# tc083-18.net
KiCad netlist of a schematic drawn in EAGLE
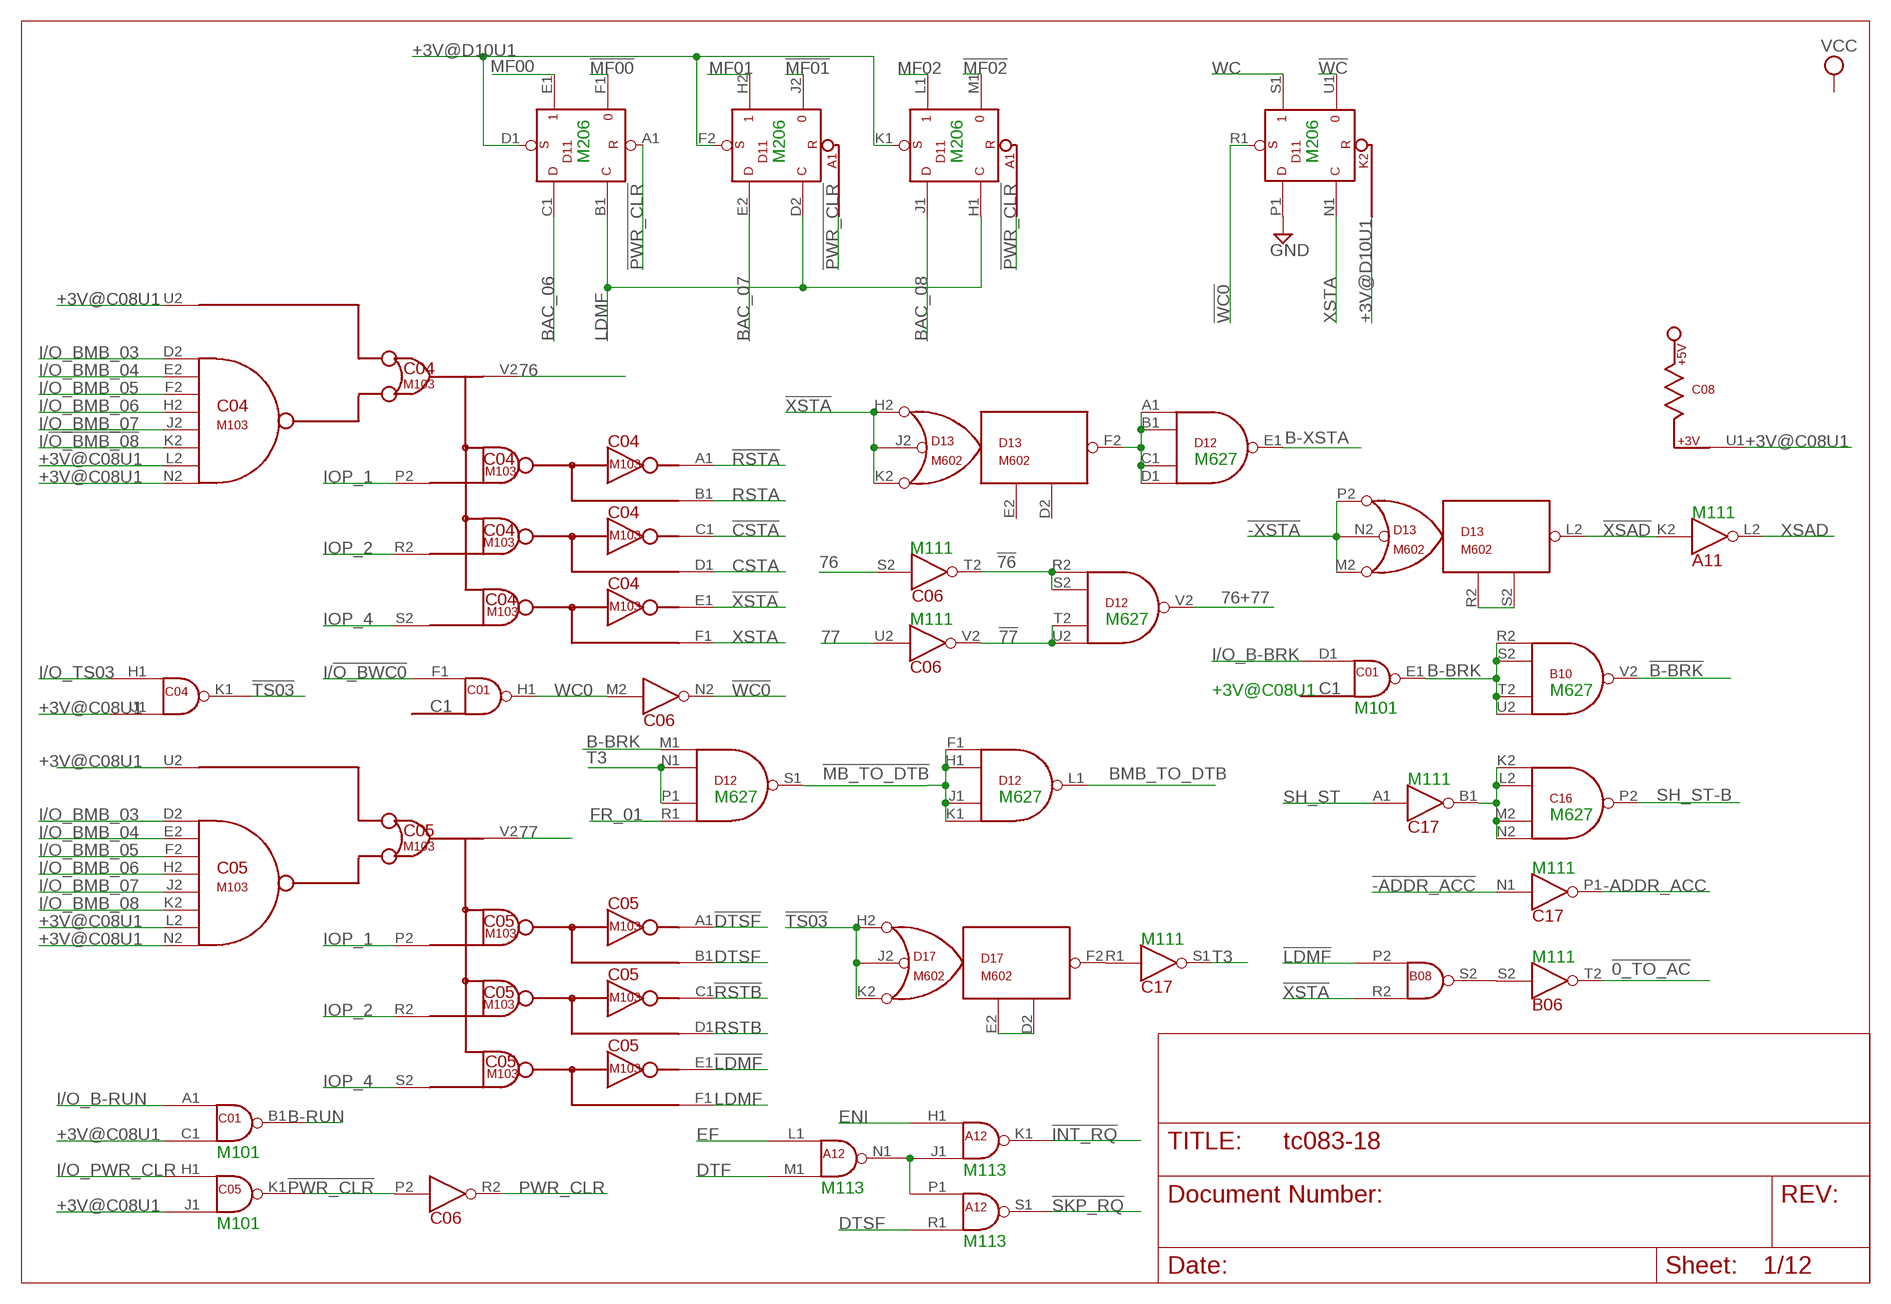
[diagram p0: schematic, sheet 1]
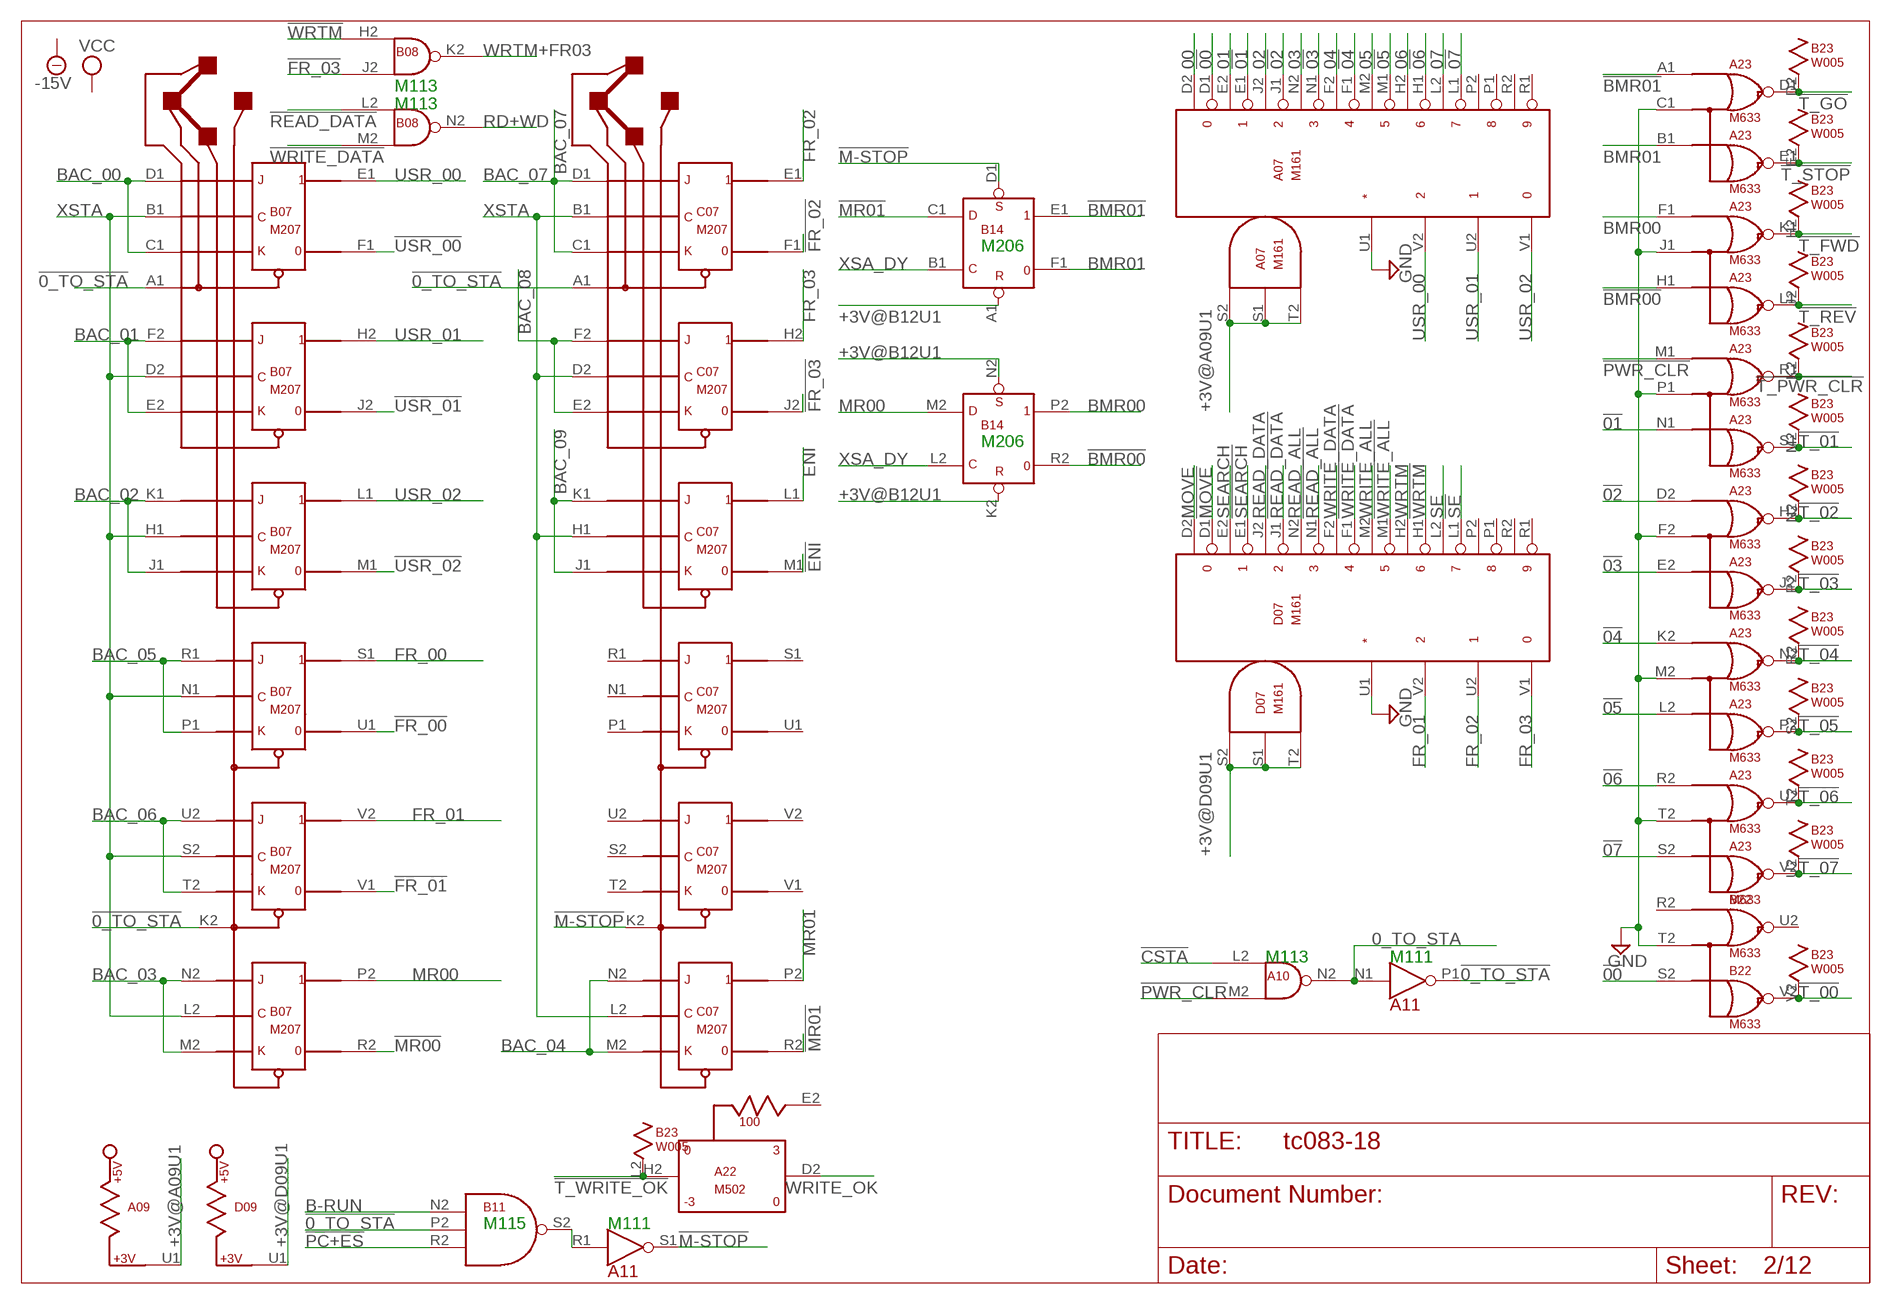
[diagram p1: schematic, sheet 2]
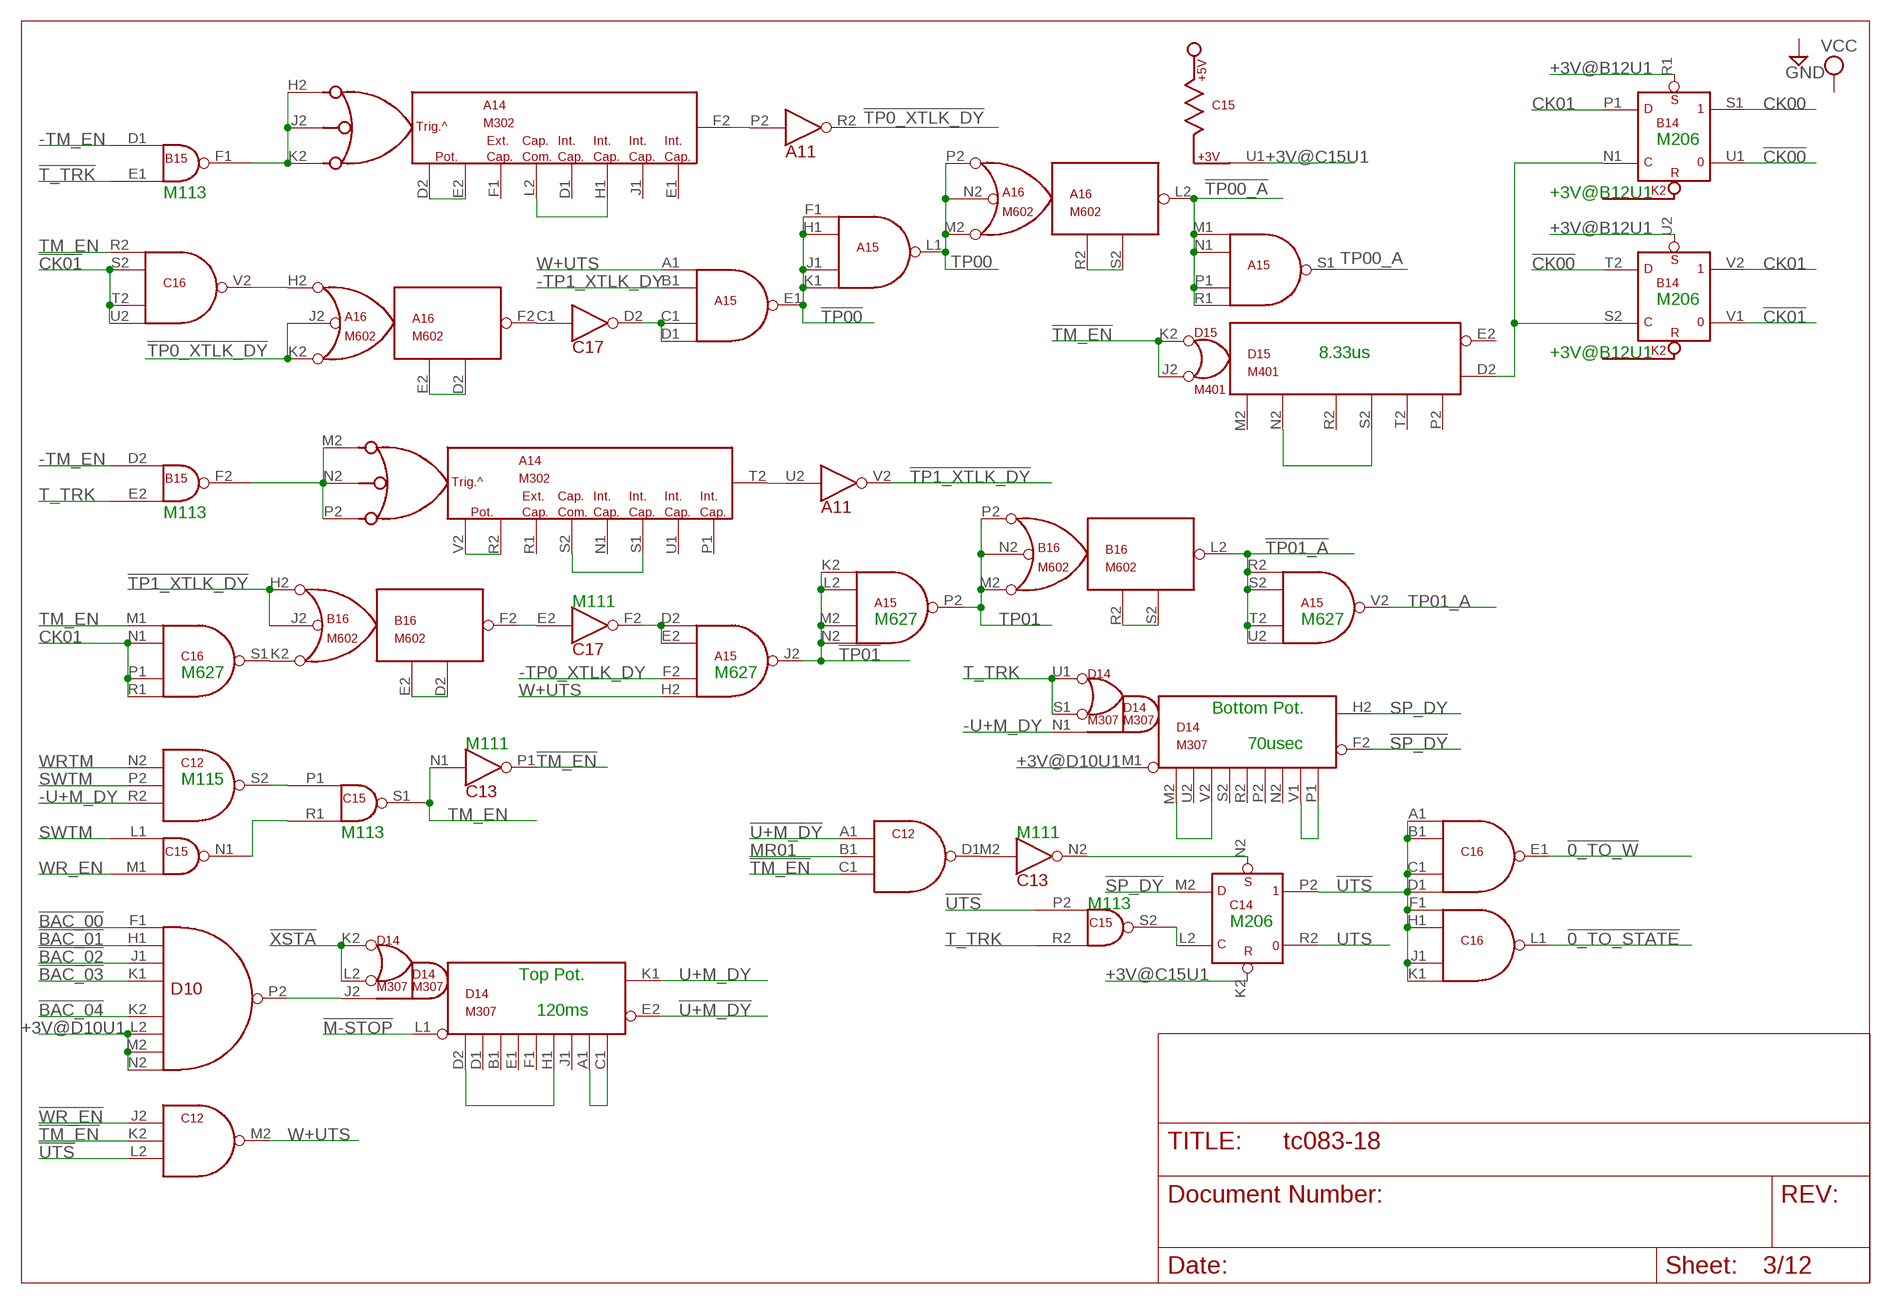
[diagram p2: schematic, sheet 3]
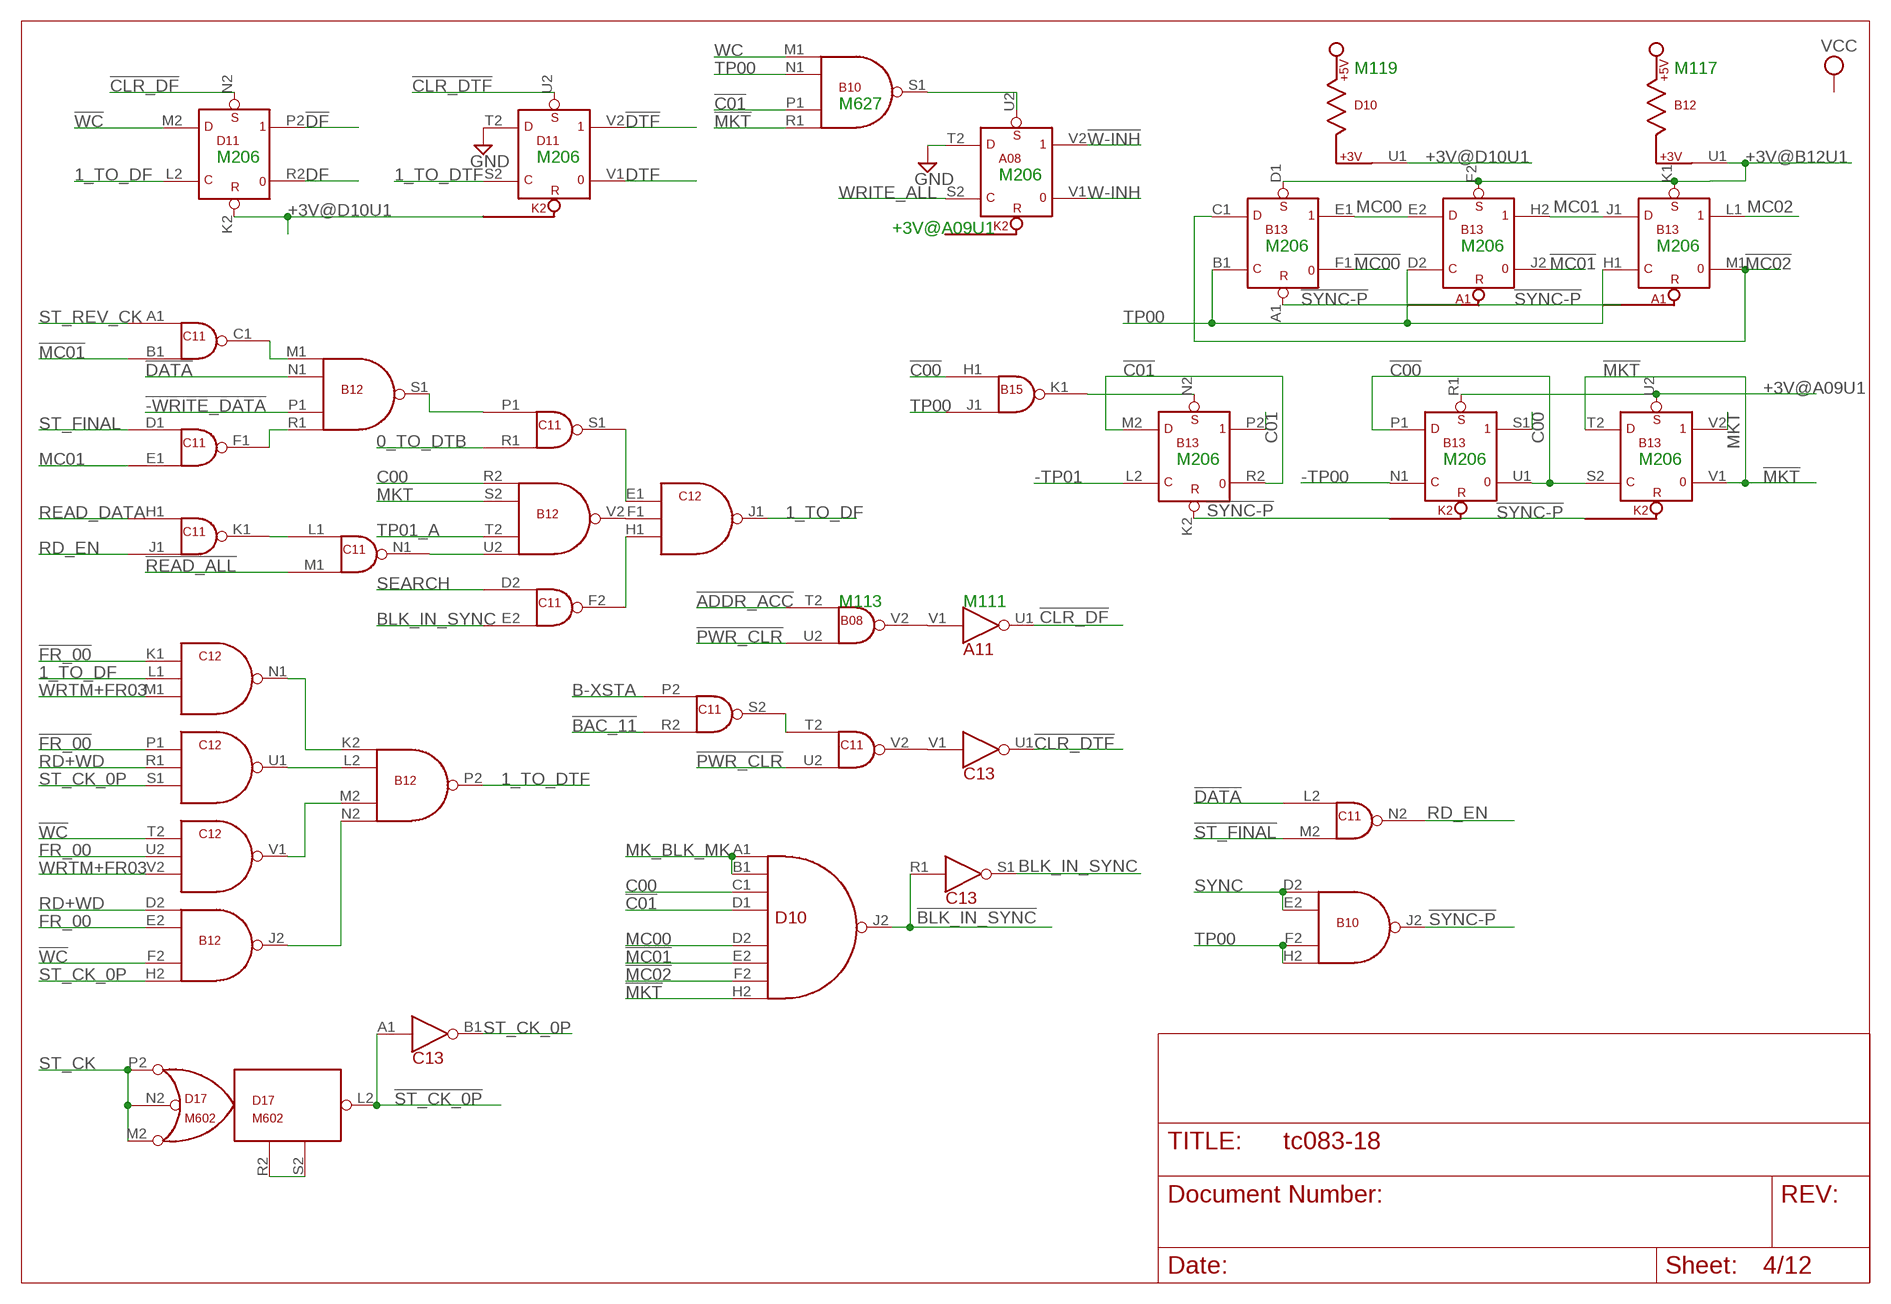
[diagram p3: schematic, sheet 4]
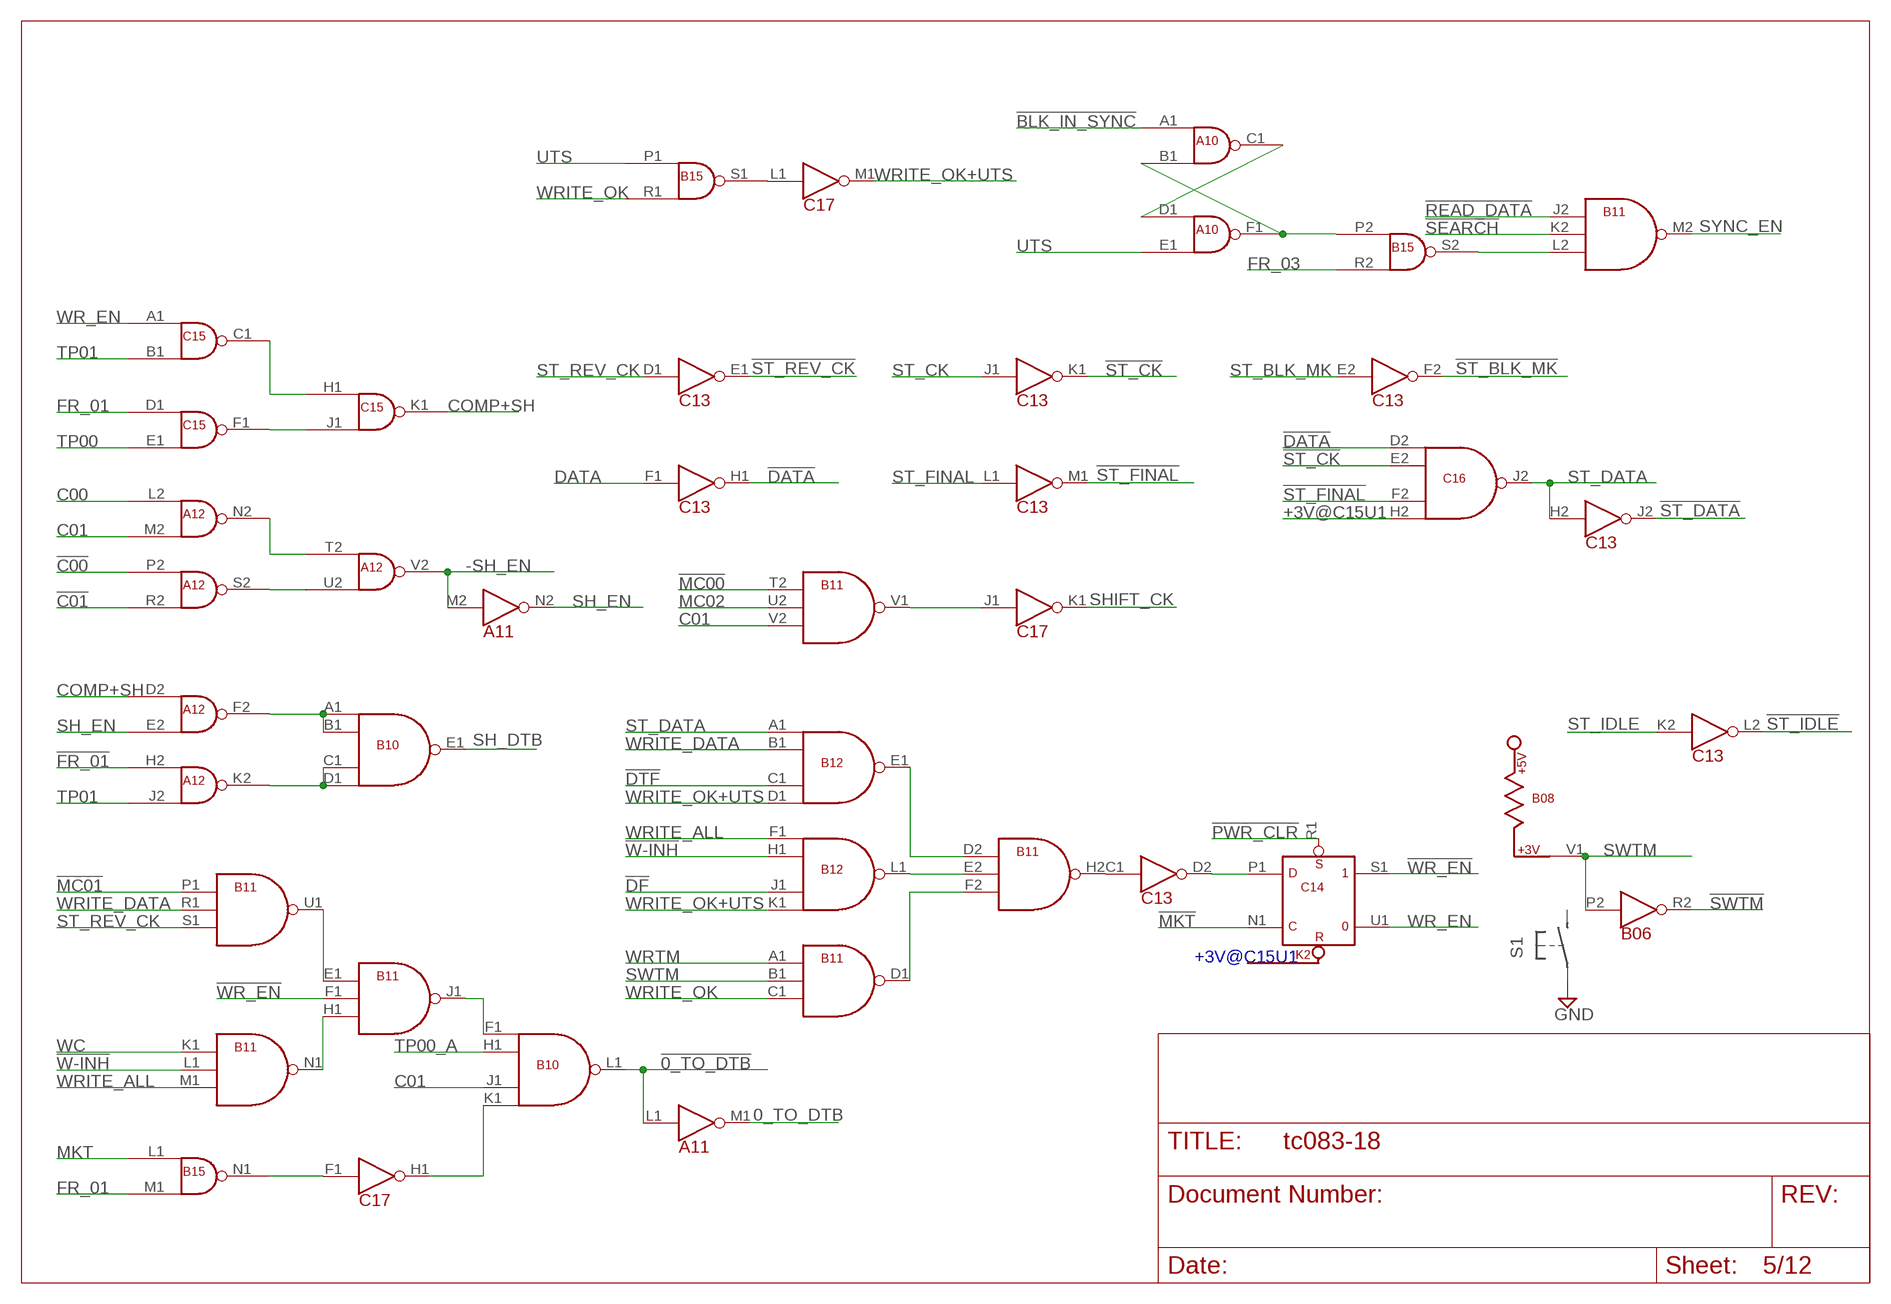
[diagram p4: schematic, sheet 5]
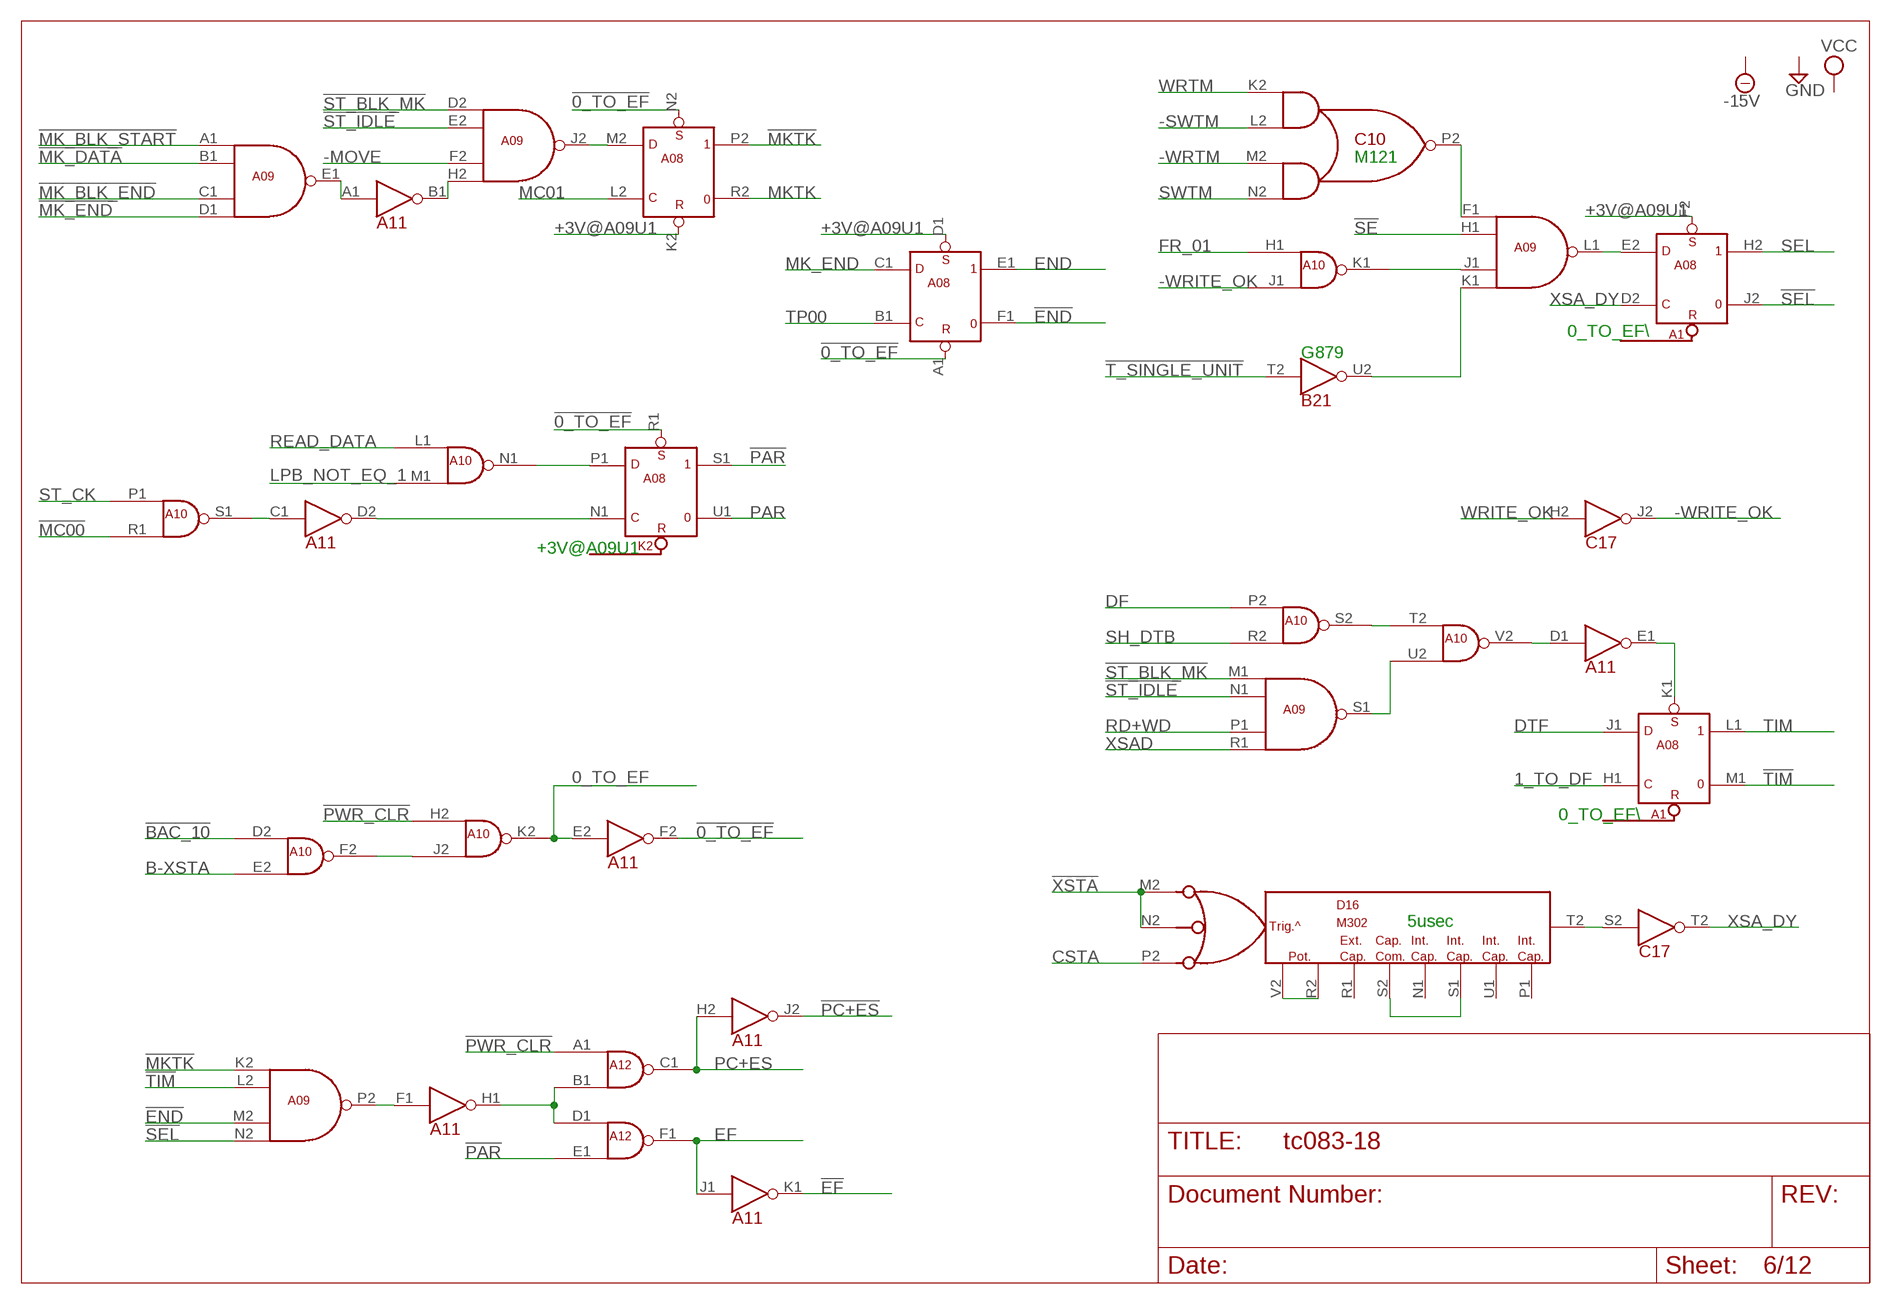
[diagram p5: schematic, sheet 6]
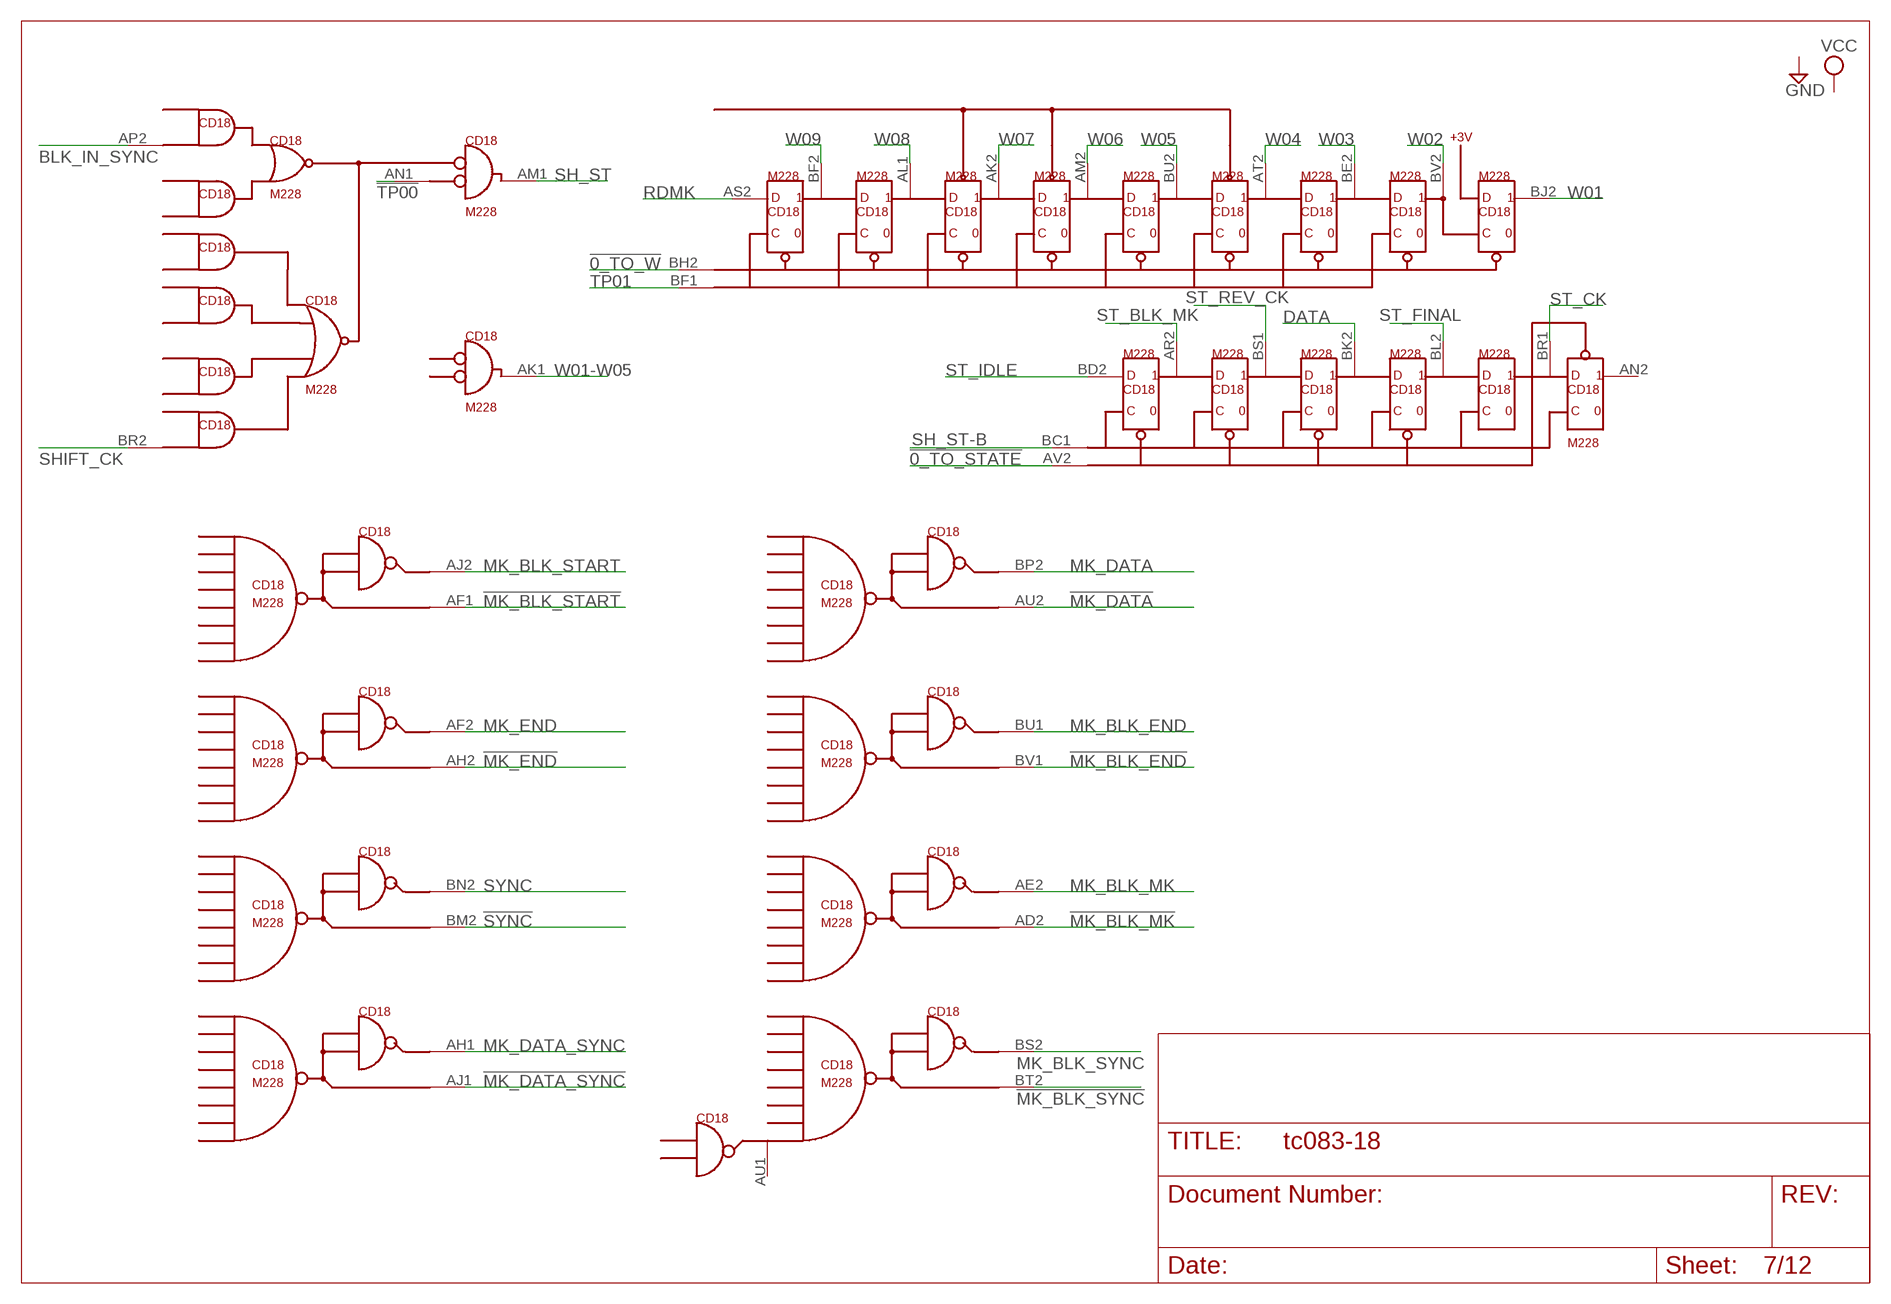
[diagram p6: schematic, sheet 7]
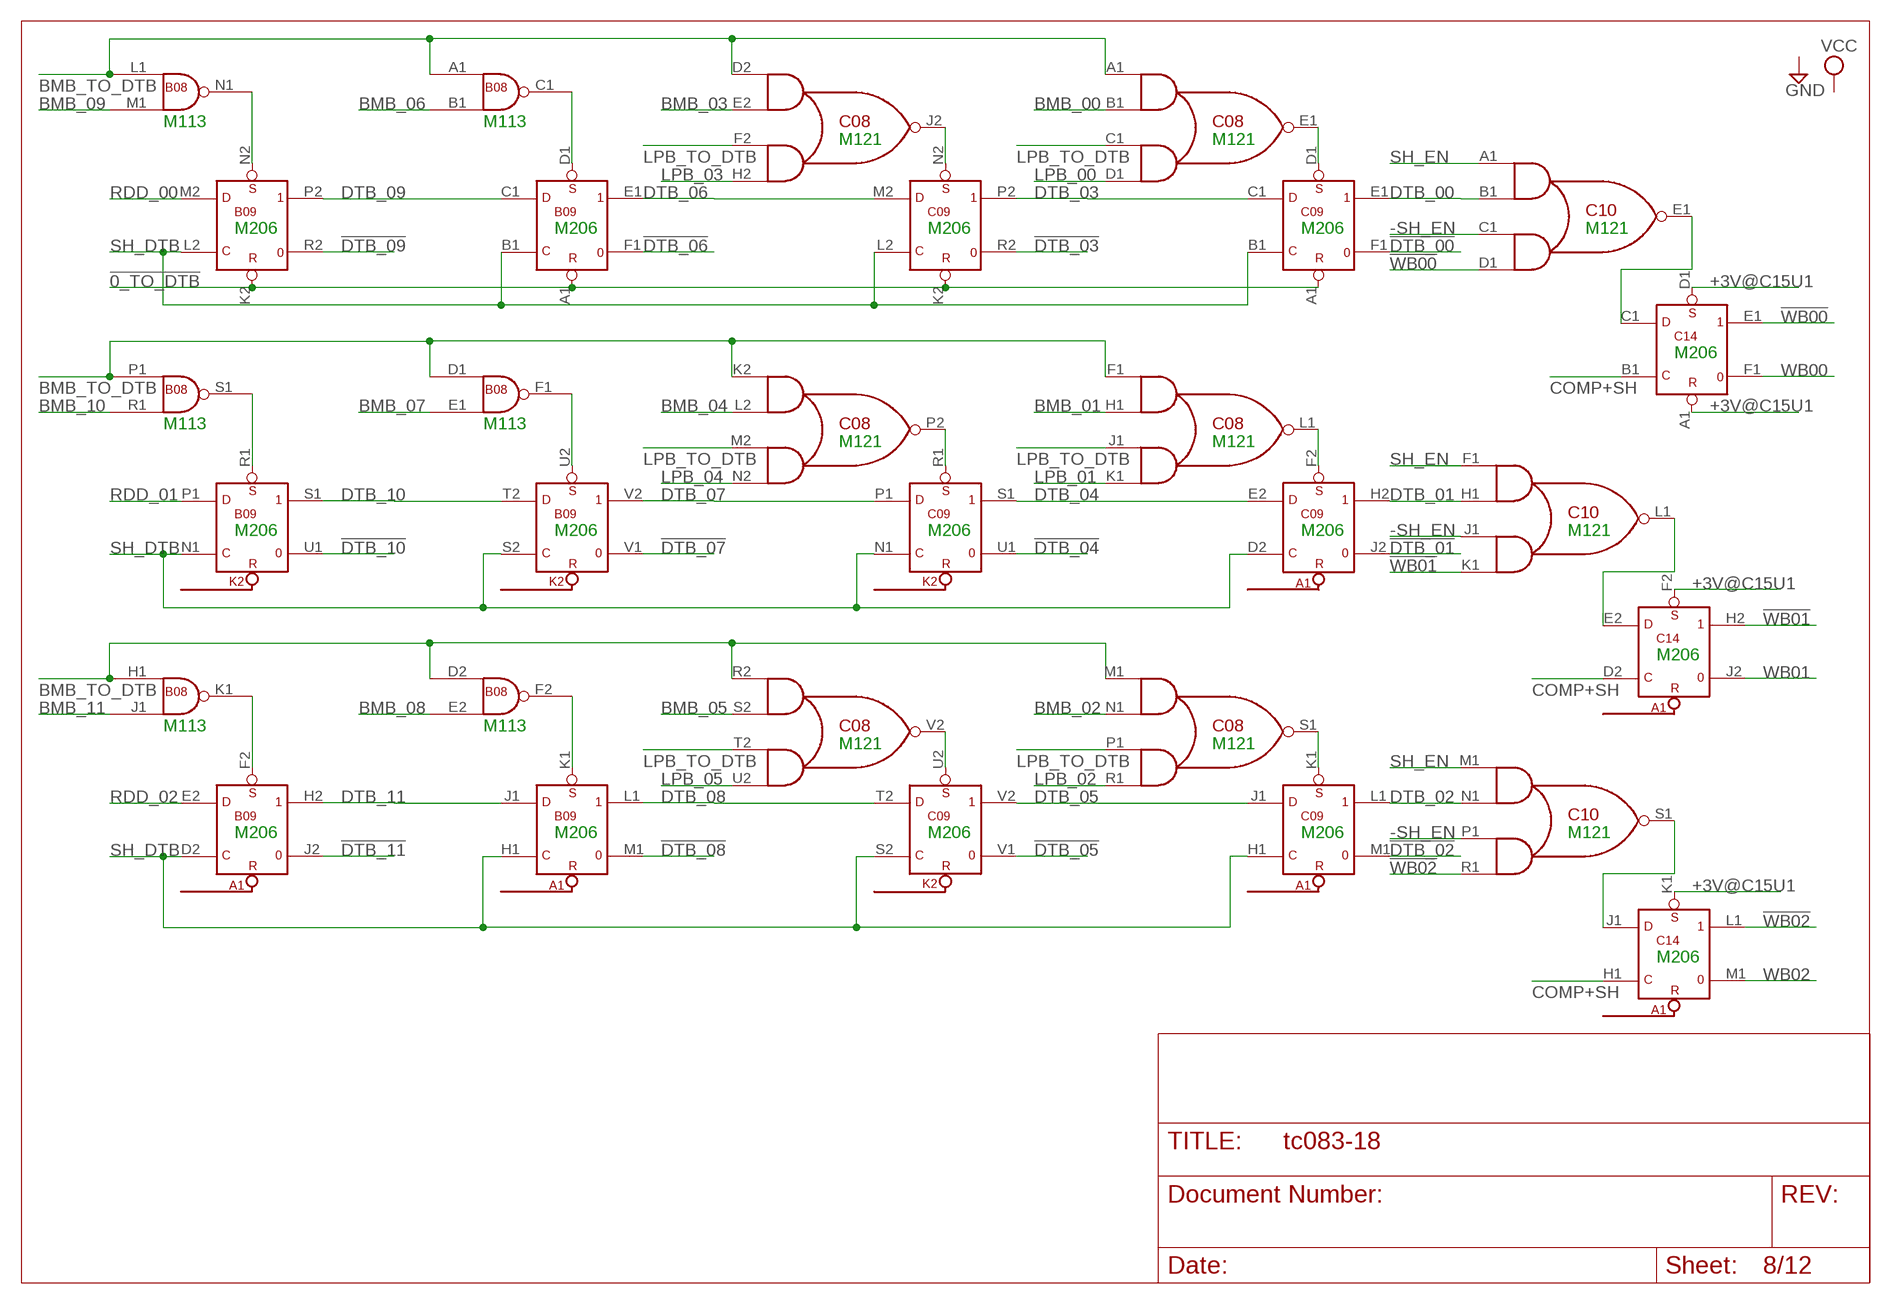
[diagram p7: schematic, sheet 8]
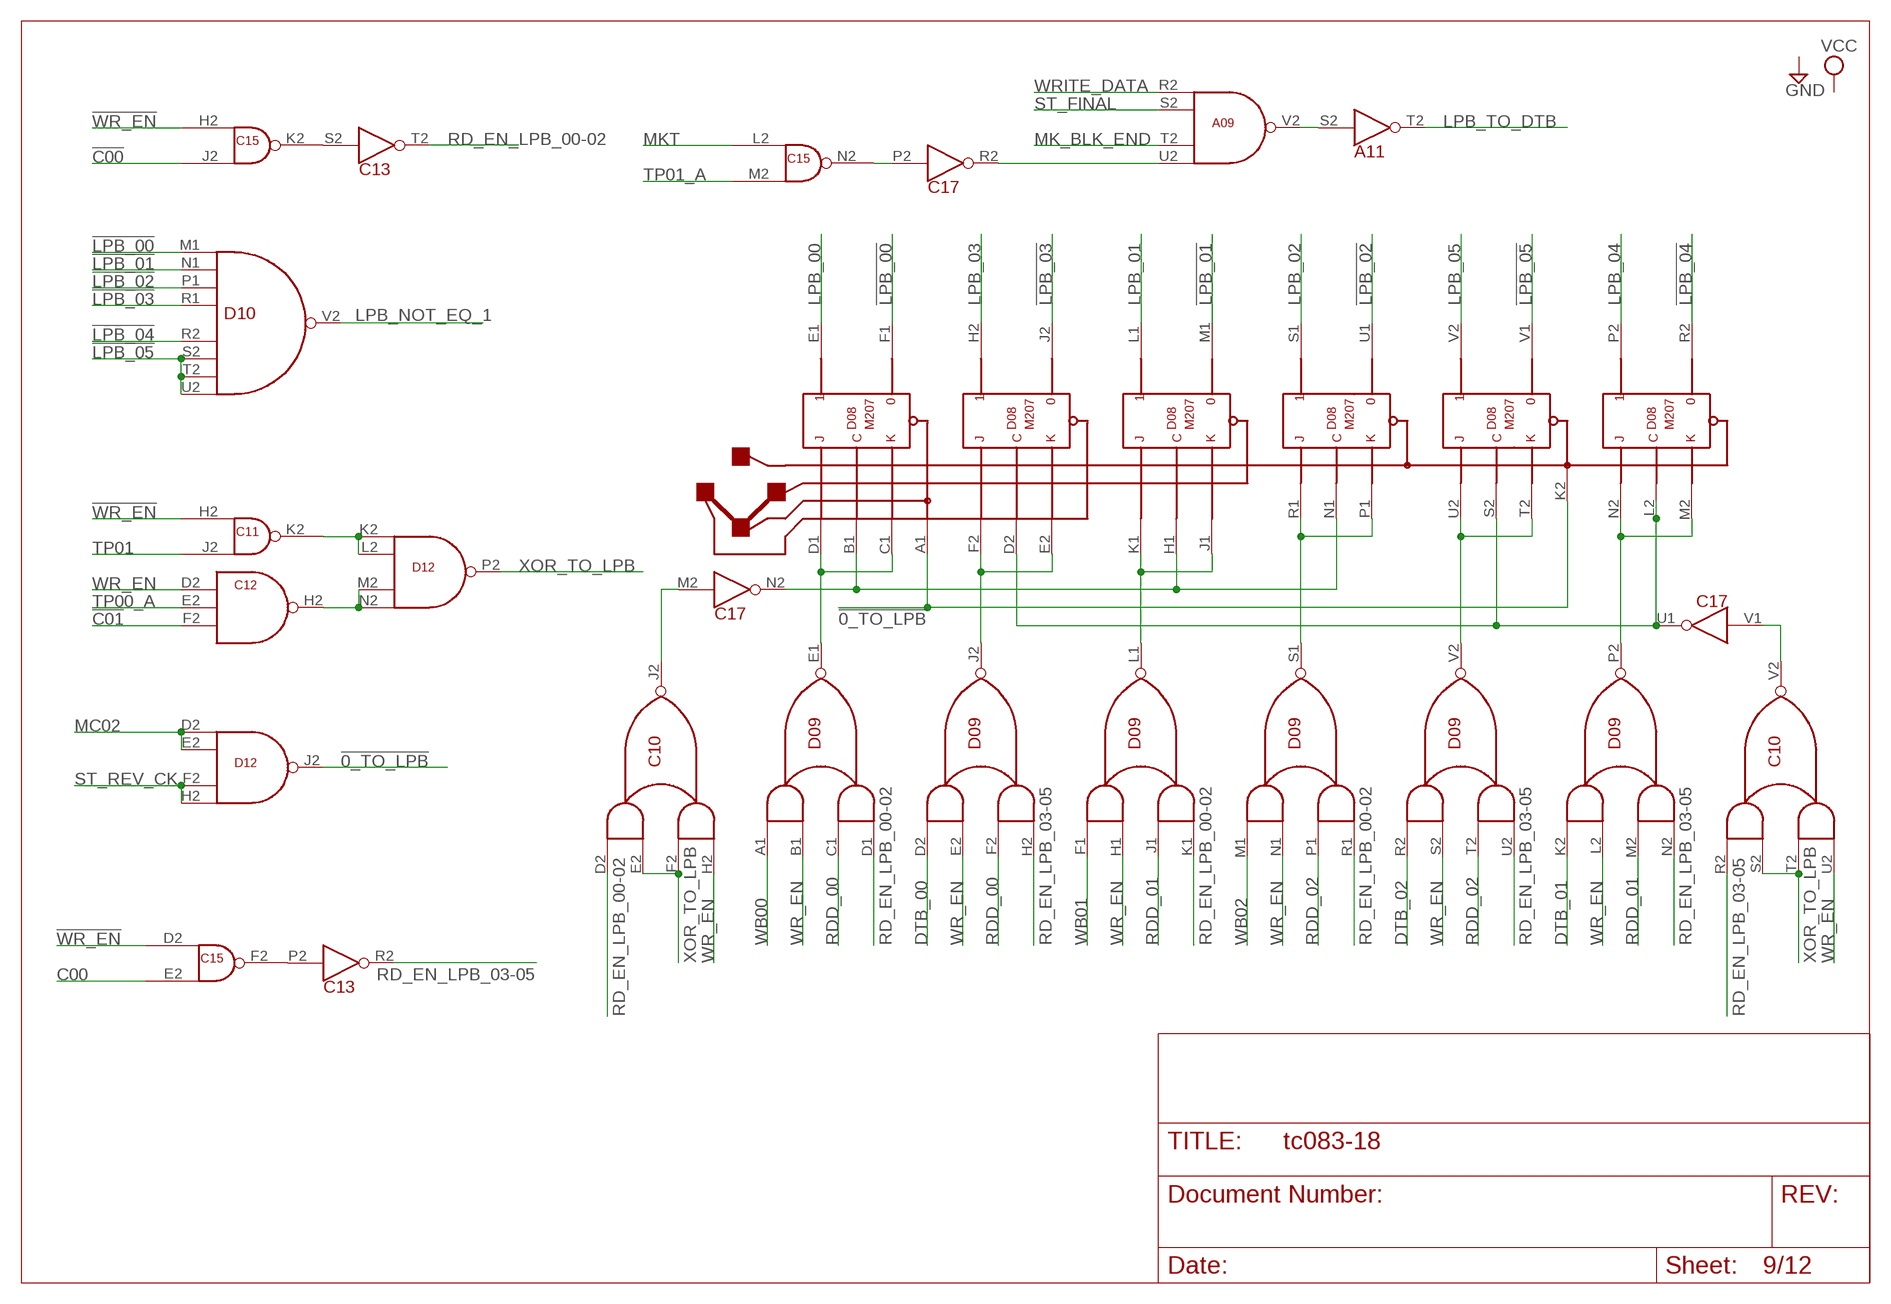
[diagram p8: schematic, sheet 9]
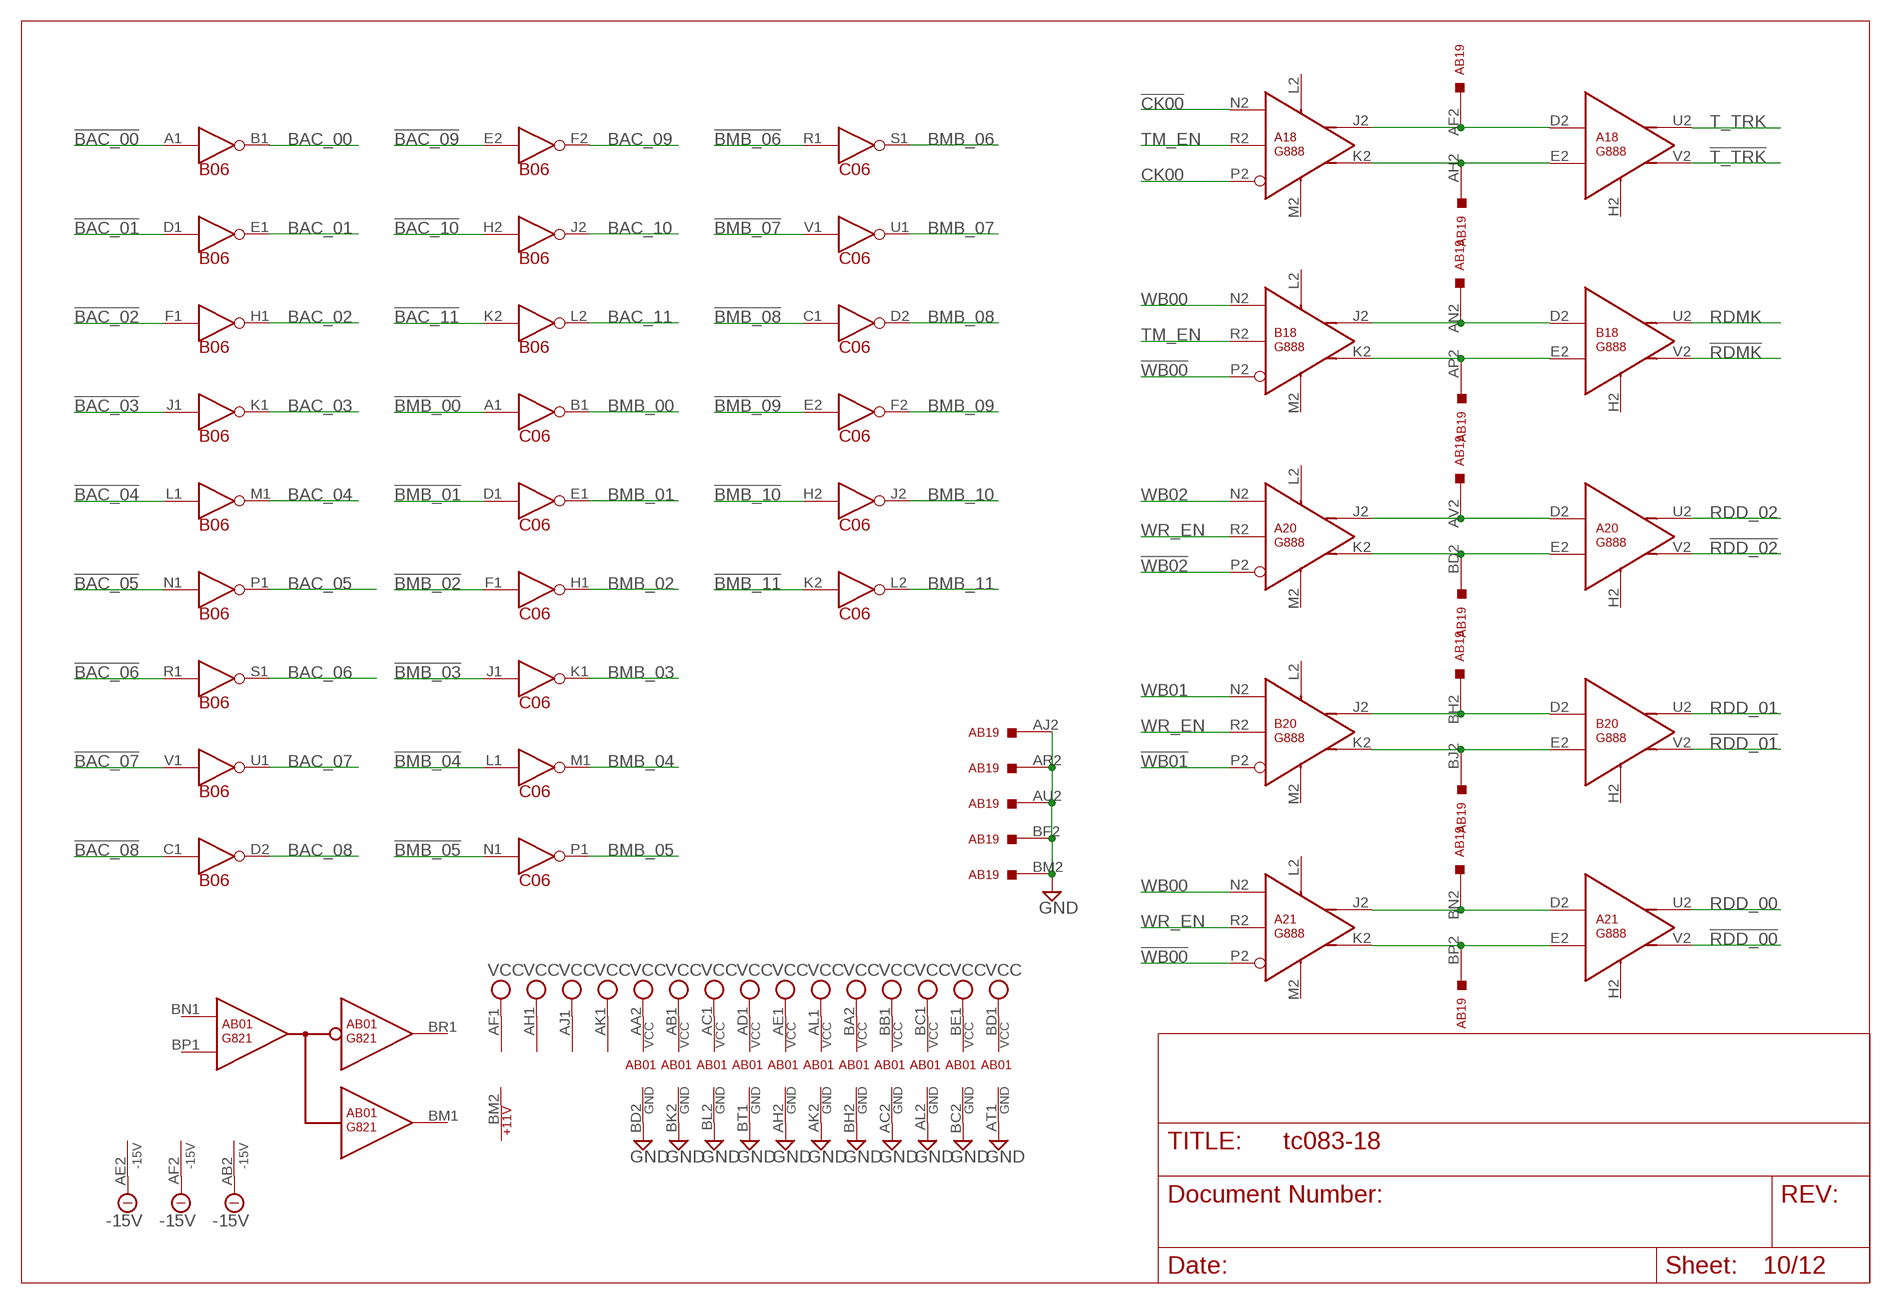
[diagram p9: schematic, sheet 10]
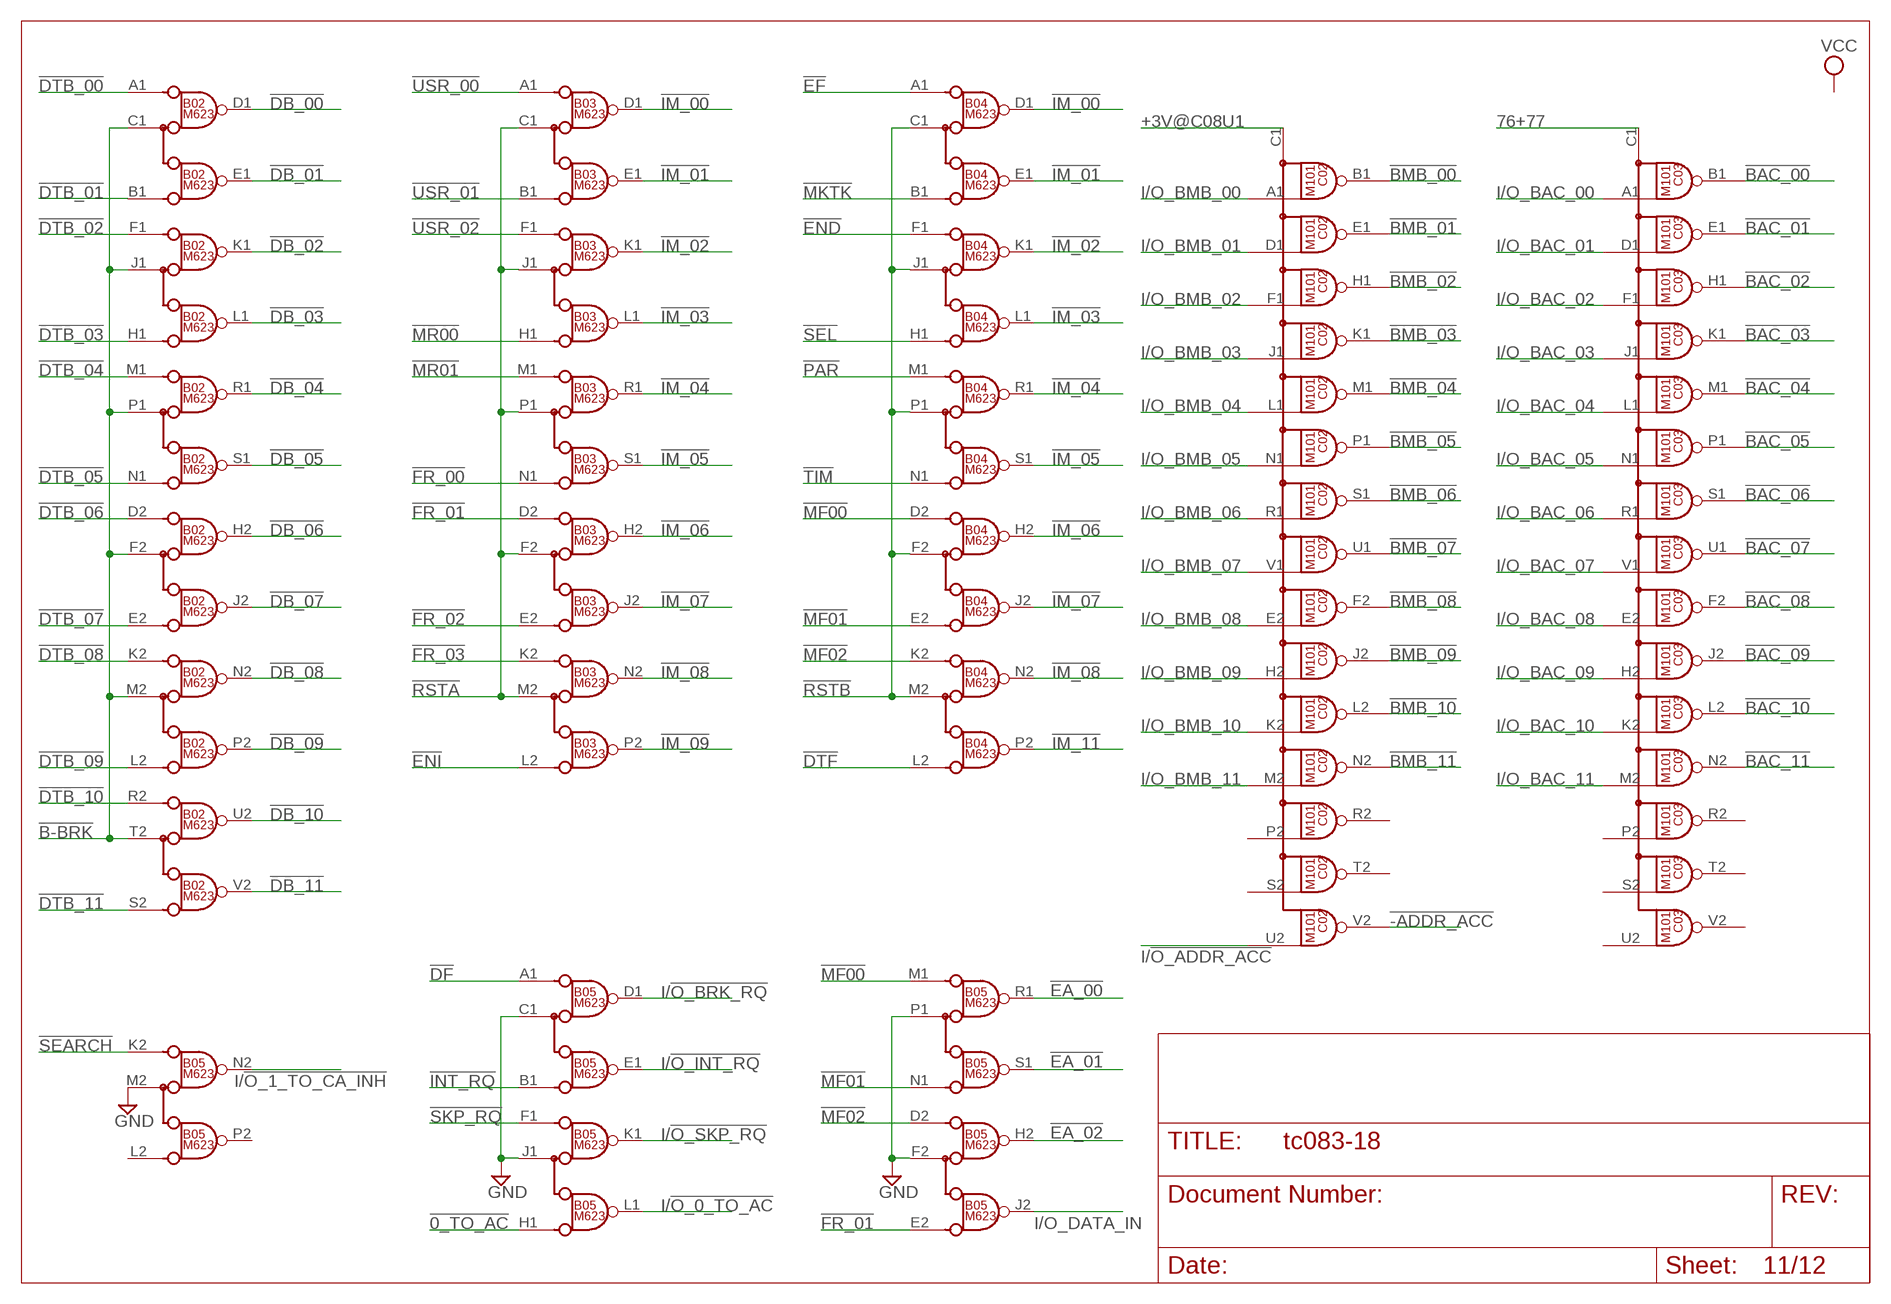
[diagram p10: schematic, sheet 11]
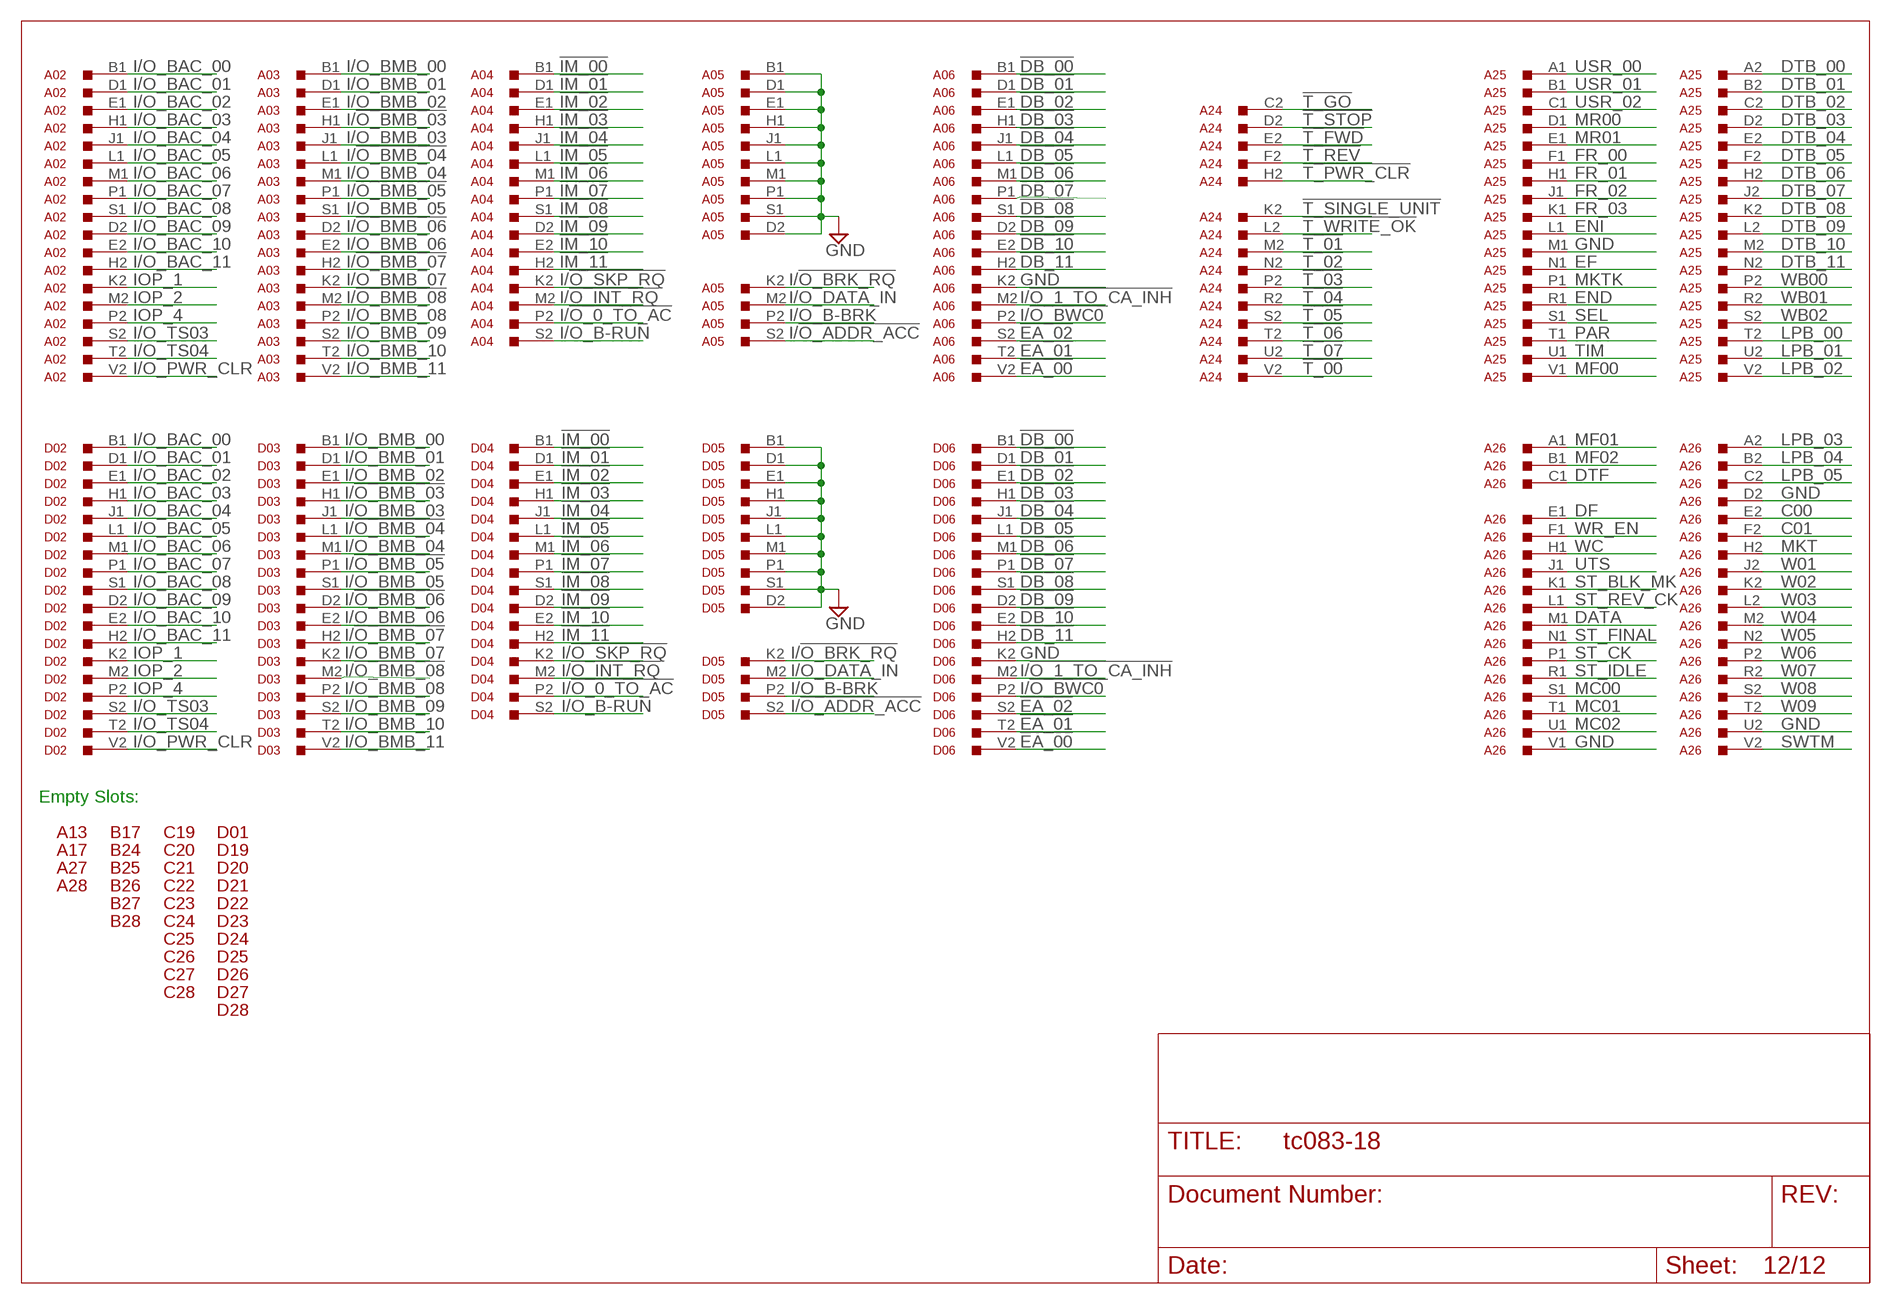
[diagram p11: schematic, sheet 12]

(export (version "E")
  (design (tool "Eeschema 10.0.6"))
  (components
    (comp (ref "A07")
      (value "A07")
      (footprint "eagle-import:H807")
      (libsource (lib "eagle-import") (part "M161"))
    )
    (comp (ref "A09")
      (value "M117")
      (footprint "eagle-import:H807")
      (libsource (lib "eagle-import") (part "M117"))
    )
    (comp (ref "A10")
      (value "M113")
      (footprint "eagle-import:H807")
      (libsource (lib "eagle-import") (part "M113"))
    )
    (comp (ref "A11")
      (value "A11")
      (footprint "eagle-import:H807")
      (libsource (lib "eagle-import") (part "M111"))
    )
    (comp (ref "A22")
      (value "M502")
      (footprint "eagle-import:H807")
      (libsource (lib "eagle-import") (part "M502"))
    )
    (comp (ref "A23")
      (value "M633")
      (footprint "eagle-import:H807")
      (libsource (lib "eagle-import") (part "M633"))
    )
    (comp (ref "B07")
      (value "B07")
      (footprint "eagle-import:H807")
      (libsource (lib "eagle-import") (part "M207"))
    )
    (comp (ref "B08")
      (value "B08")
      (footprint "eagle-import:H807")
      (libsource (lib "eagle-import") (part "M113"))
    )
    (comp (ref "B11")
      (value "M115")
      (footprint "eagle-import:H807")
      (libsource (lib "eagle-import") (part "M115"))
    )
    (comp (ref "B14")
      (value "M206X")
      (footprint "eagle-import:H807")
      (libsource (lib "eagle-import") (part "M206X"))
    )
    (comp (ref "B22")
      (value "M633")
      (footprint "eagle-import:H807")
      (libsource (lib "eagle-import") (part "M633"))
    )
    (comp (ref "B23")
      (value "W005")
      (footprint "eagle-import:H807")
      (libsource (lib "eagle-import") (part "W005"))
    )
    (comp (ref "C07")
      (value "B07")
      (footprint "eagle-import:H807")
      (libsource (lib "eagle-import") (part "M207"))
    )
    (comp (ref "D07")
      (value "D07")
      (footprint "eagle-import:H807")
      (libsource (lib "eagle-import") (part "M161"))
    )
    (comp (ref "D09")
      (value "M121")
      (footprint "eagle-import:H807")
      (libsource (lib "eagle-import") (part "M121"))
    )
    (comp (ref "A12")
      (value "A12")
      (footprint "eagle-import:H807")
      (libsource (lib "eagle-import") (part "M113"))
    )
    (comp (ref "B06")
      (value "B06")
      (footprint "eagle-import:H807")
      (libsource (lib "eagle-import") (part "M111"))
    )
    (comp (ref "B10")
      (value "B10")
      (footprint "eagle-import:H807")
      (libsource (lib "eagle-import") (part "M627"))
    )
    (comp (ref "B12")
      (value "M117")
      (footprint "eagle-import:H807")
      (libsource (lib "eagle-import") (part "M117"))
    )
    (comp (ref "B15")
      (value "M113")
      (footprint "eagle-import:H807")
      (libsource (lib "eagle-import") (part "M113"))
    )
    (comp (ref "C13")
      (value "M111")
      (footprint "eagle-import:H807")
      (libsource (lib "eagle-import") (part "M111"))
    )
    (comp (ref "C14")
      (value "M206X")
      (footprint "eagle-import:H807")
      (libsource (lib "eagle-import") (part "M206X"))
    )
    (comp (ref "C15")
      (value "M113")
      (footprint "eagle-import:H807")
      (libsource (lib "eagle-import") (part "M113"))
    )
    (comp (ref "C16")
      (value "C16")
      (footprint "eagle-import:H807")
      (libsource (lib "eagle-import") (part "M627"))
    )
    (comp (ref "C17")
      (value "C17")
      (footprint "eagle-import:H807")
      (libsource (lib "eagle-import") (part "M111"))
    )
    (comp (ref "A08")
      (value "M206X")
      (footprint "eagle-import:H807")
      (libsource (lib "eagle-import") (part "M206X"))
    )
    (comp (ref "B13")
      (value "M206X")
      (footprint "eagle-import:H807")
      (libsource (lib "eagle-import") (part "M206X"))
    )
    (comp (ref "C11")
      (value "M113")
      (footprint "eagle-import:H807")
      (libsource (lib "eagle-import") (part "M113"))
    )
    (comp (ref "C12")
      (value "M115")
      (footprint "eagle-import:H807")
      (libsource (lib "eagle-import") (part "M115"))
    )
    (comp (ref "D10")
      (value "M119")
      (footprint "eagle-import:H807")
      (libsource (lib "eagle-import") (part "M119"))
    )
    (comp (ref "D11")
      (value "M206X")
      (footprint "eagle-import:H807")
      (libsource (lib "eagle-import") (part "M206X"))
    )
    (comp (ref "D17")
      (value "D17")
      (footprint "eagle-import:H807")
      (libsource (lib "eagle-import") (part "M602"))
    )
    (comp (ref "B09")
      (value "M206X")
      (footprint "eagle-import:H807")
      (libsource (lib "eagle-import") (part "M206X"))
    )
    (comp (ref "C08")
      (value "C08")
      (footprint "eagle-import:H807")
      (libsource (lib "eagle-import") (part "M121"))
    )
    (comp (ref "C09")
      (value "M206X")
      (footprint "eagle-import:H807")
      (libsource (lib "eagle-import") (part "M206X"))
    )
    (comp (ref "C10")
      (value "M121")
      (footprint "eagle-import:H807")
      (libsource (lib "eagle-import") (part "M121"))
    )
    (comp (ref "A14")
      (value "M302")
      (footprint "eagle-import:H807")
      (libsource (lib "eagle-import") (part "M302"))
    )
    (comp (ref "A15")
      (value "M627")
      (footprint "eagle-import:H807")
      (libsource (lib "eagle-import") (part "M627"))
    )
    (comp (ref "A16")
      (value "M602")
      (footprint "eagle-import:H807")
      (libsource (lib "eagle-import") (part "M602"))
    )
    (comp (ref "B16")
      (value "M602")
      (footprint "eagle-import:H807")
      (libsource (lib "eagle-import") (part "M602"))
    )
    (comp (ref "D14")
      (value "M307")
      (footprint "eagle-import:H807")
      (libsource (lib "eagle-import") (part "M307"))
    )
    (comp (ref "D15")
      (value "M401")
      (footprint "eagle-import:H807")
      (libsource (lib "eagle-import") (part "M401"))
    )
    (comp (ref "B02")
      (value "M623")
      (footprint "eagle-import:H807")
      (libsource (lib "eagle-import") (part "M623"))
    )
    (comp (ref "B03")
      (value "M623")
      (footprint "eagle-import:H807")
      (libsource (lib "eagle-import") (part "M623"))
    )
    (comp (ref "B04")
      (value "M623")
      (footprint "eagle-import:H807")
      (libsource (lib "eagle-import") (part "M623"))
    )
    (comp (ref "B05")
      (value "M623")
      (footprint "eagle-import:H807")
      (libsource (lib "eagle-import") (part "M623"))
    )
    (comp (ref "C02")
      (value "M101-ARRAY")
      (footprint "eagle-import:H807")
      (libsource (lib "eagle-import") (part "M101-ARRAY"))
    )
    (comp (ref "C03")
      (value "M101-ARRAY")
      (footprint "eagle-import:H807")
      (libsource (lib "eagle-import") (part "M101-ARRAY"))
    )
    (comp (ref "A18")
      (value "G888")
      (footprint "eagle-import:H807")
      (libsource (lib "eagle-import") (part "G888"))
    )
    (comp (ref "A20")
      (value "G888")
      (footprint "eagle-import:H807")
      (libsource (lib "eagle-import") (part "G888"))
    )
    (comp (ref "A21")
      (value "G888")
      (footprint "eagle-import:H807")
      (libsource (lib "eagle-import") (part "G888"))
    )
    (comp (ref "AB01")
      (value "G821")
      (footprint "eagle-import:H807-2")
      (libsource (lib "eagle-import") (part "G821"))
    )
    (comp (ref "AB19")
      (value "W032")
      (footprint "eagle-import:H807-2")
      (libsource (lib "eagle-import") (part "W032"))
    )
    (comp (ref "B18")
      (value "G888")
      (footprint "eagle-import:H807")
      (libsource (lib "eagle-import") (part "G888"))
    )
    (comp (ref "B20")
      (value "G888")
      (footprint "eagle-import:H807")
      (libsource (lib "eagle-import") (part "G888"))
    )
    (comp (ref "C06")
      (value "C06")
      (footprint "eagle-import:H807")
      (libsource (lib "eagle-import") (part "M111"))
    )
    (comp (ref "D08")
      (value "M207")
      (footprint "eagle-import:H807")
      (libsource (lib "eagle-import") (part "M207"))
    )
    (comp (ref "D12")
      (value "D12")
      (footprint "eagle-import:H807")
      (libsource (lib "eagle-import") (part "M627"))
    )
    (comp (ref "C01")
      (value "C01")
      (footprint "eagle-import:H807")
      (libsource (lib "eagle-import") (part "M101"))
    )
    (comp (ref "C04")
      (value "C04")
      (footprint "eagle-import:H807")
      (libsource (lib "eagle-import") (part "M103"))
    )
    (comp (ref "C05")
      (value "C05")
      (footprint "eagle-import:H807")
      (libsource (lib "eagle-import") (part "M103"))
    )
    (comp (ref "D13")
      (value "D13")
      (footprint "eagle-import:H807")
      (libsource (lib "eagle-import") (part "M602"))
    )
    (comp (ref "A02")
      (value "M903")
      (footprint "eagle-import:H807")
      (libsource (lib "eagle-import") (part "M903"))
    )
    (comp (ref "A03")
      (value "M903")
      (footprint "eagle-import:H807")
      (libsource (lib "eagle-import") (part "M903"))
    )
    (comp (ref "A04")
      (value "M903")
      (footprint "eagle-import:H807")
      (libsource (lib "eagle-import") (part "M903"))
    )
    (comp (ref "A05")
      (value "M903")
      (footprint "eagle-import:H807")
      (libsource (lib "eagle-import") (part "M903"))
    )
    (comp (ref "A06")
      (value "M903")
      (footprint "eagle-import:H807")
      (libsource (lib "eagle-import") (part "M903"))
    )
    (comp (ref "A13")
      (value "H807")
      (footprint "eagle-import:H807")
      (libsource (lib "eagle-import") (part "H807"))
    )
    (comp (ref "A17")
      (value "H807")
      (footprint "eagle-import:H807")
      (libsource (lib "eagle-import") (part "H807"))
    )
    (comp (ref "A24")
      (value "W023")
      (footprint "eagle-import:H807")
      (libsource (lib "eagle-import") (part "W023"))
    )
    (comp (ref "A25")
      (value "M916")
      (footprint "eagle-import:H807")
      (libsource (lib "eagle-import") (part "M916"))
    )
    (comp (ref "A26")
      (value "M916")
      (footprint "eagle-import:H807")
      (libsource (lib "eagle-import") (part "M916"))
    )
    (comp (ref "A27")
      (value "H807")
      (footprint "eagle-import:H807")
      (libsource (lib "eagle-import") (part "H807"))
    )
    (comp (ref "A28")
      (value "H807")
      (footprint "eagle-import:H807")
      (libsource (lib "eagle-import") (part "H807"))
    )
    (comp (ref "B17")
      (value "H807")
      (footprint "eagle-import:H807")
      (libsource (lib "eagle-import") (part "H807"))
    )
    (comp (ref "B24")
      (value "H807")
      (footprint "eagle-import:H807")
      (libsource (lib "eagle-import") (part "H807"))
    )
    (comp (ref "B25")
      (value "H807")
      (footprint "eagle-import:H807")
      (libsource (lib "eagle-import") (part "H807"))
    )
    (comp (ref "B26")
      (value "H807")
      (footprint "eagle-import:H807")
      (libsource (lib "eagle-import") (part "H807"))
    )
    (comp (ref "B27")
      (value "H807")
      (footprint "eagle-import:H807")
      (libsource (lib "eagle-import") (part "H807"))
    )
    (comp (ref "B28")
      (value "H807")
      (footprint "eagle-import:H807")
      (libsource (lib "eagle-import") (part "H807"))
    )
    (comp (ref "C19")
      (value "H807")
      (footprint "eagle-import:H807")
      (libsource (lib "eagle-import") (part "H807"))
    )
    (comp (ref "C20")
      (value "H807")
      (footprint "eagle-import:H807")
      (libsource (lib "eagle-import") (part "H807"))
    )
    (comp (ref "C21")
      (value "H807")
      (footprint "eagle-import:H807")
      (libsource (lib "eagle-import") (part "H807"))
    )
    (comp (ref "C22")
      (value "H807")
      (footprint "eagle-import:H807")
      (libsource (lib "eagle-import") (part "H807"))
    )
    (comp (ref "C23")
      (value "H807")
      (footprint "eagle-import:H807")
      (libsource (lib "eagle-import") (part "H807"))
    )
    (comp (ref "C24")
      (value "H807")
      (footprint "eagle-import:H807")
      (libsource (lib "eagle-import") (part "H807"))
    )
    (comp (ref "C25")
      (value "H807")
      (footprint "eagle-import:H807")
      (libsource (lib "eagle-import") (part "H807"))
    )
    (comp (ref "C26")
      (value "H807")
      (footprint "eagle-import:H807")
      (libsource (lib "eagle-import") (part "H807"))
    )
    (comp (ref "C27")
      (value "H807")
      (footprint "eagle-import:H807")
      (libsource (lib "eagle-import") (part "H807"))
    )
    (comp (ref "C28")
      (value "H807")
      (footprint "eagle-import:H807")
      (libsource (lib "eagle-import") (part "H807"))
    )
    (comp (ref "D01")
      (value "H807")
      (footprint "eagle-import:H807")
      (libsource (lib "eagle-import") (part "H807"))
    )
    (comp (ref "D02")
      (value "M903")
      (footprint "eagle-import:H807")
      (libsource (lib "eagle-import") (part "M903"))
    )
    (comp (ref "D03")
      (value "M903")
      (footprint "eagle-import:H807")
      (libsource (lib "eagle-import") (part "M903"))
    )
    (comp (ref "D04")
      (value "M903")
      (footprint "eagle-import:H807")
      (libsource (lib "eagle-import") (part "M903"))
    )
    (comp (ref "D05")
      (value "M903")
      (footprint "eagle-import:H807")
      (libsource (lib "eagle-import") (part "M903"))
    )
    (comp (ref "D06")
      (value "M903")
      (footprint "eagle-import:H807")
      (libsource (lib "eagle-import") (part "M903"))
    )
    (comp (ref "D19")
      (value "H807")
      (footprint "eagle-import:H807")
      (libsource (lib "eagle-import") (part "H807"))
    )
    (comp (ref "D20")
      (value "H807")
      (footprint "eagle-import:H807")
      (libsource (lib "eagle-import") (part "H807"))
    )
    (comp (ref "D21")
      (value "H807")
      (footprint "eagle-import:H807")
      (libsource (lib "eagle-import") (part "H807"))
    )
    (comp (ref "D22")
      (value "H807")
      (footprint "eagle-import:H807")
      (libsource (lib "eagle-import") (part "H807"))
    )
    (comp (ref "D23")
      (value "H807")
      (footprint "eagle-import:H807")
      (libsource (lib "eagle-import") (part "H807"))
    )
    (comp (ref "D24")
      (value "H807")
      (footprint "eagle-import:H807")
      (libsource (lib "eagle-import") (part "H807"))
    )
    (comp (ref "D25")
      (value "H807")
      (footprint "eagle-import:H807")
      (libsource (lib "eagle-import") (part "H807"))
    )
    (comp (ref "D26")
      (value "H807")
      (footprint "eagle-import:H807")
      (libsource (lib "eagle-import") (part "H807"))
    )
    (comp (ref "D27")
      (value "H807")
      (footprint "eagle-import:H807")
      (libsource (lib "eagle-import") (part "H807"))
    )
    (comp (ref "D28")
      (value "H807")
      (footprint "eagle-import:H807")
      (libsource (lib "eagle-import") (part "H807"))
    )
    (comp (ref "CD18")
      (value "M228")
      (footprint "eagle-import:H807-2")
      (libsource (lib "eagle-import") (part "M228"))
    )
    (comp (ref "B21")
      (value "G879")
      (footprint "eagle-import:H807")
      (libsource (lib "eagle-import") (part "G879"))
    )
    (comp (ref "D16")
      (value "M302")
      (footprint "eagle-import:H807")
      (libsource (lib "eagle-import") (part "M302"))
    )
  )
  (nets
    (net (code "1") (name "+3V@A09U1") (class "Default")
      (node (ref "A07") (pin "S1") (pinfunction "EN2_S1") (pintype "input"))
      (node (ref "A07") (pin "S2") (pinfunction "EN1_S2") (pintype "input"))
      (node (ref "A07") (pin "T2") (pinfunction "EN3_T2") (pintype "input"))
      (node (ref "A08") (pin "D1") (pinfunction "S_D1") (pintype "input"))
      (node (ref "A08") (pin "F2") (pinfunction "S_F2") (pintype "input"))
      (node (ref "A08") (pin "K2") (pinfunction "R_K2") (pintype "input"))
      (node (ref "A09") (pin "U1") (pinfunction "P$1_U1") (pintype "output"))
      (node (ref "B13") (pin "R1") (pinfunction "S_R1") (pintype "input"))
      (node (ref "B13") (pin "U2") (pinfunction "S_U2") (pintype "input"))
    )
    (net (code "2") (name "+3V@B12U1") (class "Default")
      (node (ref "B12") (pin "U1") (pinfunction "P$1_U1") (pintype "output"))
      (node (ref "B13") (pin "D1") (pinfunction "S_D1") (pintype "input"))
      (node (ref "B13") (pin "F2") (pinfunction "S_F2") (pintype "input"))
      (node (ref "B13") (pin "K1") (pinfunction "S_K1") (pintype "input"))
      (node (ref "B14") (pin "A1") (pinfunction "R_A1") (pintype "input"))
      (node (ref "B14") (pin "K2") (pinfunction "R_K2") (pintype "input"))
      (node (ref "B14") (pin "N2") (pinfunction "S_N2") (pintype "input"))
      (node (ref "B14") (pin "R1") (pinfunction "S_R1") (pintype "input"))
      (node (ref "B14") (pin "U2") (pinfunction "S_U2") (pintype "input"))
    )
    (net (code "3") (name "+3V@C08U1") (class "Default")
      (node (ref "C01") (pin "C1") (pinfunction "IN2_C1") (pintype "input"))
      (node (ref "C02") (pin "C1") (pinfunction "ENABLE_C1") (pintype "input"))
      (node (ref "C04") (pin "J1") (pinfunction "IN2_J1") (pintype "input"))
      (node (ref "C04") (pin "L2") (pinfunction "L2_L2") (pintype "input"))
      (node (ref "C04") (pin "N2") (pinfunction "N2_N2") (pintype "input"))
      (node (ref "C04") (pin "U2") (pinfunction "U2_U2") (pintype "input"))
      (node (ref "C05") (pin "J1") (pinfunction "IN2_J1") (pintype "input"))
      (node (ref "C05") (pin "L2") (pinfunction "L2_L2") (pintype "input"))
      (node (ref "C05") (pin "N2") (pinfunction "N2_N2") (pintype "input"))
      (node (ref "C05") (pin "U2") (pinfunction "U2_U2") (pintype "input"))
      (node (ref "C08") (pin "U1") (pinfunction "P$1_U1") (pintype "output"))
    )
    (net (code "4") (name "+3V@C15U1") (class "Default")
      (node (ref "C14") (pin "A1") (pinfunction "R_A1") (pintype "input"))
      (node (ref "C14") (pin "D1") (pinfunction "S_D1") (pintype "input"))
      (node (ref "C14") (pin "F2") (pinfunction "S_F2") (pintype "input"))
      (node (ref "C14") (pin "K1") (pinfunction "S_K1") (pintype "input"))
      (node (ref "C14") (pin "K2") (pinfunction "R_K2") (pintype "input"))
      (node (ref "C15") (pin "U1") (pinfunction "P$1_U1") (pintype "output"))
      (node (ref "C16") (pin "H2") (pinfunction "IN4_H2") (pintype "input"))
    )
    (net (code "5") (name "+3V@D09U1") (class "Default")
      (node (ref "D07") (pin "S1") (pinfunction "EN2_S1") (pintype "input"))
      (node (ref "D07") (pin "S2") (pinfunction "EN1_S2") (pintype "input"))
      (node (ref "D07") (pin "T2") (pinfunction "EN3_T2") (pintype "input"))
      (node (ref "D09") (pin "U1") (pinfunction "P$1_U1") (pintype "output"))
    )
    (net (code "6") (name "+3V@D10U1") (class "Default")
      (node (ref "D10") (pin "L2") (pinfunction "IN6_L2") (pintype "input"))
      (node (ref "D10") (pin "M2") (pinfunction "IN7_M2") (pintype "input"))
      (node (ref "D10") (pin "N2") (pinfunction "IN8_N2") (pintype "input"))
      (node (ref "D10") (pin "U1") (pinfunction "P$1_U1") (pintype "output"))
      (node (ref "D11") (pin "D1") (pinfunction "S_D1") (pintype "input"))
      (node (ref "D11") (pin "F2") (pinfunction "S_F2") (pintype "input"))
      (node (ref "D11") (pin "K1") (pinfunction "S_K1") (pintype "input"))
      (node (ref "D11") (pin "K2") (pinfunction "R_K2") (pintype "input"))
      (node (ref "D14") (pin "M1") (pinfunction "M1_M1") (pintype "input"))
    )
    (net (code "7") (name "+11V") (class "Default")
      (node (ref "AB01") (pin "BM2") (pinfunction "+11V_BM2") (pintype "power_in"))
    )
    (net (code "8") (name "-15V") (class "Default")
      (node (ref "AB01") (pin "AB2") (pinfunction "-15V_AB2") (pintype "power_in"))
      (node (ref "AB01") (pin "AE2") (pinfunction "-15V_AE2") (pintype "power_in"))
      (node (ref "AB01") (pin "AF2") (pinfunction "-15V_AF2") (pintype "power_in"))
    )
    (net (code "9") (name "-ADDR_ACC") (class "Default")
      (node (ref "C17") (pin "P1") (pinfunction "OUT_P1") (pintype "output"))
    )
    (net (code "10") (name "-MOVE") (class "Default")
      (node (ref "A09") (pin "F2") (pinfunction "IN3_F2") (pintype "input"))
    )
    (net (code "11") (name "-SH_EN") (class "Default")
      (node (ref "A11") (pin "M2") (pinfunction "IN_M2") (pintype "input"))
      (node (ref "A12") (pin "V2") (pinfunction "OUT_V2") (pintype "output"))
      (node (ref "C10") (pin "C1") (pinfunction "IN2A_C1") (pintype "input"))
      (node (ref "C10") (pin "J1") (pinfunction "IN2A_J1") (pintype "input"))
      (node (ref "C10") (pin "P1") (pinfunction "IN2A_P1") (pintype "input"))
    )
    (net (code "12") (name "-SWTM") (class "Default")
      (node (ref "C10") (pin "L2") (pinfunction "IN1B_L2") (pintype "input"))
    )
    (net (code "13") (name "-TM_EN") (class "Default")
      (node (ref "B15") (pin "D1") (pinfunction "IN1_D1") (pintype "input"))
      (node (ref "B15") (pin "D2") (pinfunction "IN1_D2") (pintype "input"))
    )
    (net (code "14") (name "-TP00") (class "Default")
      (node (ref "B13") (pin "N1") (pinfunction "C_N1") (pintype "input"))
    )
    (net (code "15") (name "-TP0_XTLK_DY") (class "Default")
      (node (ref "A15") (pin "F2") (pinfunction "IN3_F2") (pintype "input"))
    )
    (net (code "16") (name "-TP01") (class "Default")
      (node (ref "B13") (pin "L2") (pinfunction "C_L2") (pintype "input"))
    )
    (net (code "17") (name "-TP1_XTLK_DY") (class "Default")
      (node (ref "A15") (pin "B1") (pinfunction "IN2_B1") (pintype "input"))
    )
    (net (code "18") (name "-U+M_DY") (class "Default")
      (node (ref "C12") (pin "R2") (pinfunction "IN3_R2") (pintype "input"))
      (node (ref "D14") (pin "N1") (pinfunction "N1_N1") (pintype "input"))
    )
    (net (code "19") (name "-WRITE_OK") (class "Default")
      (node (ref "A10") (pin "J1") (pinfunction "IN2_J1") (pintype "input"))
      (node (ref "C17") (pin "J2") (pinfunction "OUT_J2") (pintype "output"))
    )
    (net (code "20") (name "-WRTM") (class "Default")
      (node (ref "C10") (pin "M2") (pinfunction "IN2A_M2") (pintype "input"))
    )
    (net (code "21") (name "00") (class "Default")
      (node (ref "A07") (pin "D2") (pinfunction "O0_D2") (pintype "output"))
    )
    (net (code "22") (name "0_TO_DTB") (class "Default")
      (node (ref "A11") (pin "M1") (pinfunction "OUT_M1") (pintype "output"))
      (node (ref "C11") (pin "R1") (pinfunction "IN2_R1") (pintype "input"))
    )
    (net (code "23") (name "0_TO_EF") (class "Default")
      (node (ref "A10") (pin "K2") (pinfunction "OUT_K2") (pintype "output"))
      (node (ref "A11") (pin "E2") (pinfunction "IN_E2") (pintype "input"))
    )
    (net (code "24") (name "0_TO_STA") (class "Default")
      (node (ref "A10") (pin "N2") (pinfunction "OUT_N2") (pintype "output"))
      (node (ref "A11") (pin "N1") (pinfunction "IN_N1") (pintype "input"))
    )
    (net (code "25") (name "01") (class "Default")
      (node (ref "A07") (pin "E2") (pinfunction "O1_E2") (pintype "output"))
    )
    (net (code "26") (name "1_TO_DF") (class "Default")
      (node (ref "A08") (pin "H1") (pinfunction "C_H1") (pintype "input"))
      (node (ref "C12") (pin "J1") (pinfunction "OUT_J1") (pintype "output"))
      (node (ref "C12") (pin "L1") (pinfunction "IN2_L1") (pintype "input"))
      (node (ref "D11") (pin "L2") (pinfunction "C_L2") (pintype "input"))
    )
    (net (code "27") (name "1_TO_DTF") (class "Default")
      (node (ref "B12") (pin "P2") (pinfunction "OUT_P2") (pintype "output"))
      (node (ref "D11") (pin "S2") (pinfunction "C_S2") (pintype "input"))
    )
    (net (code "28") (name "02") (class "Default")
      (node (ref "A07") (pin "J2") (pinfunction "O2_J2") (pintype "output"))
    )
    (net (code "29") (name "03") (class "Default")
      (node (ref "A07") (pin "N2") (pinfunction "O3_N2") (pintype "output"))
    )
    (net (code "30") (name "04") (class "Default")
      (node (ref "A07") (pin "F2") (pinfunction "O4_F2") (pintype "output"))
    )
    (net (code "31") (name "05") (class "Default")
      (node (ref "A07") (pin "M2") (pinfunction "O5_M2") (pintype "output"))
    )
    (net (code "32") (name "06") (class "Default")
      (node (ref "A07") (pin "H2") (pinfunction "O6_H2") (pintype "output"))
    )
    (net (code "33") (name "07") (class "Default")
      (node (ref "A07") (pin "L2") (pinfunction "O7_L2") (pintype "output"))
    )
    (net (code "34") (name "76") (class "Default")
      (node (ref "C04") (pin "V2") (pinfunction "V2_V2") (pintype "output"))
      (node (ref "C06") (pin "S2") (pinfunction "IN_S2") (pintype "input"))
    )
    (net (code "35") (name "76+77") (class "Default")
      (node (ref "C03") (pin "C1") (pinfunction "ENABLE_C1") (pintype "input"))
      (node (ref "D12") (pin "V2") (pinfunction "OUT_V2") (pintype "output"))
    )
    (net (code "36") (name "77") (class "Default")
      (node (ref "C05") (pin "V2") (pinfunction "V2_V2") (pintype "output"))
      (node (ref "C06") (pin "U2") (pinfunction "IN_U2") (pintype "input"))
    )
    (net (code "37") (name "B-BRK") (class "Default")
      (node (ref "B10") (pin "R2") (pinfunction "IN1_R2") (pintype "input"))
      (node (ref "B10") (pin "S2") (pinfunction "IN2_S2") (pintype "input"))
      (node (ref "B10") (pin "T2") (pinfunction "IN3_T2") (pintype "input"))
      (node (ref "B10") (pin "U2") (pinfunction "IN4_U2") (pintype "input"))
      (node (ref "C01") (pin "E1") (pinfunction "OUT_E1") (pintype "output"))
      (node (ref "D12") (pin "M1") (pinfunction "IN1_M1") (pintype "input"))
    )
    (net (code "38") (name "B-RUN") (class "Default")
      (node (ref "B11") (pin "N2") (pinfunction "IN1_N2") (pintype "input"))
      (node (ref "C01") (pin "B1") (pinfunction "OUT_B1") (pintype "output"))
    )
    (net (code "39") (name "B-XSTA") (class "Default")
      (node (ref "A10") (pin "E2") (pinfunction "IN2_E2") (pintype "input"))
      (node (ref "C11") (pin "P2") (pinfunction "IN1_P2") (pintype "input"))
      (node (ref "D12") (pin "E1") (pinfunction "OUT_E1") (pintype "output"))
    )
    (net (code "40") (name "BAC_00") (class "Default")
      (node (ref "B06") (pin "B1") (pinfunction "OUT_B1") (pintype "output"))
      (node (ref "B07") (pin "C1") (pinfunction "C1_C1") (pintype "input"))
      (node (ref "B07") (pin "D1") (pinfunction "D1_D1") (pintype "input"))
    )
    (net (code "41") (name "BAC_01") (class "Default")
      (node (ref "B06") (pin "E1") (pinfunction "OUT_E1") (pintype "output"))
      (node (ref "B07") (pin "E2") (pinfunction "E2_E2") (pintype "input"))
      (node (ref "B07") (pin "F2") (pinfunction "F2_F2") (pintype "input"))
    )
    (net (code "42") (name "BAC_02") (class "Default")
      (node (ref "B06") (pin "H1") (pinfunction "OUT_H1") (pintype "output"))
      (node (ref "B07") (pin "J1") (pinfunction "J1_J1") (pintype "input"))
      (node (ref "B07") (pin "K1") (pinfunction "K1_K1") (pintype "input"))
    )
    (net (code "43") (name "BAC_03") (class "Default")
      (node (ref "B06") (pin "K1") (pinfunction "OUT_K1") (pintype "output"))
      (node (ref "B07") (pin "M2") (pinfunction "M2_M2") (pintype "input"))
      (node (ref "B07") (pin "N2") (pinfunction "N2_N2") (pintype "input"))
    )
    (net (code "44") (name "BAC_04") (class "Default")
      (node (ref "B06") (pin "M1") (pinfunction "OUT_M1") (pintype "output"))
      (node (ref "C07") (pin "M2") (pinfunction "M2_M2") (pintype "input"))
      (node (ref "C07") (pin "N2") (pinfunction "N2_N2") (pintype "input"))
    )
    (net (code "45") (name "BAC_05") (class "Default")
      (node (ref "B06") (pin "P1") (pinfunction "OUT_P1") (pintype "output"))
      (node (ref "B07") (pin "P1") (pinfunction "P1_P1") (pintype "input"))
      (node (ref "B07") (pin "R1") (pinfunction "R1_R1") (pintype "input"))
    )
    (net (code "46") (name "BAC_06") (class "Default")
      (node (ref "B06") (pin "S1") (pinfunction "OUT_S1") (pintype "output"))
      (node (ref "B07") (pin "T2") (pinfunction "T2_T2") (pintype "input"))
      (node (ref "B07") (pin "U2") (pinfunction "U2_U2") (pintype "input"))
      (node (ref "D11") (pin "C1") (pinfunction "D_C1") (pintype "input"))
    )
    (net (code "47") (name "BAC_07") (class "Default")
      (node (ref "B06") (pin "U1") (pinfunction "OUT_U1") (pintype "output"))
      (node (ref "C07") (pin "C1") (pinfunction "C1_C1") (pintype "input"))
      (node (ref "C07") (pin "D1") (pinfunction "D1_D1") (pintype "input"))
      (node (ref "D11") (pin "E2") (pinfunction "D_E2") (pintype "input"))
    )
    (net (code "48") (name "BAC_08") (class "Default")
      (node (ref "B06") (pin "D2") (pinfunction "OUT_D2") (pintype "output"))
      (node (ref "C07") (pin "E2") (pinfunction "E2_E2") (pintype "input"))
      (node (ref "C07") (pin "F2") (pinfunction "F2_F2") (pintype "input"))
      (node (ref "D11") (pin "J1") (pinfunction "D_J1") (pintype "input"))
    )
    (net (code "49") (name "BAC_09") (class "Default")
      (node (ref "B06") (pin "F2") (pinfunction "OUT_F2") (pintype "output"))
      (node (ref "C07") (pin "J1") (pinfunction "J1_J1") (pintype "input"))
      (node (ref "C07") (pin "K1") (pinfunction "K1_K1") (pintype "input"))
    )
    (net (code "50") (name "BAC_10") (class "Default")
      (node (ref "B06") (pin "J2") (pinfunction "OUT_J2") (pintype "output"))
    )
    (net (code "51") (name "BAC_11") (class "Default")
      (node (ref "B06") (pin "L2") (pinfunction "OUT_L2") (pintype "output"))
    )
    (net (code "52") (name "BLK_IN_SYNC") (class "Default")
      (node (ref "C11") (pin "E2") (pinfunction "IN2_E2") (pintype "input"))
      (node (ref "C13") (pin "S1") (pinfunction "OUT_S1") (pintype "output"))
      (node (ref "CD18") (pin "AP2") (pinfunction "AP2_AP2") (pintype "input"))
    )
    (net (code "53") (name "BMB_00") (class "Default")
      (node (ref "C06") (pin "B1") (pinfunction "OUT_B1") (pintype "output"))
      (node (ref "C08") (pin "B1") (pinfunction "IN1B_B1") (pintype "input"))
    )
    (net (code "54") (name "BMB_01") (class "Default")
      (node (ref "C06") (pin "E1") (pinfunction "OUT_E1") (pintype "output"))
      (node (ref "C08") (pin "H1") (pinfunction "IN1B_H1") (pintype "input"))
    )
    (net (code "55") (name "BMB_02") (class "Default")
      (node (ref "C06") (pin "H1") (pinfunction "OUT_H1") (pintype "output"))
      (node (ref "C08") (pin "N1") (pinfunction "IN1B_N1") (pintype "input"))
    )
    (net (code "56") (name "BMB_03") (class "Default")
      (node (ref "C06") (pin "K1") (pinfunction "OUT_K1") (pintype "output"))
      (node (ref "C08") (pin "E2") (pinfunction "IN1B_E2") (pintype "input"))
    )
    (net (code "57") (name "BMB_04") (class "Default")
      (node (ref "C06") (pin "M1") (pinfunction "OUT_M1") (pintype "output"))
      (node (ref "C08") (pin "L2") (pinfunction "IN1B_L2") (pintype "input"))
    )
    (net (code "58") (name "BMB_05") (class "Default")
      (node (ref "C06") (pin "P1") (pinfunction "OUT_P1") (pintype "output"))
      (node (ref "C08") (pin "S2") (pinfunction "IN1B_S2") (pintype "input"))
    )
    (net (code "59") (name "BMB_06") (class "Default")
      (node (ref "B08") (pin "B1") (pinfunction "IN2_B1") (pintype "input"))
      (node (ref "C06") (pin "S1") (pinfunction "OUT_S1") (pintype "output"))
    )
    (net (code "60") (name "BMB_07") (class "Default")
      (node (ref "B08") (pin "E1") (pinfunction "IN2_E1") (pintype "input"))
      (node (ref "C06") (pin "U1") (pinfunction "OUT_U1") (pintype "output"))
    )
    (net (code "61") (name "BMB_08") (class "Default")
      (node (ref "B08") (pin "E2") (pinfunction "IN2_E2") (pintype "input"))
      (node (ref "C06") (pin "D2") (pinfunction "OUT_D2") (pintype "output"))
    )
    (net (code "62") (name "BMB_09") (class "Default")
      (node (ref "B08") (pin "M1") (pinfunction "IN2_M1") (pintype "input"))
      (node (ref "C06") (pin "F2") (pinfunction "OUT_F2") (pintype "output"))
    )
    (net (code "63") (name "BMB_10") (class "Default")
      (node (ref "B08") (pin "R1") (pinfunction "IN2_R1") (pintype "input"))
      (node (ref "C06") (pin "J2") (pinfunction "OUT_J2") (pintype "output"))
    )
    (net (code "64") (name "BMB_11") (class "Default")
      (node (ref "B08") (pin "J1") (pinfunction "IN2_J1") (pintype "input"))
      (node (ref "C06") (pin "L2") (pinfunction "OUT_L2") (pintype "output"))
    )
    (net (code "65") (name "BMB_TO_DTB") (class "Default")
      (node (ref "B08") (pin "A1") (pinfunction "IN1_A1") (pintype "input"))
      (node (ref "B08") (pin "D1") (pinfunction "IN1_D1") (pintype "input"))
      (node (ref "B08") (pin "D2") (pinfunction "IN1_D2") (pintype "input"))
      (node (ref "B08") (pin "H1") (pinfunction "IN1_H1") (pintype "input"))
      (node (ref "B08") (pin "L1") (pinfunction "IN1_L1") (pintype "input"))
      (node (ref "B08") (pin "P1") (pinfunction "IN1_P1") (pintype "input"))
      (node (ref "C08") (pin "A1") (pinfunction "IN1A_A1") (pintype "input"))
      (node (ref "C08") (pin "D2") (pinfunction "IN1A_D2") (pintype "input"))
      (node (ref "C08") (pin "F1") (pinfunction "IN1A_F1") (pintype "input"))
      (node (ref "C08") (pin "K2") (pinfunction "IN1A_K2") (pintype "input"))
      (node (ref "C08") (pin "M1") (pinfunction "IN1A_M1") (pintype "input"))
      (node (ref "C08") (pin "R2") (pinfunction "IN1A_R2") (pintype "input"))
      (node (ref "D12") (pin "L1") (pinfunction "OUT_L1") (pintype "output"))
    )
    (net (code "66") (name "BMR00") (class "Default")
      (node (ref "A23") (pin "F1") (pinfunction "A_F1") (pintype "input"))
      (node (ref "B14") (pin "P2") (pinfunction "1_P2") (pintype "output"))
    )
    (net (code "67") (name "BMR01") (class "Default")
      (node (ref "A23") (pin "B1") (pinfunction "B_B1") (pintype "input"))
      (node (ref "B14") (pin "F1") (pinfunction "0_F1") (pintype "output"))
    )
    (net (code "68") (name "C00") (class "Default")
      (node (ref "A12") (pin "L2") (pinfunction "IN1_L2") (pintype "input"))
      (node (ref "A26") (pin "E2") (pinfunction "P$2_E2") (pintype "bidirectional"))
      (node (ref "B12") (pin "R2") (pinfunction "IN1_R2") (pintype "input"))
      (node (ref "B13") (pin "S1") (pinfunction "1_S1") (pintype "output"))
      (node (ref "C15") (pin "E2") (pinfunction "IN2_E2") (pintype "input"))
      (node (ref "D10") (pin "C1") (pinfunction "IN3_C1") (pintype "input"))
    )
    (net (code "69") (name "C01") (class "Default")
      (node (ref "A12") (pin "M2") (pinfunction "IN2_M2") (pintype "input"))
      (node (ref "A26") (pin "F2") (pinfunction "P$2_F2") (pintype "bidirectional"))
      (node (ref "B10") (pin "J1") (pinfunction "IN3_J1") (pintype "input"))
      (node (ref "B11") (pin "V2") (pinfunction "IN3_V2") (pintype "input"))
      (node (ref "B13") (pin "P2") (pinfunction "1_P2") (pintype "output"))
    )
    (net (code "70") (name "CK00") (class "Default")
      (node (ref "A18") (pin "P2") (pinfunction "P2_P2") (pintype "input"))
      (node (ref "B14") (pin "S1") (pinfunction "1_S1") (pintype "output"))
    )
    (net (code "71") (name "CK01") (class "Default")
      (node (ref "B14") (pin "P1") (pinfunction "D_P1") (pintype "input"))
      (node (ref "B14") (pin "V2") (pinfunction "1_V2") (pintype "output"))
      (node (ref "C16") (pin "N1") (pinfunction "IN2_N1") (pintype "input"))
      (node (ref "C16") (pin "P1") (pinfunction "IN3_P1") (pintype "input"))
      (node (ref "C16") (pin "R1") (pinfunction "IN4_R1") (pintype "input"))
    )
    (net (code "72") (name "COMP+SH") (class "Default")
      (node (ref "A12") (pin "D2") (pinfunction "IN1_D2") (pintype "input"))
      (node (ref "C14") (pin "B1") (pinfunction "C_B1") (pintype "input"))
      (node (ref "C14") (pin "D2") (pinfunction "C_D2") (pintype "input"))
      (node (ref "C14") (pin "H1") (pinfunction "C_H1") (pintype "input"))
      (node (ref "C15") (pin "K1") (pinfunction "OUT_K1") (pintype "output"))
    )
    (net (code "73") (name "CSTA") (class "Default")
      (node (ref "C04") (pin "D1") (pinfunction "D1_D1") (pintype "output"))
      (node (ref "D16") (pin "P2") (pinfunction "K2_P2") (pintype "input"))
    )
    (net (code "74") (name "DATA") (class "Default")
      (node (ref "A26") (pin "M1") (pinfunction "P$2_M1") (pintype "bidirectional"))
      (node (ref "C13") (pin "F1") (pinfunction "IN_F1") (pintype "input"))
      (node (ref "CD18") (pin "BK2") (pinfunction "BK2_BK2") (pintype "output"))
    )
    (net (code "75") (name "DF") (class "Default")
      (node (ref "A10") (pin "P2") (pinfunction "IN1_P2") (pintype "input"))
      (node (ref "A26") (pin "E1") (pinfunction "P$2_E1") (pintype "bidirectional"))
      (node (ref "D11") (pin "R2") (pinfunction "0_R2") (pintype "output"))
    )
    (net (code "76") (name "DTB_00") (class "Default")
      (node (ref "A25") (pin "A2") (pinfunction "P$2_A2") (pintype "bidirectional"))
      (node (ref "C09") (pin "E1") (pinfunction "1_E1") (pintype "output"))
      (node (ref "C10") (pin "B1") (pinfunction "IN1B_B1") (pintype "input"))
      (node (ref "D09") (pin "D2") (pinfunction "IN1A_D2") (pintype "input"))
    )
    (net (code "77") (name "DTB_01") (class "Default")
      (node (ref "A25") (pin "B2") (pinfunction "P$2_B2") (pintype "bidirectional"))
      (node (ref "C09") (pin "H2") (pinfunction "1_H2") (pintype "output"))
      (node (ref "C10") (pin "H1") (pinfunction "IN1B_H1") (pintype "input"))
      (node (ref "D09") (pin "K2") (pinfunction "IN1A_K2") (pintype "input"))
    )
    (net (code "78") (name "DTB_02") (class "Default")
      (node (ref "A25") (pin "C2") (pinfunction "P$2_C2") (pintype "bidirectional"))
      (node (ref "C09") (pin "L1") (pinfunction "1_L1") (pintype "output"))
      (node (ref "C10") (pin "N1") (pinfunction "IN1B_N1") (pintype "input"))
      (node (ref "D09") (pin "R2") (pinfunction "IN1A_R2") (pintype "input"))
    )
    (net (code "79") (name "DTB_03") (class "Default")
      (node (ref "A25") (pin "D2") (pinfunction "P$2_D2") (pintype "bidirectional"))
      (node (ref "C09") (pin "C1") (pinfunction "D_C1") (pintype "input"))
      (node (ref "C09") (pin "P2") (pinfunction "1_P2") (pintype "output"))
    )
    (net (code "80") (name "DTB_04") (class "Default")
      (node (ref "A25") (pin "E2") (pinfunction "P$2_E2") (pintype "bidirectional"))
      (node (ref "C09") (pin "E2") (pinfunction "D_E2") (pintype "input"))
      (node (ref "C09") (pin "S1") (pinfunction "1_S1") (pintype "output"))
    )
    (net (code "81") (name "DTB_05") (class "Default")
      (node (ref "A25") (pin "F2") (pinfunction "P$2_F2") (pintype "bidirectional"))
      (node (ref "C09") (pin "J1") (pinfunction "D_J1") (pintype "input"))
      (node (ref "C09") (pin "V2") (pinfunction "1_V2") (pintype "output"))
    )
    (net (code "82") (name "DTB_06") (class "Default")
      (node (ref "A25") (pin "H2") (pinfunction "P$2_H2") (pintype "bidirectional"))
      (node (ref "B09") (pin "E1") (pinfunction "1_E1") (pintype "output"))
      (node (ref "C09") (pin "M2") (pinfunction "D_M2") (pintype "input"))
    )
    (net (code "83") (name "DTB_07") (class "Default")
      (node (ref "A25") (pin "J2") (pinfunction "P$2_J2") (pintype "bidirectional"))
      (node (ref "B09") (pin "V2") (pinfunction "1_V2") (pintype "output"))
      (node (ref "C09") (pin "P1") (pinfunction "D_P1") (pintype "input"))
    )
    (net (code "84") (name "DTB_08") (class "Default")
      (node (ref "A25") (pin "K2") (pinfunction "P$2_K2") (pintype "bidirectional"))
      (node (ref "B09") (pin "L1") (pinfunction "1_L1") (pintype "output"))
      (node (ref "C09") (pin "T2") (pinfunction "D_T2") (pintype "input"))
    )
    (net (code "85") (name "DTB_09") (class "Default")
      (node (ref "A25") (pin "L2") (pinfunction "P$2_L2") (pintype "bidirectional"))
      (node (ref "B09") (pin "C1") (pinfunction "D_C1") (pintype "input"))
      (node (ref "B09") (pin "P2") (pinfunction "1_P2") (pintype "output"))
    )
    (net (code "86") (name "DTB_10") (class "Default")
      (node (ref "A25") (pin "M2") (pinfunction "P$2_M2") (pintype "bidirectional"))
      (node (ref "B09") (pin "S1") (pinfunction "1_S1") (pintype "output"))
      (node (ref "B09") (pin "T2") (pinfunction "D_T2") (pintype "input"))
    )
    (net (code "87") (name "DTB_11") (class "Default")
      (node (ref "A25") (pin "N2") (pinfunction "P$2_N2") (pintype "bidirectional"))
      (node (ref "B09") (pin "H2") (pinfunction "1_H2") (pintype "output"))
      (node (ref "B09") (pin "J1") (pinfunction "D_J1") (pintype "input"))
    )
    (net (code "88") (name "DTF") (class "Default")
      (node (ref "A08") (pin "J1") (pinfunction "D_J1") (pintype "input"))
      (node (ref "A12") (pin "M1") (pinfunction "IN2_M1") (pintype "input"))
      (node (ref "A26") (pin "C1") (pinfunction "P$2_C1") (pintype "bidirectional"))
      (node (ref "D11") (pin "V1") (pinfunction "0_V1") (pintype "output"))
    )
    (net (code "89") (name "DTSF") (class "Default")
      (node (ref "A12") (pin "R1") (pinfunction "IN2_R1") (pintype "input"))
      (node (ref "C05") (pin "B1") (pinfunction "B1_B1") (pintype "output"))
    )
    (net (code "90") (name "EF") (class "Default")
      (node (ref "A11") (pin "J1") (pinfunction "IN_J1") (pintype "input"))
      (node (ref "A12") (pin "F1") (pinfunction "OUT_F1") (pintype "output"))
      (node (ref "A12") (pin "L1") (pinfunction "IN1_L1") (pintype "input"))
      (node (ref "A25") (pin "N1") (pinfunction "P$2_N1") (pintype "bidirectional"))
    )
    (net (code "91") (name "END") (class "Default")
      (node (ref "A08") (pin "E1") (pinfunction "1_E1") (pintype "output"))
      (node (ref "A25") (pin "R1") (pinfunction "P$2_R1") (pintype "bidirectional"))
    )
    (net (code "92") (name "ENI") (class "Default")
      (node (ref "A12") (pin "H1") (pinfunction "IN1_H1") (pintype "input"))
      (node (ref "A25") (pin "L1") (pinfunction "P$2_L1") (pintype "bidirectional"))
      (node (ref "C07") (pin "L1") (pinfunction "L1_L1") (pintype "output"))
    )
    (net (code "93") (name "FR_00") (class "Default")
      (node (ref "A25") (pin "F1") (pinfunction "P$2_F1") (pintype "bidirectional"))
      (node (ref "B07") (pin "S1") (pinfunction "S1_S1") (pintype "output"))
      (node (ref "B12") (pin "E2") (pinfunction "IN2_E2") (pintype "input"))
      (node (ref "C12") (pin "U2") (pinfunction "IN2_U2") (pintype "input"))
    )
    (net (code "94") (name "FR_01") (class "Default")
      (node (ref "A10") (pin "H1") (pinfunction "IN1_H1") (pintype "input"))
      (node (ref "A25") (pin "H1") (pinfunction "P$2_H1") (pintype "bidirectional"))
      (node (ref "B07") (pin "V2") (pinfunction "V2_V2") (pintype "output"))
      (node (ref "B15") (pin "M1") (pinfunction "IN2_M1") (pintype "input"))
      (node (ref "C15") (pin "D1") (pinfunction "IN1_D1") (pintype "input"))
      (node (ref "D07") (pin "V2") (pinfunction "IN2_V2") (pintype "input"))
      (node (ref "D12") (pin "R1") (pinfunction "IN4_R1") (pintype "input"))
    )
    (net (code "95") (name "FR_02") (class "Default")
      (node (ref "A25") (pin "J1") (pinfunction "P$2_J1") (pintype "bidirectional"))
      (node (ref "C07") (pin "E1") (pinfunction "E1_E1") (pintype "output"))
      (node (ref "D07") (pin "U2") (pinfunction "IN1_U2") (pintype "input"))
    )
    (net (code "96") (name "FR_03") (class "Default")
      (node (ref "A25") (pin "K1") (pinfunction "P$2_K1") (pintype "bidirectional"))
      (node (ref "B15") (pin "R2") (pinfunction "IN2_R2") (pintype "input"))
      (node (ref "C07") (pin "H2") (pinfunction "H2_H2") (pintype "output"))
      (node (ref "D07") (pin "V1") (pinfunction "IN0_V1") (pintype "input"))
    )
    (net (code "97") (name "GND") (class "Default")
      (node (ref "A05") (pin "B1") (pinfunction "P$2_B1") (pintype "bidirectional"))
      (node (ref "A05") (pin "D1") (pinfunction "P$2_D1") (pintype "bidirectional"))
      (node (ref "A05") (pin "D2") (pinfunction "P$2_D2") (pintype "bidirectional"))
      (node (ref "A05") (pin "E1") (pinfunction "P$2_E1") (pintype "bidirectional"))
      (node (ref "A05") (pin "H1") (pinfunction "P$2_H1") (pintype "bidirectional"))
      (node (ref "A05") (pin "J1") (pinfunction "P$2_J1") (pintype "bidirectional"))
      (node (ref "A05") (pin "L1") (pinfunction "P$2_L1") (pintype "bidirectional"))
      (node (ref "A05") (pin "M1") (pinfunction "P$2_M1") (pintype "bidirectional"))
      (node (ref "A05") (pin "P1") (pinfunction "P$2_P1") (pintype "bidirectional"))
      (node (ref "A05") (pin "S1") (pinfunction "P$2_S1") (pintype "bidirectional"))
      (node (ref "A06") (pin "K2") (pinfunction "P$2_K2") (pintype "bidirectional"))
      (node (ref "A07") (pin "U1") (pinfunction "IN*_U1") (pintype "input"))
      (node (ref "A08") (pin "T2") (pinfunction "D_T2") (pintype "input"))
      (node (ref "A23") (pin "C1") (pinfunction "C_C1") (pintype "input"))
      (node (ref "A23") (pin "F2") (pinfunction "C_F2") (pintype "input"))
      (node (ref "A23") (pin "J1") (pinfunction "C_J1") (pintype "input"))
      (node (ref "A23") (pin "M2") (pinfunction "C_M2") (pintype "input"))
      (node (ref "A23") (pin "P1") (pinfunction "C_P1") (pintype "input"))
      (node (ref "A23") (pin "T2") (pinfunction "C_T2") (pintype "input"))
      (node (ref "A25") (pin "M1") (pinfunction "P$2_M1") (pintype "bidirectional"))
      (node (ref "A26") (pin "D2") (pinfunction "P$2_D2") (pintype "bidirectional"))
      (node (ref "A26") (pin "U2") (pinfunction "P$2_U2") (pintype "bidirectional"))
      (node (ref "A26") (pin "V1") (pinfunction "P$2_V1") (pintype "bidirectional"))
      (node (ref "AB01") (pin "AC2") (pinfunction "GND_AC2") (pintype "power_in"))
      (node (ref "AB01") (pin "AH2") (pinfunction "GND_AH2") (pintype "power_in"))
      (node (ref "AB01") (pin "AK2") (pinfunction "GND_AK2") (pintype "power_in"))
      (node (ref "AB01") (pin "AL2") (pinfunction "GND_AL2") (pintype "power_in"))
      (node (ref "AB01") (pin "AT1") (pinfunction "GND_AT1") (pintype "power_in"))
      (node (ref "AB01") (pin "BC2") (pinfunction "GND_BC2") (pintype "power_in"))
      (node (ref "AB01") (pin "BD2") (pinfunction "GND_BD2") (pintype "power_in"))
      (node (ref "AB01") (pin "BH2") (pinfunction "GND_BH2") (pintype "power_in"))
      (node (ref "AB01") (pin "BK2") (pinfunction "GND_BK2") (pintype "power_in"))
      (node (ref "AB01") (pin "BL2") (pinfunction "GND_BL2") (pintype "power_in"))
      (node (ref "AB01") (pin "BT1") (pinfunction "GND_BT1") (pintype "power_in"))
      (node (ref "AB19") (pin "AJ2") (pinfunction "P$2_AJ2") (pintype "bidirectional"))
      (node (ref "AB19") (pin "AR2") (pinfunction "P$2_AR2") (pintype "bidirectional"))
      (node (ref "AB19") (pin "AU2") (pinfunction "P$2_AU2") (pintype "bidirectional"))
      (node (ref "AB19") (pin "BF2") (pinfunction "P$2_BF2") (pintype "bidirectional"))
      (node (ref "AB19") (pin "BM2") (pinfunction "P$2_BM2") (pintype "bidirectional"))
      (node (ref "B05") (pin "C1") (pinfunction "C_C1") (pintype "input"))
      (node (ref "B05") (pin "F2") (pinfunction "C_F2") (pintype "input"))
      (node (ref "B05") (pin "J1") (pinfunction "C_J1") (pintype "input"))
      (node (ref "B05") (pin "M2") (pinfunction "C_M2") (pintype "input"))
      (node (ref "B05") (pin "P1") (pinfunction "C_P1") (pintype "input"))
      (node (ref "B22") (pin "T2") (pinfunction "C_T2") (pintype "input"))
      (node (ref "D05") (pin "B1") (pinfunction "P$2_B1") (pintype "bidirectional"))
      (node (ref "D05") (pin "D1") (pinfunction "P$2_D1") (pintype "bidirectional"))
      (node (ref "D05") (pin "D2") (pinfunction "P$2_D2") (pintype "bidirectional"))
      (node (ref "D05") (pin "E1") (pinfunction "P$2_E1") (pintype "bidirectional"))
      (node (ref "D05") (pin "H1") (pinfunction "P$2_H1") (pintype "bidirectional"))
      (node (ref "D05") (pin "J1") (pinfunction "P$2_J1") (pintype "bidirectional"))
      (node (ref "D05") (pin "L1") (pinfunction "P$2_L1") (pintype "bidirectional"))
      (node (ref "D05") (pin "M1") (pinfunction "P$2_M1") (pintype "bidirectional"))
      (node (ref "D05") (pin "P1") (pinfunction "P$2_P1") (pintype "bidirectional"))
      (node (ref "D05") (pin "S1") (pinfunction "P$2_S1") (pintype "bidirectional"))
      (node (ref "D06") (pin "K2") (pinfunction "P$2_K2") (pintype "bidirectional"))
      (node (ref "D07") (pin "U1") (pinfunction "IN*_U1") (pintype "input"))
      (node (ref "D11") (pin "P1") (pinfunction "D_P1") (pintype "input"))
      (node (ref "D11") (pin "T2") (pinfunction "D_T2") (pintype "input"))
    )
    (net (code "98") (name "IOP_1") (class "Default")
      (node (ref "A02") (pin "K2") (pinfunction "P$2_K2") (pintype "bidirectional"))
      (node (ref "C04") (pin "P2") (pinfunction "P2_P2") (pintype "input"))
      (node (ref "C05") (pin "P2") (pinfunction "P2_P2") (pintype "input"))
      (node (ref "D02") (pin "K2") (pinfunction "P$2_K2") (pintype "bidirectional"))
    )
    (net (code "99") (name "IOP_2") (class "Default")
      (node (ref "A02") (pin "M2") (pinfunction "P$2_M2") (pintype "bidirectional"))
      (node (ref "C04") (pin "R2") (pinfunction "R2_R2") (pintype "input"))
      (node (ref "C05") (pin "R2") (pinfunction "R2_R2") (pintype "input"))
      (node (ref "D02") (pin "M2") (pinfunction "P$2_M2") (pintype "bidirectional"))
    )
    (net (code "100") (name "IOP_4") (class "Default")
      (node (ref "A02") (pin "P2") (pinfunction "P$2_P2") (pintype "bidirectional"))
      (node (ref "C04") (pin "S2") (pinfunction "S2_S2") (pintype "input"))
      (node (ref "C05") (pin "S2") (pinfunction "S2_S2") (pintype "input"))
      (node (ref "D02") (pin "P2") (pinfunction "P$2_P2") (pintype "bidirectional"))
    )
    (net (code "101") (name "I{slash}O_B-BRK") (class "Default")
      (node (ref "A05") (pin "P2") (pinfunction "P$2_P2") (pintype "bidirectional"))
      (node (ref "C01") (pin "D1") (pinfunction "IN_D1") (pintype "input"))
      (node (ref "D05") (pin "P2") (pinfunction "P$2_P2") (pintype "bidirectional"))
    )
    (net (code "102") (name "I{slash}O_B-RUN") (class "Default")
      (node (ref "A04") (pin "S2") (pinfunction "P$2_S2") (pintype "bidirectional"))
      (node (ref "C01") (pin "A1") (pinfunction "IN1_A1") (pintype "input"))
      (node (ref "D04") (pin "S2") (pinfunction "P$2_S2") (pintype "bidirectional"))
    )
    (net (code "103") (name "I{slash}O_BAC_00") (class "Default")
      (node (ref "A02") (pin "B1") (pinfunction "P$2_B1") (pintype "bidirectional"))
      (node (ref "C03") (pin "A1") (pinfunction "IN1_A1") (pintype "input"))
      (node (ref "D02") (pin "B1") (pinfunction "P$2_B1") (pintype "bidirectional"))
    )
    (net (code "104") (name "I{slash}O_BAC_01") (class "Default")
      (node (ref "A02") (pin "D1") (pinfunction "P$2_D1") (pintype "bidirectional"))
      (node (ref "C03") (pin "D1") (pinfunction "IN2_D1") (pintype "input"))
      (node (ref "D02") (pin "D1") (pinfunction "P$2_D1") (pintype "bidirectional"))
    )
    (net (code "105") (name "I{slash}O_BAC_02") (class "Default")
      (node (ref "A02") (pin "E1") (pinfunction "P$2_E1") (pintype "bidirectional"))
      (node (ref "C03") (pin "F1") (pinfunction "IN3_F1") (pintype "input"))
      (node (ref "D02") (pin "E1") (pinfunction "P$2_E1") (pintype "bidirectional"))
    )
    (net (code "106") (name "I{slash}O_BAC_03") (class "Default")
      (node (ref "A02") (pin "H1") (pinfunction "P$2_H1") (pintype "bidirectional"))
      (node (ref "C03") (pin "J1") (pinfunction "IN4_J1") (pintype "input"))
      (node (ref "D02") (pin "H1") (pinfunction "P$2_H1") (pintype "bidirectional"))
    )
    (net (code "107") (name "I{slash}O_BAC_04") (class "Default")
      (node (ref "A02") (pin "J1") (pinfunction "P$2_J1") (pintype "bidirectional"))
      (node (ref "C03") (pin "L1") (pinfunction "IN5_L1") (pintype "input"))
      (node (ref "D02") (pin "J1") (pinfunction "P$2_J1") (pintype "bidirectional"))
    )
    (net (code "108") (name "I{slash}O_BAC_05") (class "Default")
      (node (ref "A02") (pin "L1") (pinfunction "P$2_L1") (pintype "bidirectional"))
      (node (ref "C03") (pin "N1") (pinfunction "IN6_N1") (pintype "input"))
      (node (ref "D02") (pin "L1") (pinfunction "P$2_L1") (pintype "bidirectional"))
    )
    (net (code "109") (name "I{slash}O_BAC_06") (class "Default")
      (node (ref "A02") (pin "M1") (pinfunction "P$2_M1") (pintype "bidirectional"))
      (node (ref "C03") (pin "R1") (pinfunction "IN7_R1") (pintype "input"))
      (node (ref "D02") (pin "M1") (pinfunction "P$2_M1") (pintype "bidirectional"))
    )
    (net (code "110") (name "I{slash}O_BAC_07") (class "Default")
      (node (ref "A02") (pin "P1") (pinfunction "P$2_P1") (pintype "bidirectional"))
      (node (ref "C03") (pin "V1") (pinfunction "IN8_V1") (pintype "input"))
      (node (ref "D02") (pin "P1") (pinfunction "P$2_P1") (pintype "bidirectional"))
    )
    (net (code "111") (name "I{slash}O_BAC_08") (class "Default")
      (node (ref "A02") (pin "S1") (pinfunction "P$2_S1") (pintype "bidirectional"))
      (node (ref "C03") (pin "E2") (pinfunction "IN9_E2") (pintype "input"))
      (node (ref "D02") (pin "S1") (pinfunction "P$2_S1") (pintype "bidirectional"))
    )
    (net (code "112") (name "I{slash}O_BAC_09") (class "Default")
      (node (ref "A02") (pin "D2") (pinfunction "P$2_D2") (pintype "bidirectional"))
      (node (ref "C03") (pin "H2") (pinfunction "IN10_H2") (pintype "input"))
      (node (ref "D02") (pin "D2") (pinfunction "P$2_D2") (pintype "bidirectional"))
    )
    (net (code "113") (name "I{slash}O_BAC_10") (class "Default")
      (node (ref "A02") (pin "E2") (pinfunction "P$2_E2") (pintype "bidirectional"))
      (node (ref "C03") (pin "K2") (pinfunction "IN11_K2") (pintype "input"))
      (node (ref "D02") (pin "E2") (pinfunction "P$2_E2") (pintype "bidirectional"))
    )
    (net (code "114") (name "I{slash}O_BAC_11") (class "Default")
      (node (ref "A02") (pin "H2") (pinfunction "P$2_H2") (pintype "bidirectional"))
      (node (ref "C03") (pin "M2") (pinfunction "IN12_M2") (pintype "input"))
      (node (ref "D02") (pin "H2") (pinfunction "P$2_H2") (pintype "bidirectional"))
    )
    (net (code "115") (name "I{slash}O_BMB_00") (class "Default")
      (node (ref "A03") (pin "B1") (pinfunction "P$2_B1") (pintype "bidirectional"))
      (node (ref "C02") (pin "A1") (pinfunction "IN1_A1") (pintype "input"))
      (node (ref "D03") (pin "B1") (pinfunction "P$2_B1") (pintype "bidirectional"))
    )
    (net (code "116") (name "I{slash}O_BMB_01") (class "Default")
      (node (ref "A03") (pin "D1") (pinfunction "P$2_D1") (pintype "bidirectional"))
      (node (ref "C02") (pin "D1") (pinfunction "IN2_D1") (pintype "input"))
      (node (ref "D03") (pin "D1") (pinfunction "P$2_D1") (pintype "bidirectional"))
    )
    (net (code "117") (name "I{slash}O_BMB_02") (class "Default")
      (node (ref "A03") (pin "E1") (pinfunction "P$2_E1") (pintype "bidirectional"))
      (node (ref "C02") (pin "F1") (pinfunction "IN3_F1") (pintype "input"))
      (node (ref "D03") (pin "E1") (pinfunction "P$2_E1") (pintype "bidirectional"))
    )
    (net (code "118") (name "I{slash}O_BMB_03") (class "Default")
      (node (ref "A03") (pin "J1") (pinfunction "P$2_J1") (pintype "bidirectional"))
      (node (ref "C02") (pin "J1") (pinfunction "IN4_J1") (pintype "input"))
      (node (ref "C04") (pin "D2") (pinfunction "D2_D2") (pintype "input"))
      (node (ref "C05") (pin "D2") (pinfunction "D2_D2") (pintype "input"))
      (node (ref "D03") (pin "J1") (pinfunction "P$2_J1") (pintype "bidirectional"))
    )
    (net (code "119") (name "I{slash}O_BMB_04") (class "Default")
      (node (ref "A03") (pin "M1") (pinfunction "P$2_M1") (pintype "bidirectional"))
      (node (ref "C02") (pin "L1") (pinfunction "IN5_L1") (pintype "input"))
      (node (ref "C04") (pin "E2") (pinfunction "E2_E2") (pintype "input"))
      (node (ref "C05") (pin "E2") (pinfunction "E2_E2") (pintype "input"))
      (node (ref "D03") (pin "M1") (pinfunction "P$2_M1") (pintype "bidirectional"))
    )
    (net (code "120") (name "I{slash}O_BMB_05") (class "Default")
      (node (ref "A03") (pin "S1") (pinfunction "P$2_S1") (pintype "bidirectional"))
      (node (ref "C02") (pin "N1") (pinfunction "IN6_N1") (pintype "input"))
      (node (ref "C04") (pin "F2") (pinfunction "F2_F2") (pintype "input"))
      (node (ref "C05") (pin "F2") (pinfunction "F2_F2") (pintype "input"))
      (node (ref "D03") (pin "S1") (pinfunction "P$2_S1") (pintype "bidirectional"))
    )
    (net (code "121") (name "I{slash}O_BMB_06") (class "Default")
      (node (ref "A03") (pin "E2") (pinfunction "P$2_E2") (pintype "bidirectional"))
      (node (ref "C02") (pin "R1") (pinfunction "IN7_R1") (pintype "input"))
      (node (ref "C04") (pin "H2") (pinfunction "H2_H2") (pintype "input"))
      (node (ref "C05") (pin "H2") (pinfunction "H2_H2") (pintype "input"))
      (node (ref "D03") (pin "E2") (pinfunction "P$2_E2") (pintype "bidirectional"))
    )
    (net (code "122") (name "I{slash}O_BMB_07") (class "Default")
      (node (ref "A03") (pin "K2") (pinfunction "P$2_K2") (pintype "bidirectional"))
      (node (ref "C02") (pin "V1") (pinfunction "IN8_V1") (pintype "input"))
      (node (ref "C04") (pin "J2") (pinfunction "J2_J2") (pintype "input"))
      (node (ref "C05") (pin "J2") (pinfunction "J2_J2") (pintype "input"))
      (node (ref "D03") (pin "K2") (pinfunction "P$2_K2") (pintype "bidirectional"))
    )
    (net (code "123") (name "I{slash}O_BMB_08") (class "Default")
      (node (ref "A03") (pin "P2") (pinfunction "P$2_P2") (pintype "bidirectional"))
      (node (ref "C02") (pin "E2") (pinfunction "IN9_E2") (pintype "input"))
      (node (ref "C05") (pin "K2") (pinfunction "K2_K2") (pintype "input"))
      (node (ref "D03") (pin "P2") (pinfunction "P$2_P2") (pintype "bidirectional"))
    )
    (net (code "124") (name "I{slash}O_BMB_09") (class "Default")
      (node (ref "A03") (pin "S2") (pinfunction "P$2_S2") (pintype "bidirectional"))
      (node (ref "C02") (pin "H2") (pinfunction "IN10_H2") (pintype "input"))
      (node (ref "D03") (pin "S2") (pinfunction "P$2_S2") (pintype "bidirectional"))
    )
    (net (code "125") (name "I{slash}O_BMB_10") (class "Default")
      (node (ref "A03") (pin "T2") (pinfunction "P$2_T2") (pintype "bidirectional"))
      (node (ref "C02") (pin "K2") (pinfunction "IN11_K2") (pintype "input"))
      (node (ref "D03") (pin "T2") (pinfunction "P$2_T2") (pintype "bidirectional"))
    )
    (net (code "126") (name "I{slash}O_BMB_11") (class "Default")
      (node (ref "A03") (pin "V2") (pinfunction "P$2_V2") (pintype "bidirectional"))
      (node (ref "C02") (pin "M2") (pinfunction "IN12_M2") (pintype "input"))
      (node (ref "D03") (pin "V2") (pinfunction "P$2_V2") (pintype "bidirectional"))
    )
    (net (code "127") (name "I{slash}O_DATA_IN") (class "Default")
      (node (ref "A05") (pin "M2") (pinfunction "P$2_M2") (pintype "bidirectional"))
      (node (ref "B05") (pin "J2") (pinfunction "E_J2") (pintype "open_collector"))
      (node (ref "D05") (pin "M2") (pinfunction "P$2_M2") (pintype "bidirectional"))
    )
    (net (code "128") (name "I{slash}O_PWR_CLR") (class "Default")
      (node (ref "A02") (pin "V2") (pinfunction "P$2_V2") (pintype "bidirectional"))
      (node (ref "C05") (pin "H1") (pinfunction "IN1_H1") (pintype "input"))
      (node (ref "D02") (pin "V2") (pinfunction "P$2_V2") (pintype "bidirectional"))
    )
    (net (code "129") (name "I{slash}O_TS03") (class "Default")
      (node (ref "A02") (pin "S2") (pinfunction "P$2_S2") (pintype "bidirectional"))
      (node (ref "C04") (pin "H1") (pinfunction "IN1_H1") (pintype "input"))
      (node (ref "D02") (pin "S2") (pinfunction "P$2_S2") (pintype "bidirectional"))
    )
    (net (code "130") (name "I{slash}O_TS04") (class "Default")
      (node (ref "A02") (pin "T2") (pinfunction "P$2_T2") (pintype "bidirectional"))
      (node (ref "D02") (pin "T2") (pinfunction "P$2_T2") (pintype "bidirectional"))
    )
    (net (code "131") (name "I{slash}~{O_0_TO_AC}") (class "Default")
      (node (ref "A04") (pin "P2") (pinfunction "P$2_P2") (pintype "bidirectional"))
      (node (ref "B05") (pin "L1") (pinfunction "E_L1") (pintype "open_collector"))
      (node (ref "D04") (pin "P2") (pinfunction "P$2_P2") (pintype "bidirectional"))
    )
    (net (code "132") (name "I{slash}~{O_1_TO_CA_INH}") (class "Default")
      (node (ref "A06") (pin "M2") (pinfunction "P$2_M2") (pintype "bidirectional"))
      (node (ref "B05") (pin "N2") (pinfunction "D_N2") (pintype "open_collector"))
      (node (ref "D06") (pin "M2") (pinfunction "P$2_M2") (pintype "bidirectional"))
    )
    (net (code "133") (name "I{slash}~{O_ADDR_ACC}") (class "Default")
      (node (ref "A05") (pin "S2") (pinfunction "P$2_S2") (pintype "bidirectional"))
      (node (ref "C02") (pin "U2") (pinfunction "IN15_U2") (pintype "input"))
      (node (ref "D05") (pin "S2") (pinfunction "P$2_S2") (pintype "bidirectional"))
    )
    (net (code "134") (name "I{slash}~{O_BMB_03}") (class "Default")
      (node (ref "A03") (pin "H1") (pinfunction "P$2_H1") (pintype "bidirectional"))
      (node (ref "D03") (pin "H1") (pinfunction "P$2_H1") (pintype "bidirectional"))
    )
    (net (code "135") (name "I{slash}~{O_BMB_04}") (class "Default")
      (node (ref "A03") (pin "L1") (pinfunction "P$2_L1") (pintype "bidirectional"))
      (node (ref "D03") (pin "L1") (pinfunction "P$2_L1") (pintype "bidirectional"))
    )
    (net (code "136") (name "I{slash}~{O_BMB_05}") (class "Default")
      (node (ref "A03") (pin "P1") (pinfunction "P$2_P1") (pintype "bidirectional"))
      (node (ref "D03") (pin "P1") (pinfunction "P$2_P1") (pintype "bidirectional"))
    )
    (net (code "137") (name "I{slash}~{O_BMB_06}") (class "Default")
      (node (ref "A03") (pin "D2") (pinfunction "P$2_D2") (pintype "bidirectional"))
      (node (ref "D03") (pin "D2") (pinfunction "P$2_D2") (pintype "bidirectional"))
    )
    (net (code "138") (name "I{slash}~{O_BMB_07}") (class "Default")
      (node (ref "A03") (pin "H2") (pinfunction "P$2_H2") (pintype "bidirectional"))
      (node (ref "D03") (pin "H2") (pinfunction "P$2_H2") (pintype "bidirectional"))
    )
    (net (code "139") (name "I{slash}~{O_BMB_08}") (class "Default")
      (node (ref "A03") (pin "M2") (pinfunction "P$2_M2") (pintype "bidirectional"))
      (node (ref "C04") (pin "K2") (pinfunction "K2_K2") (pintype "input"))
      (node (ref "D03") (pin "M2") (pinfunction "P$2_M2") (pintype "bidirectional"))
    )
    (net (code "140") (name "I{slash}~{O_BRK_RQ}") (class "Default")
      (node (ref "A05") (pin "K2") (pinfunction "P$2_K2") (pintype "bidirectional"))
      (node (ref "B05") (pin "D1") (pinfunction "D_D1") (pintype "open_collector"))
      (node (ref "D05") (pin "K2") (pinfunction "P$2_K2") (pintype "bidirectional"))
    )
    (net (code "141") (name "I{slash}~{O_BWC0}") (class "Default")
      (node (ref "A06") (pin "P2") (pinfunction "P$2_P2") (pintype "bidirectional"))
      (node (ref "C01") (pin "F1") (pinfunction "IN_F1") (pintype "input"))
      (node (ref "D06") (pin "P2") (pinfunction "P$2_P2") (pintype "bidirectional"))
    )
    (net (code "142") (name "I{slash}~{O_INT_RQ}") (class "Default")
      (node (ref "A04") (pin "M2") (pinfunction "P$2_M2") (pintype "bidirectional"))
      (node (ref "B05") (pin "E1") (pinfunction "E_E1") (pintype "open_collector"))
      (node (ref "D04") (pin "M2") (pinfunction "P$2_M2") (pintype "bidirectional"))
    )
    (net (code "143") (name "I{slash}~{O_SKP_RQ}") (class "Default")
      (node (ref "A04") (pin "K2") (pinfunction "P$2_K2") (pintype "bidirectional"))
      (node (ref "B05") (pin "K1") (pinfunction "D_K1") (pintype "open_collector"))
      (node (ref "D04") (pin "K2") (pinfunction "P$2_K2") (pintype "bidirectional"))
    )
    (net (code "144") (name "LDMF") (class "Default")
      (node (ref "C05") (pin "F1") (pinfunction "F1_F1") (pintype "output"))
      (node (ref "D11") (pin "B1") (pinfunction "C_B1") (pintype "input"))
      (node (ref "D11") (pin "D2") (pinfunction "C_D2") (pintype "input"))
      (node (ref "D11") (pin "H1") (pinfunction "C_H1") (pintype "input"))
    )
    (net (code "145") (name "LPB_00") (class "Default")
      (node (ref "A25") (pin "T2") (pinfunction "P$2_T2") (pintype "bidirectional"))
      (node (ref "C08") (pin "D1") (pinfunction "IN2B_D1") (pintype "input"))
      (node (ref "D08") (pin "E1") (pinfunction "E1_E1") (pintype "output"))
    )
    (net (code "146") (name "LPB_01") (class "Default")
      (node (ref "A25") (pin "U2") (pinfunction "P$2_U2") (pintype "bidirectional"))
      (node (ref "C08") (pin "K1") (pinfunction "IN2B_K1") (pintype "input"))
      (node (ref "D08") (pin "L1") (pinfunction "L1_L1") (pintype "output"))
    )
    (net (code "147") (name "LPB_02") (class "Default")
      (node (ref "A25") (pin "V2") (pinfunction "P$2_V2") (pintype "bidirectional"))
      (node (ref "C08") (pin "R1") (pinfunction "IN2B_R1") (pintype "input"))
      (node (ref "D08") (pin "S1") (pinfunction "S1_S1") (pintype "output"))
    )
    (net (code "148") (name "LPB_03") (class "Default")
      (node (ref "A26") (pin "A2") (pinfunction "P$2_A2") (pintype "bidirectional"))
      (node (ref "C08") (pin "H2") (pinfunction "IN2B_H2") (pintype "input"))
      (node (ref "D08") (pin "H2") (pinfunction "H2_H2") (pintype "output"))
    )
    (net (code "149") (name "LPB_04") (class "Default")
      (node (ref "A26") (pin "B2") (pinfunction "P$2_B2") (pintype "bidirectional"))
      (node (ref "C08") (pin "N2") (pinfunction "IN2B_N2") (pintype "input"))
      (node (ref "D08") (pin "P2") (pinfunction "P2_P2") (pintype "output"))
    )
    (net (code "150") (name "LPB_05") (class "Default")
      (node (ref "A26") (pin "C2") (pinfunction "P$2_C2") (pintype "bidirectional"))
      (node (ref "C08") (pin "U2") (pinfunction "IN2B_U2") (pintype "input"))
      (node (ref "D08") (pin "V2") (pinfunction "V2_V2") (pintype "output"))
    )
    (net (code "151") (name "LPB_NOT_EQ_1") (class "Default")
      (node (ref "A10") (pin "M1") (pinfunction "IN2_M1") (pintype "input"))
      (node (ref "D10") (pin "V2") (pinfunction "OUT_V2") (pintype "output"))
    )
    (net (code "152") (name "LPB_TO_DTB") (class "Default")
      (node (ref "A11") (pin "T2") (pinfunction "OUT_T2") (pintype "output"))
      (node (ref "C08") (pin "C1") (pinfunction "IN2A_C1") (pintype "input"))
      (node (ref "C08") (pin "F2") (pinfunction "IN2A_F2") (pintype "input"))
      (node (ref "C08") (pin "J1") (pinfunction "IN2A_J1") (pintype "input"))
      (node (ref "C08") (pin "M2") (pinfunction "IN2A_M2") (pintype "input"))
      (node (ref "C08") (pin "P1") (pinfunction "IN2A_P1") (pintype "input"))
      (node (ref "C08") (pin "T2") (pinfunction "IN2A_T2") (pintype "input"))
    )
    (net (code "153") (name "MC00") (class "Default")
      (node (ref "A26") (pin "S1") (pinfunction "P$2_S1") (pintype "bidirectional"))
      (node (ref "B13") (pin "E1") (pinfunction "1_E1") (pintype "output"))
      (node (ref "B13") (pin "E2") (pinfunction "D_E2") (pintype "input"))
      (node (ref "D10") (pin "D2") (pinfunction "IN5_D2") (pintype "input"))
    )
    (net (code "154") (name "MC01") (class "Default")
      (node (ref "A08") (pin "L2") (pinfunction "C_L2") (pintype "input"))
      (node (ref "A26") (pin "T1") (pinfunction "P$2_T1") (pintype "bidirectional"))
      (node (ref "B13") (pin "H2") (pinfunction "1_H2") (pintype "output"))
      (node (ref "B13") (pin "J1") (pinfunction "D_J1") (pintype "input"))
      (node (ref "C11") (pin "E1") (pinfunction "IN2_E1") (pintype "input"))
    )
    (net (code "155") (name "MC02") (class "Default")
      (node (ref "A26") (pin "U1") (pinfunction "P$2_U1") (pintype "bidirectional"))
      (node (ref "B11") (pin "U2") (pinfunction "IN2_U2") (pintype "input"))
      (node (ref "B13") (pin "L1") (pinfunction "1_L1") (pintype "output"))
      (node (ref "D12") (pin "D2") (pinfunction "IN1_D2") (pintype "input"))
      (node (ref "D12") (pin "E2") (pinfunction "IN2_E2") (pintype "input"))
    )
    (net (code "156") (name "MF00") (class "Default")
      (node (ref "A25") (pin "V1") (pinfunction "P$2_V1") (pintype "bidirectional"))
      (node (ref "D11") (pin "E1") (pinfunction "1_E1") (pintype "output"))
    )
    (net (code "157") (name "MF01") (class "Default")
      (node (ref "A26") (pin "A1") (pinfunction "P$2_A1") (pintype "bidirectional"))
      (node (ref "D11") (pin "H2") (pinfunction "1_H2") (pintype "output"))
    )
    (net (code "158") (name "MF02") (class "Default")
      (node (ref "A26") (pin "B1") (pinfunction "P$2_B1") (pintype "bidirectional"))
      (node (ref "D11") (pin "L1") (pinfunction "1_L1") (pintype "output"))
    )
    (net (code "159") (name "MKT") (class "Default")
      (node (ref "A26") (pin "H2") (pinfunction "P$2_H2") (pintype "bidirectional"))
      (node (ref "B12") (pin "S2") (pinfunction "IN2_S2") (pintype "input"))
      (node (ref "B13") (pin "V2") (pinfunction "1_V2") (pintype "output"))
      (node (ref "B15") (pin "L1") (pinfunction "IN1_L1") (pintype "input"))
      (node (ref "C15") (pin "L2") (pinfunction "IN1_L2") (pintype "input"))
    )
    (net (code "160") (name "MKTK") (class "Default")
      (node (ref "A08") (pin "R2") (pinfunction "0_R2") (pintype "output"))
      (node (ref "A25") (pin "P1") (pinfunction "P$2_P1") (pintype "bidirectional"))
    )
    (net (code "161") (name "MK_BLK_END") (class "Default")
      (node (ref "A09") (pin "T2") (pinfunction "IN3_T2") (pintype "input"))
      (node (ref "CD18") (pin "BU1") (pinfunction "BU1_BU1") (pintype "output"))
    )
    (net (code "162") (name "MK_BLK_MK") (class "Default")
      (node (ref "CD18") (pin "AE2") (pinfunction "AE2_AE2") (pintype "output"))
      (node (ref "D10") (pin "A1") (pinfunction "IN1_A1") (pintype "input"))
      (node (ref "D10") (pin "B1") (pinfunction "IN2_B1") (pintype "input"))
    )
    (net (code "163") (name "MK_BLK_START") (class "Default")
      (node (ref "CD18") (pin "AJ2") (pinfunction "AJ2_AJ2") (pintype "output"))
    )
    (net (code "164") (name "MK_BLK_SYNC") (class "Default")
      (node (ref "CD18") (pin "BS2") (pinfunction "BS2_BS2") (pintype "output"))
    )
    (net (code "165") (name "MK_DATA") (class "Default")
      (node (ref "CD18") (pin "BP2") (pinfunction "BP2_BP2") (pintype "output"))
    )
    (net (code "166") (name "MK_DATA_SYNC") (class "Default")
      (node (ref "CD18") (pin "AH1") (pinfunction "AH1_AH1") (pintype "output"))
    )
    (net (code "167") (name "MK_END") (class "Default")
      (node (ref "A08") (pin "C1") (pinfunction "D_C1") (pintype "input"))
      (node (ref "CD18") (pin "AF2") (pinfunction "AF2_AF2") (pintype "output"))
    )
    (net (code "168") (name "MOVE") (class "Default")
      (node (ref "D07") (pin "D2") (pinfunction "O0_D2") (pintype "output"))
    )
    (net (code "169") (name "MR00") (class "Default")
      (node (ref "A25") (pin "D1") (pinfunction "P$2_D1") (pintype "bidirectional"))
      (node (ref "B07") (pin "P2") (pinfunction "P2_P2") (pintype "output"))
      (node (ref "B14") (pin "M2") (pinfunction "D_M2") (pintype "input"))
    )
    (net (code "170") (name "MR01") (class "Default")
      (node (ref "A25") (pin "E1") (pinfunction "P$2_E1") (pintype "bidirectional"))
      (node (ref "C07") (pin "P2") (pinfunction "P2_P2") (pintype "output"))
      (node (ref "C12") (pin "B1") (pinfunction "IN2_B1") (pintype "input"))
    )
    (net (code "171") (name "Net-(A08B-D)") (class "Default")
      (node (ref "A08") (pin "E2") (pinfunction "D_E2") (pintype "input"))
      (node (ref "A09") (pin "L1") (pinfunction "OUT_L1") (pintype "output"))
    )
    (net (code "172") (name "Net-(A08C-S)") (class "Default")
      (node (ref "A08") (pin "K1") (pinfunction "S_K1") (pintype "input"))
      (node (ref "A11") (pin "E1") (pinfunction "OUT_E1") (pintype "output"))
    )
    (net (code "173") (name "Net-(A08F-D)") (class "Default")
      (node (ref "A08") (pin "M2") (pinfunction "D_M2") (pintype "input"))
      (node (ref "A09") (pin "J2") (pinfunction "OUT_J2") (pintype "output"))
    )
    (net (code "174") (name "Net-(A08G-C)") (class "Default")
      (node (ref "A08") (pin "N1") (pinfunction "C_N1") (pintype "input"))
      (node (ref "A11") (pin "D2") (pinfunction "OUT_D2") (pintype "output"))
    )
    (net (code "175") (name "Net-(A08G-D)") (class "Default")
      (node (ref "A08") (pin "P1") (pinfunction "D_P1") (pintype "input"))
      (node (ref "A10") (pin "N1") (pinfunction "OUT_N1") (pintype "output"))
    )
    (net (code "176") (name "Net-(A08H-S)") (class "Default")
      (node (ref "A08") (pin "U2") (pinfunction "S_U2") (pintype "input"))
      (node (ref "B10") (pin "S1") (pinfunction "OUT_S1") (pintype "output"))
    )
    (net (code "177") (name "Net-(A09A-OUT)") (class "Default")
      (node (ref "A09") (pin "E1") (pinfunction "OUT_E1") (pintype "output"))
      (node (ref "A11") (pin "A1") (pinfunction "IN_A1") (pintype "input"))
    )
    (net (code "178") (name "Net-(A09C-IN1)") (class "Default")
      (node (ref "A09") (pin "F1") (pinfunction "IN1_F1") (pintype "input"))
      (node (ref "C10") (pin "P2") (pinfunction "OUT_P2") (pintype "output"))
    )
    (net (code "179") (name "Net-(A09C-IN3)") (class "Default")
      (node (ref "A09") (pin "J1") (pinfunction "IN3_J1") (pintype "input"))
      (node (ref "A10") (pin "K1") (pinfunction "OUT_K1") (pintype "output"))
    )
    (net (code "180") (name "Net-(A09C-IN4)") (class "Default")
      (node (ref "A09") (pin "K1") (pinfunction "IN4_K1") (pintype "input"))
      (node (ref "B21") (pin "U2") (pinfunction "OUT_U2") (pintype "output"))
    )
    (net (code "181") (name "Net-(A09D-OUT)") (class "Default")
      (node (ref "A09") (pin "S1") (pinfunction "OUT_S1") (pintype "output"))
      (node (ref "A10") (pin "U2") (pinfunction "IN2_U2") (pintype "input"))
    )
    (net (code "182") (name "Net-(A09E-IN4)") (class "Default")
      (node (ref "A09") (pin "H2") (pinfunction "IN4_H2") (pintype "input"))
      (node (ref "A11") (pin "B1") (pinfunction "OUT_B1") (pintype "output"))
    )
    (net (code "183") (name "Net-(A09F-OUT)") (class "Default")
      (node (ref "A09") (pin "P2") (pinfunction "OUT_P2") (pintype "output"))
      (node (ref "A11") (pin "F1") (pinfunction "IN_F1") (pintype "input"))
    )
    (net (code "184") (name "Net-(A09G-IN4)") (class "Default")
      (node (ref "A09") (pin "U2") (pinfunction "IN4_U2") (pintype "input"))
      (node (ref "C17") (pin "R2") (pinfunction "OUT_R2") (pintype "output"))
    )
    (net (code "185") (name "Net-(A09G-OUT)") (class "Default")
      (node (ref "A09") (pin "V2") (pinfunction "OUT_V2") (pintype "output"))
      (node (ref "A11") (pin "S2") (pinfunction "IN_S2") (pintype "input"))
    )
    (net (code "186") (name "Net-(A10A-IN2)") (class "Default")
      (node (ref "A10") (pin "B1") (pinfunction "IN2_B1") (pintype "input"))
      (node (ref "A10") (pin "F1") (pinfunction "OUT_F1") (pintype "output"))
      (node (ref "B15") (pin "P2") (pinfunction "IN1_P2") (pintype "input"))
    )
    (net (code "187") (name "Net-(A10A-OUT)") (class "Default")
      (node (ref "A10") (pin "C1") (pinfunction "OUT_C1") (pintype "output"))
      (node (ref "A10") (pin "D1") (pinfunction "IN1_D1") (pintype "input"))
    )
    (net (code "188") (name "Net-(A10B-IN1)") (class "Default")
      (node (ref "A10") (pin "S2") (pinfunction "OUT_S2") (pintype "output"))
      (node (ref "A10") (pin "T2") (pinfunction "IN1_T2") (pintype "input"))
    )
    (net (code "189") (name "Net-(A10B-OUT)") (class "Default")
      (node (ref "A10") (pin "V2") (pinfunction "OUT_V2") (pintype "output"))
      (node (ref "A11") (pin "D1") (pinfunction "IN_D1") (pintype "input"))
    )
    (net (code "190") (name "Net-(A10H-OUT)") (class "Default")
      (node (ref "A10") (pin "F2") (pinfunction "OUT_F2") (pintype "output"))
      (node (ref "A10") (pin "J2") (pinfunction "IN2_J2") (pintype "input"))
    )
    (net (code "191") (name "Net-(A10M-OUT)") (class "Default")
      (node (ref "A10") (pin "S1") (pinfunction "OUT_S1") (pintype "output"))
      (node (ref "A11") (pin "C1") (pinfunction "IN_C1") (pintype "input"))
    )
    (net (code "192") (name "Net-(A11D-IN)") (class "Default")
      (node (ref "A11") (pin "R1") (pinfunction "IN_R1") (pintype "input"))
      (node (ref "B11") (pin "S2") (pinfunction "OUT_S2") (pintype "output"))
    )
    (net (code "193") (name "Net-(A11E-IN)") (class "Default")
      (node (ref "A11") (pin "P2") (pinfunction "IN_P2") (pintype "input"))
      (node (ref "A14") (pin "F2") (pinfunction "F2_F2") (pintype "output"))
    )
    (net (code "194") (name "Net-(A11F-IN)") (class "Default")
      (node (ref "A11") (pin "V1") (pinfunction "IN_V1") (pintype "input"))
      (node (ref "B08") (pin "V2") (pinfunction "OUT_V2") (pintype "output"))
    )
    (net (code "195") (name "Net-(A11H-IN)") (class "Default")
      (node (ref "A11") (pin "U2") (pinfunction "IN_U2") (pintype "input"))
      (node (ref "A14") (pin "T2") (pinfunction "F2_T2") (pintype "output"))
    )
    (net (code "196") (name "Net-(A11K-OUT)") (class "Default")
      (node (ref "A11") (pin "H1") (pinfunction "OUT_H1") (pintype "output"))
      (node (ref "A12") (pin "B1") (pinfunction "IN2_B1") (pintype "input"))
      (node (ref "A12") (pin "D1") (pinfunction "IN1_D1") (pintype "input"))
    )
    (net (code "197") (name "Net-(A12B-IN1)") (class "Default")
      (node (ref "A12") (pin "N2") (pinfunction "OUT_N2") (pintype "output"))
      (node (ref "A12") (pin "T2") (pinfunction "IN1_T2") (pintype "input"))
    )
    (net (code "198") (name "Net-(A12B-IN2)") (class "Default")
      (node (ref "A12") (pin "S2") (pinfunction "OUT_S2") (pintype "output"))
      (node (ref "A12") (pin "U2") (pinfunction "IN2_U2") (pintype "input"))
    )
    (net (code "199") (name "Net-(A12H-OUT)") (class "Default")
      (node (ref "A12") (pin "F2") (pinfunction "OUT_F2") (pintype "output"))
      (node (ref "B10") (pin "A1") (pinfunction "IN1_A1") (pintype "input"))
      (node (ref "B10") (pin "B1") (pinfunction "IN2_B1") (pintype "input"))
    )
    (net (code "200") (name "Net-(A12I-IN2)") (class "Default")
      (node (ref "A12") (pin "J1") (pinfunction "IN2_J1") (pintype "input"))
      (node (ref "A12") (pin "N1") (pinfunction "OUT_N1") (pintype "output"))
      (node (ref "A12") (pin "P1") (pinfunction "IN1_P1") (pintype "input"))
    )
    (net (code "201") (name "Net-(A12J-OUT)") (class "Default")
      (node (ref "A12") (pin "K2") (pinfunction "OUT_K2") (pintype "output"))
      (node (ref "B10") (pin "C1") (pinfunction "IN3_C1") (pintype "input"))
      (node (ref "B10") (pin "D1") (pinfunction "IN4_D1") (pintype "input"))
    )
    (net (code "202") (name "Net-(A14-PadD2)") (class "Default")
      (node (ref "A14") (pin "D2") (pinfunction "D2_D2") (pintype "passive"))
      (node (ref "A14") (pin "E2") (pinfunction "E2_E2") (pintype "passive"))
    )
    (net (code "203") (name "Net-(A14-PadH1)") (class "Default")
      (node (ref "A14") (pin "H1") (pinfunction "H1_H1") (pintype "passive"))
      (node (ref "A14") (pin "L2") (pinfunction "L2_L2") (pintype "passive"))
    )
    (net (code "204") (name "Net-(A14B-D2)") (class "Default")
      (node (ref "A14") (pin "R2") (pinfunction "E2_R2") (pintype "passive"))
      (node (ref "A14") (pin "V2") (pinfunction "D2_V2") (pintype "passive"))
    )
    (net (code "205") (name "Net-(A14B-H1)") (class "Default")
      (node (ref "A14") (pin "S1") (pinfunction "H1_S1") (pintype "passive"))
      (node (ref "A14") (pin "S2") (pinfunction "L2_S2") (pintype "passive"))
    )
    (net (code "206") (name "Net-(A14B-H2)") (class "Default")
      (node (ref "A14") (pin "M2") (pinfunction "H2_M2") (pintype "input"))
      (node (ref "A14") (pin "N2") (pinfunction "J2_N2") (pintype "input"))
      (node (ref "A14") (pin "P2") (pinfunction "K2_P2") (pintype "input"))
      (node (ref "B15") (pin "F2") (pinfunction "OUT_F2") (pintype "output"))
    )
    (net (code "207") (name "Net-(A15A-IN3)") (class "Default")
      (node (ref "A15") (pin "C1") (pinfunction "IN3_C1") (pintype "input"))
      (node (ref "A15") (pin "D1") (pinfunction "IN4_D1") (pintype "input"))
      (node (ref "C17") (pin "D2") (pinfunction "OUT_D2") (pintype "output"))
    )
    (net (code "208") (name "Net-(A15D-IN1)") (class "Default")
      (node (ref "A15") (pin "D2") (pinfunction "IN1_D2") (pintype "input"))
      (node (ref "A15") (pin "E2") (pinfunction "IN2_E2") (pintype "input"))
      (node (ref "C17") (pin "F2") (pinfunction "OUT_F2") (pintype "output"))
    )
    (net (code "209") (name "Net-(A16-PadD2)") (class "Default")
      (node (ref "A16") (pin "D2") (pinfunction "D2_D2") (pintype "passive"))
      (node (ref "A16") (pin "E2") (pinfunction "E2_E2") (pintype "passive"))
    )
    (net (code "210") (name "Net-(A16B-D2)") (class "Default")
      (node (ref "A16") (pin "R2") (pinfunction "E2_R2") (pintype "passive"))
      (node (ref "A16") (pin "S2") (pinfunction "D2_S2") (pintype "passive"))
    )
    (net (code "211") (name "Net-(AB19A-P$2)") (class "Default")
      (node (ref "A18") (pin "D2") (pinfunction "D2_D2") (pintype "input"))
      (node (ref "A18") (pin "J2") (pinfunction "J2_J2") (pintype "output"))
      (node (ref "AB19") (pin "AF2") (pinfunction "P$2_AF2") (pintype "bidirectional"))
    )
    (net (code "212") (name "Net-(AB19C-P$2)") (class "Default")
      (node (ref "AB19") (pin "BH2") (pinfunction "P$2_BH2") (pintype "bidirectional"))
      (node (ref "B20") (pin "D2") (pinfunction "D2_D2") (pintype "input"))
      (node (ref "B20") (pin "J2") (pinfunction "J2_J2") (pintype "output"))
    )
    (net (code "213") (name "Net-(AB19D-P$2)") (class "Default")
      (node (ref "AB19") (pin "BJ2") (pinfunction "P$2_BJ2") (pintype "bidirectional"))
      (node (ref "B20") (pin "E2") (pinfunction "E2_E2") (pintype "input"))
      (node (ref "B20") (pin "K2") (pinfunction "K2_K2") (pintype "output"))
    )
    (net (code "214") (name "Net-(AB19F-P$2)") (class "Default")
      (node (ref "A21") (pin "D2") (pinfunction "D2_D2") (pintype "input"))
      (node (ref "A21") (pin "J2") (pinfunction "J2_J2") (pintype "output"))
      (node (ref "AB19") (pin "BN2") (pinfunction "P$2_BN2") (pintype "bidirectional"))
    )
    (net (code "215") (name "Net-(AB19G-P$2)") (class "Default")
      (node (ref "A21") (pin "E2") (pinfunction "E2_E2") (pintype "input"))
      (node (ref "A21") (pin "K2") (pinfunction "K2_K2") (pintype "output"))
      (node (ref "AB19") (pin "BP2") (pinfunction "P$2_BP2") (pintype "bidirectional"))
    )
    (net (code "216") (name "Net-(AB19L-P$2)") (class "Default")
      (node (ref "A18") (pin "E2") (pinfunction "E2_E2") (pintype "input"))
      (node (ref "A18") (pin "K2") (pinfunction "K2_K2") (pintype "output"))
      (node (ref "AB19") (pin "AH2") (pinfunction "P$2_AH2") (pintype "bidirectional"))
    )
    (net (code "217") (name "Net-(AB19P-P$2)") (class "Default")
      (node (ref "AB19") (pin "AN2") (pinfunction "P$2_AN2") (pintype "bidirectional"))
      (node (ref "B18") (pin "D2") (pinfunction "D2_D2") (pintype "input"))
      (node (ref "B18") (pin "J2") (pinfunction "J2_J2") (pintype "output"))
    )
    (net (code "218") (name "Net-(AB19Q-P$2)") (class "Default")
      (node (ref "AB19") (pin "AP2") (pinfunction "P$2_AP2") (pintype "bidirectional"))
      (node (ref "B18") (pin "E2") (pinfunction "E2_E2") (pintype "input"))
      (node (ref "B18") (pin "K2") (pinfunction "K2_K2") (pintype "output"))
    )
    (net (code "219") (name "Net-(AB19T-P$2)") (class "Default")
      (node (ref "A20") (pin "D2") (pinfunction "D2_D2") (pintype "input"))
      (node (ref "A20") (pin "J2") (pinfunction "J2_J2") (pintype "output"))
      (node (ref "AB19") (pin "AV2") (pinfunction "P$2_AV2") (pintype "bidirectional"))
    )
    (net (code "220") (name "Net-(AB19U-P$2)") (class "Default")
      (node (ref "A20") (pin "E2") (pinfunction "E2_E2") (pintype "input"))
      (node (ref "A20") (pin "K2") (pinfunction "K2_K2") (pintype "output"))
      (node (ref "AB19") (pin "BD2") (pinfunction "P$2_BD2") (pintype "bidirectional"))
    )
    (net (code "221") (name "Net-(B06G-IN)") (class "Default")
      (node (ref "B06") (pin "S2") (pinfunction "IN_S2") (pintype "input"))
      (node (ref "B08") (pin "S2") (pinfunction "OUT_S2") (pintype "output"))
    )
    (net (code "222") (name "Net-(B08A-OUT)") (class "Default")
      (node (ref "B08") (pin "C1") (pinfunction "OUT_C1") (pintype "output"))
      (node (ref "B09") (pin "D1") (pinfunction "S_D1") (pintype "input"))
    )
    (net (code "223") (name "Net-(B08G-OUT)") (class "Default")
      (node (ref "B08") (pin "F1") (pinfunction "OUT_F1") (pintype "output"))
      (node (ref "B09") (pin "U2") (pinfunction "S_U2") (pintype "input"))
    )
    (net (code "224") (name "Net-(B08H-OUT)") (class "Default")
      (node (ref "B08") (pin "F2") (pinfunction "OUT_F2") (pintype "output"))
      (node (ref "B09") (pin "K1") (pinfunction "S_K1") (pintype "input"))
    )
    (net (code "225") (name "Net-(B08I-OUT)") (class "Default")
      (node (ref "B08") (pin "K1") (pinfunction "OUT_K1") (pintype "output"))
      (node (ref "B09") (pin "F2") (pinfunction "S_F2") (pintype "input"))
    )
    (net (code "226") (name "Net-(B08K-OUT)") (class "Default")
      (node (ref "B08") (pin "N1") (pinfunction "OUT_N1") (pintype "output"))
      (node (ref "B09") (pin "N2") (pinfunction "S_N2") (pintype "input"))
    )
    (net (code "227") (name "Net-(B08M-OUT)") (class "Default")
      (node (ref "B08") (pin "S1") (pinfunction "OUT_S1") (pintype "output"))
      (node (ref "B09") (pin "R1") (pinfunction "S_R1") (pintype "input"))
    )
    (net (code "228") (name "Net-(B10B-IN1)") (class "Default")
      (node (ref "B10") (pin "F1") (pinfunction "IN1_F1") (pintype "input"))
      (node (ref "B11") (pin "J1") (pinfunction "OUT_J1") (pintype "output"))
    )
    (net (code "229") (name "Net-(B10B-IN4)") (class "Default")
      (node (ref "B10") (pin "K1") (pinfunction "IN4_K1") (pintype "input"))
      (node (ref "C17") (pin "H1") (pinfunction "OUT_H1") (pintype "output"))
    )
    (net (code "230") (name "Net-(B11A-OUT)") (class "Default")
      (node (ref "B11") (pin "D1") (pinfunction "OUT_D1") (pintype "output"))
      (node (ref "B11") (pin "F2") (pinfunction "IN3_F2") (pintype "input"))
    )
    (net (code "231") (name "Net-(B11C-IN1)") (class "Default")
      (node (ref "B11") (pin "E1") (pinfunction "IN1_E1") (pintype "input"))
      (node (ref "B11") (pin "U1") (pinfunction "OUT_U1") (pintype "output"))
    )
    (net (code "232") (name "Net-(B11C-IN3)") (class "Default")
      (node (ref "B11") (pin "H1") (pinfunction "IN3_H1") (pintype "input"))
      (node (ref "B11") (pin "N1") (pinfunction "OUT_N1") (pintype "output"))
    )
    (net (code "233") (name "Net-(B11F-IN1)") (class "Default")
      (node (ref "B11") (pin "D2") (pinfunction "IN1_D2") (pintype "input"))
      (node (ref "B12") (pin "E1") (pinfunction "OUT_E1") (pintype "output"))
    )
    (net (code "234") (name "Net-(B11F-IN2)") (class "Default")
      (node (ref "B11") (pin "E2") (pinfunction "IN2_E2") (pintype "input"))
      (node (ref "B12") (pin "L1") (pinfunction "OUT_L1") (pintype "output"))
    )
    (net (code "235") (name "Net-(B11F-OUT)") (class "Default")
      (node (ref "B11") (pin "H2") (pinfunction "OUT_H2") (pintype "output"))
      (node (ref "C13") (pin "C1") (pinfunction "IN_C1") (pintype "input"))
    )
    (net (code "236") (name "Net-(B11G-IN3)") (class "Default")
      (node (ref "B11") (pin "L2") (pinfunction "IN3_L2") (pintype "input"))
      (node (ref "B15") (pin "S2") (pinfunction "OUT_S2") (pintype "output"))
    )
    (net (code "237") (name "Net-(B11I-OUT)") (class "Default")
      (node (ref "B11") (pin "V1") (pinfunction "OUT_V1") (pintype "output"))
      (node (ref "C17") (pin "J1") (pinfunction "IN_J1") (pintype "input"))
    )
    (net (code "238") (name "Net-(B12D-IN1)") (class "Default")
      (node (ref "B12") (pin "M1") (pinfunction "IN1_M1") (pintype "input"))
      (node (ref "C11") (pin "C1") (pinfunction "OUT_C1") (pintype "output"))
    )
    (net (code "239") (name "Net-(B12D-IN4)") (class "Default")
      (node (ref "B12") (pin "R1") (pinfunction "IN4_R1") (pintype "input"))
      (node (ref "C11") (pin "F1") (pinfunction "OUT_F1") (pintype "output"))
    )
    (net (code "240") (name "Net-(B12D-OUT)") (class "Default")
      (node (ref "B12") (pin "S1") (pinfunction "OUT_S1") (pintype "output"))
      (node (ref "C11") (pin "P1") (pinfunction "IN1_P1") (pintype "input"))
    )
    (net (code "241") (name "Net-(B12E-OUT)") (class "Default")
      (node (ref "B12") (pin "J2") (pinfunction "OUT_J2") (pintype "output"))
      (node (ref "B12") (pin "N2") (pinfunction "IN4_N2") (pintype "input"))
    )
    (net (code "242") (name "Net-(B12F-IN1)") (class "Default")
      (node (ref "B12") (pin "K2") (pinfunction "IN1_K2") (pintype "input"))
      (node (ref "C12") (pin "N1") (pinfunction "OUT_N1") (pintype "output"))
    )
    (net (code "243") (name "Net-(B12F-IN2)") (class "Default")
      (node (ref "B12") (pin "L2") (pinfunction "IN2_L2") (pintype "input"))
      (node (ref "C12") (pin "U1") (pinfunction "OUT_U1") (pintype "output"))
    )
    (net (code "244") (name "Net-(B12F-IN3)") (class "Default")
      (node (ref "B12") (pin "M2") (pinfunction "IN3_M2") (pintype "input"))
      (node (ref "C12") (pin "V1") (pinfunction "OUT_V1") (pintype "output"))
    )
    (net (code "245") (name "Net-(B12G-IN4)") (class "Default")
      (node (ref "B12") (pin "U2") (pinfunction "IN4_U2") (pintype "input"))
      (node (ref "C11") (pin "N1") (pinfunction "OUT_N1") (pintype "output"))
    )
    (net (code "246") (name "Net-(B12G-OUT)") (class "Default")
      (node (ref "B12") (pin "V2") (pinfunction "OUT_V2") (pintype "output"))
      (node (ref "C12") (pin "F1") (pinfunction "IN2_F1") (pintype "input"))
    )
    (net (code "247") (name "Net-(B13F-S)") (class "Default")
      (node (ref "B13") (pin "N2") (pinfunction "S_N2") (pintype "input"))
      (node (ref "B15") (pin "K1") (pinfunction "OUT_K1") (pintype "output"))
    )
    (net (code "248") (name "Net-(B14G-C)") (class "Default")
      (node (ref "B14") (pin "N1") (pinfunction "C_N1") (pintype "input"))
      (node (ref "B14") (pin "S2") (pinfunction "C_S2") (pintype "input"))
      (node (ref "D15") (pin "D2") (pinfunction "D2_D2") (pintype "output"))
    )
    (net (code "249") (name "Net-(B15G-OUT)") (class "Default")
      (node (ref "A14") (pin "H2") (pinfunction "H2_H2") (pintype "input"))
      (node (ref "A14") (pin "J2") (pinfunction "J2_J2") (pintype "input"))
      (node (ref "A14") (pin "K2") (pinfunction "K2_K2") (pintype "input"))
      (node (ref "B15") (pin "F1") (pinfunction "OUT_F1") (pintype "output"))
    )
    (net (code "250") (name "Net-(B15K-OUT)") (class "Default")
      (node (ref "B15") (pin "N1") (pinfunction "OUT_N1") (pintype "output"))
      (node (ref "C17") (pin "F1") (pinfunction "IN_F1") (pintype "input"))
    )
    (net (code "251") (name "Net-(B15M-OUT)") (class "Default")
      (node (ref "B15") (pin "S1") (pinfunction "OUT_S1") (pintype "output"))
      (node (ref "C17") (pin "L1") (pinfunction "IN_L1") (pintype "input"))
    )
    (net (code "252") (name "Net-(B16-PadD2)") (class "Default")
      (node (ref "B16") (pin "D2") (pinfunction "D2_D2") (pintype "passive"))
      (node (ref "B16") (pin "E2") (pinfunction "E2_E2") (pintype "passive"))
    )
    (net (code "253") (name "Net-(B16B-D2)") (class "Default")
      (node (ref "B16") (pin "R2") (pinfunction "E2_R2") (pintype "passive"))
      (node (ref "B16") (pin "S2") (pinfunction "D2_S2") (pintype "passive"))
    )
    (net (code "254") (name "Net-(C08A-OUT)") (class "Default")
      (node (ref "C08") (pin "E1") (pinfunction "OUT_E1") (pintype "output"))
      (node (ref "C09") (pin "D1") (pinfunction "S_D1") (pintype "input"))
    )
    (net (code "255") (name "Net-(C08C-OUT)") (class "Default")
      (node (ref "C08") (pin "L1") (pinfunction "OUT_L1") (pintype "output"))
      (node (ref "C09") (pin "F2") (pinfunction "S_F2") (pintype "input"))
    )
    (net (code "256") (name "Net-(C08D-OUT)") (class "Default")
      (node (ref "C08") (pin "S1") (pinfunction "OUT_S1") (pintype "output"))
      (node (ref "C09") (pin "K1") (pinfunction "S_K1") (pintype "input"))
    )
    (net (code "257") (name "Net-(C08E-OUT)") (class "Default")
      (node (ref "C08") (pin "J2") (pinfunction "OUT_J2") (pintype "output"))
      (node (ref "C09") (pin "N2") (pinfunction "S_N2") (pintype "input"))
    )
    (net (code "258") (name "Net-(C08F-OUT)") (class "Default")
      (node (ref "C08") (pin "P2") (pinfunction "OUT_P2") (pintype "output"))
      (node (ref "C09") (pin "R1") (pinfunction "S_R1") (pintype "input"))
    )
    (net (code "259") (name "Net-(C08G-OUT)") (class "Default")
      (node (ref "C08") (pin "V2") (pinfunction "OUT_V2") (pintype "output"))
      (node (ref "C09") (pin "U2") (pinfunction "S_U2") (pintype "input"))
    )
    (net (code "260") (name "Net-(C10A-OUT)") (class "Default")
      (node (ref "C10") (pin "E1") (pinfunction "OUT_E1") (pintype "output"))
      (node (ref "C14") (pin "C1") (pinfunction "D_C1") (pintype "input"))
    )
    (net (code "261") (name "Net-(C10C-OUT)") (class "Default")
      (node (ref "C10") (pin "L1") (pinfunction "OUT_L1") (pintype "output"))
      (node (ref "C14") (pin "E2") (pinfunction "D_E2") (pintype "input"))
    )
    (net (code "262") (name "Net-(C10D-OUT)") (class "Default")
      (node (ref "C10") (pin "S1") (pinfunction "OUT_S1") (pintype "output"))
      (node (ref "C14") (pin "J1") (pinfunction "D_J1") (pintype "input"))
    )
    (net (code "263") (name "Net-(C10E-OUT)") (class "Default")
      (node (ref "C10") (pin "J2") (pinfunction "OUT_J2") (pintype "output"))
      (node (ref "C17") (pin "M2") (pinfunction "IN_M2") (pintype "input"))
    )
    (net (code "264") (name "Net-(C10G-OUT)") (class "Default")
      (node (ref "C10") (pin "V2") (pinfunction "OUT_V2") (pintype "output"))
      (node (ref "C17") (pin "V1") (pinfunction "IN_V1") (pintype "input"))
    )
    (net (code "265") (name "Net-(C11B-IN1)") (class "Default")
      (node (ref "C11") (pin "S2") (pinfunction "OUT_S2") (pintype "output"))
      (node (ref "C11") (pin "T2") (pinfunction "IN1_T2") (pintype "input"))
    )
    (net (code "266") (name "Net-(C11B-OUT)") (class "Default")
      (node (ref "C11") (pin "V2") (pinfunction "OUT_V2") (pintype "output"))
      (node (ref "C13") (pin "V1") (pinfunction "IN_V1") (pintype "input"))
    )
    (net (code "267") (name "Net-(C11H-OUT)") (class "Default")
      (node (ref "C11") (pin "F2") (pinfunction "OUT_F2") (pintype "output"))
      (node (ref "C12") (pin "H1") (pinfunction "IN3_H1") (pintype "input"))
    )
    (net (code "268") (name "Net-(C11I-OUT)") (class "Default")
      (node (ref "C11") (pin "K1") (pinfunction "OUT_K1") (pintype "output"))
      (node (ref "C11") (pin "L1") (pinfunction "IN1_L1") (pintype "input"))
    )
    (net (code "269") (name "Net-(C11J-OUT)") (class "Default")
      (node (ref "C11") (pin "K2") (pinfunction "OUT_K2") (pintype "output"))
      (node (ref "D12") (pin "K2") (pinfunction "IN1_K2") (pintype "input"))
      (node (ref "D12") (pin "L2") (pinfunction "IN2_L2") (pintype "input"))
    )
    (net (code "270") (name "Net-(C11M-OUT)") (class "Default")
      (node (ref "C11") (pin "S1") (pinfunction "OUT_S1") (pintype "output"))
      (node (ref "C12") (pin "E1") (pinfunction "IN1_E1") (pintype "input"))
    )
    (net (code "271") (name "Net-(C12A-OUT)") (class "Default")
      (node (ref "C12") (pin "D1") (pinfunction "OUT_D1") (pintype "output"))
      (node (ref "C13") (pin "M2") (pinfunction "IN_M2") (pintype "input"))
    )
    (net (code "272") (name "Net-(C12F-OUT)") (class "Default")
      (node (ref "C12") (pin "H2") (pinfunction "OUT_H2") (pintype "output"))
      (node (ref "D12") (pin "M2") (pinfunction "IN3_M2") (pintype "input"))
      (node (ref "D12") (pin "N2") (pinfunction "IN4_N2") (pintype "input"))
    )
    (net (code "273") (name "Net-(C12H-OUT)") (class "Default")
      (node (ref "C12") (pin "S2") (pinfunction "OUT_S2") (pintype "output"))
      (node (ref "C15") (pin "P1") (pinfunction "IN1_P1") (pintype "input"))
    )
    (net (code "274") (name "Net-(C13C-OUT)") (class "Default")
      (node (ref "C13") (pin "N2") (pinfunction "OUT_N2") (pintype "output"))
      (node (ref "C14") (pin "N2") (pinfunction "S_N2") (pintype "input"))
    )
    (net (code "275") (name "Net-(C13E-IN)") (class "Default")
      (node (ref "C13") (pin "P2") (pinfunction "IN_P2") (pintype "input"))
      (node (ref "C15") (pin "F2") (pinfunction "OUT_F2") (pintype "output"))
    )
    (net (code "276") (name "Net-(C13G-IN)") (class "Default")
      (node (ref "C13") (pin "S2") (pinfunction "IN_S2") (pintype "input"))
      (node (ref "C15") (pin "K2") (pinfunction "OUT_K2") (pintype "output"))
    )
    (net (code "277") (name "Net-(C13I-OUT)") (class "Default")
      (node (ref "C13") (pin "D2") (pinfunction "OUT_D2") (pintype "output"))
      (node (ref "C14") (pin "P1") (pinfunction "D_P1") (pintype "input"))
    )
    (net (code "278") (name "Net-(C14F-C)") (class "Default")
      (node (ref "C14") (pin "L2") (pinfunction "C_L2") (pintype "input"))
      (node (ref "C15") (pin "S2") (pinfunction "OUT_S2") (pintype "output"))
    )
    (net (code "279") (name "Net-(C15A-OUT)") (class "Default")
      (node (ref "C15") (pin "C1") (pinfunction "OUT_C1") (pintype "output"))
      (node (ref "C15") (pin "H1") (pinfunction "IN1_H1") (pintype "input"))
    )
    (net (code "280") (name "Net-(C15G-OUT)") (class "Default")
      (node (ref "C15") (pin "F1") (pinfunction "OUT_F1") (pintype "output"))
      (node (ref "C15") (pin "J1") (pinfunction "IN2_J1") (pintype "input"))
    )
    (net (code "281") (name "Net-(C15K-OUT)") (class "Default")
      (node (ref "C15") (pin "N1") (pinfunction "OUT_N1") (pintype "output"))
      (node (ref "C15") (pin "R1") (pinfunction "IN2_R1") (pintype "input"))
    )
    (net (code "282") (name "Net-(C15L-OUT)") (class "Default")
      (node (ref "C15") (pin "N2") (pinfunction "OUT_N2") (pintype "output"))
      (node (ref "C17") (pin "P2") (pinfunction "IN_P2") (pintype "input"))
    )
    (net (code "283") (name "Net-(C16C-OUT)") (class "Default")
      (node (ref "B16") (pin "K2") (pinfunction "K2_K2") (pintype "input"))
      (node (ref "C16") (pin "S1") (pinfunction "OUT_S1") (pintype "output"))
    )
    (net (code "284") (name "Net-(C16E-IN1)") (class "Default")
      (node (ref "C16") (pin "K2") (pinfunction "IN1_K2") (pintype "input"))
      (node (ref "C16") (pin "L2") (pinfunction "IN2_L2") (pintype "input"))
      (node (ref "C16") (pin "M2") (pinfunction "IN3_M2") (pintype "input"))
      (node (ref "C16") (pin "N2") (pinfunction "IN4_N2") (pintype "input"))
      (node (ref "C17") (pin "B1") (pinfunction "OUT_B1") (pintype "output"))
    )
    (net (code "285") (name "Net-(C16F-OUT)") (class "Default")
      (node (ref "A16") (pin "H2") (pinfunction "H2_H2") (pintype "input"))
      (node (ref "C16") (pin "V2") (pinfunction "OUT_V2") (pintype "output"))
    )
    (net (code "286") (name "Net-(C17C-OUT)") (class "Default")
      (node (ref "C17") (pin "N2") (pinfunction "OUT_N2") (pintype "output"))
      (node (ref "D08") (pin "B1") (pinfunction "B1_B1") (pintype "input"))
      (node (ref "D08") (pin "H1") (pinfunction "H1_H1") (pintype "input"))
      (node (ref "D08") (pin "N1") (pinfunction "N1_N1") (pintype "input"))
    )
    (net (code "287") (name "Net-(C17D-IN)") (class "Default")
      (node (ref "C17") (pin "R1") (pinfunction "IN_R1") (pintype "input"))
      (node (ref "D17") (pin "F2") (pinfunction "F2_F2") (pintype "output"))
    )
    (net (code "288") (name "Net-(C17F-OUT)") (class "Default")
      (node (ref "C17") (pin "U1") (pinfunction "OUT_U1") (pintype "output"))
      (node (ref "D08") (pin "D2") (pinfunction "D2_D2") (pintype "input"))
      (node (ref "D08") (pin "L2") (pinfunction "L2_L2") (pintype "input"))
      (node (ref "D08") (pin "S2") (pinfunction "S2_S2") (pintype "input"))
    )
    (net (code "289") (name "Net-(C17G-IN)") (class "Default")
      (node (ref "C17") (pin "S2") (pinfunction "IN_S2") (pintype "input"))
      (node (ref "D16") (pin "T2") (pinfunction "F2_T2") (pintype "output"))
    )
    (net (code "290") (name "Net-(C17I-IN)") (class "Default")
      (node (ref "A16") (pin "F2") (pinfunction "F2_F2") (pintype "output"))
      (node (ref "C17") (pin "C1") (pinfunction "IN_C1") (pintype "input"))
    )
    (net (code "291") (name "Net-(C17L-IN)") (class "Default")
      (node (ref "B16") (pin "F2") (pinfunction "F2_F2") (pintype "output"))
      (node (ref "C17") (pin "E2") (pinfunction "IN_E2") (pintype "input"))
    )
    (net (code "292") (name "Net-(D09A-OUT)") (class "Default")
      (node (ref "D08") (pin "C1") (pinfunction "C1_C1") (pintype "input"))
      (node (ref "D08") (pin "D1") (pinfunction "D1_D1") (pintype "input"))
      (node (ref "D09") (pin "E1") (pinfunction "OUT_E1") (pintype "output"))
    )
    (net (code "293") (name "Net-(D09C-OUT)") (class "Default")
      (node (ref "D08") (pin "J1") (pinfunction "J1_J1") (pintype "input"))
      (node (ref "D08") (pin "K1") (pinfunction "K1_K1") (pintype "input"))
      (node (ref "D09") (pin "L1") (pinfunction "OUT_L1") (pintype "output"))
    )
    (net (code "294") (name "Net-(D09D-OUT)") (class "Default")
      (node (ref "D08") (pin "P1") (pinfunction "P1_P1") (pintype "input"))
      (node (ref "D08") (pin "R1") (pinfunction "R1_R1") (pintype "input"))
      (node (ref "D09") (pin "S1") (pinfunction "OUT_S1") (pintype "output"))
    )
    (net (code "295") (name "Net-(D09E-OUT)") (class "Default")
      (node (ref "D08") (pin "E2") (pinfunction "E2_E2") (pintype "input"))
      (node (ref "D08") (pin "F2") (pinfunction "F2_F2") (pintype "input"))
      (node (ref "D09") (pin "J2") (pinfunction "OUT_J2") (pintype "output"))
    )
    (net (code "296") (name "Net-(D09F-OUT)") (class "Default")
      (node (ref "D08") (pin "M2") (pinfunction "M2_M2") (pintype "input"))
      (node (ref "D08") (pin "N2") (pinfunction "N2_N2") (pintype "input"))
      (node (ref "D09") (pin "P2") (pinfunction "OUT_P2") (pintype "output"))
    )
    (net (code "297") (name "Net-(D09G-OUT)") (class "Default")
      (node (ref "D08") (pin "T2") (pinfunction "T2_T2") (pintype "input"))
      (node (ref "D08") (pin "U2") (pinfunction "U2_U2") (pintype "input"))
      (node (ref "D09") (pin "V2") (pinfunction "OUT_V2") (pintype "output"))
    )
    (net (code "298") (name "Net-(D10B-OUT)") (class "Default")
      (node (ref "D10") (pin "P2") (pinfunction "OUT_P2") (pintype "output"))
      (node (ref "D14") (pin "J2") (pinfunction "N1_J2") (pintype "input"))
    )
    (net (code "299") (name "Net-(D12A-IN1)") (class "Default")
      (node (ref "D12") (pin "A1") (pinfunction "IN1_A1") (pintype "input"))
      (node (ref "D12") (pin "B1") (pinfunction "IN2_B1") (pintype "input"))
      (node (ref "D12") (pin "C1") (pinfunction "IN3_C1") (pintype "input"))
      (node (ref "D12") (pin "D1") (pinfunction "IN4_D1") (pintype "input"))
      (node (ref "D13") (pin "F2") (pinfunction "F2_F2") (pintype "output"))
    )
    (net (code "300") (name "Net-(D13B-D2)") (class "Default")
      (node (ref "D13") (pin "R2") (pinfunction "E2_R2") (pintype "passive"))
      (node (ref "D13") (pin "S2") (pinfunction "D2_S2") (pintype "passive"))
    )
    (net (code "301") (name "Net-(D14-PadM2)") (class "Default")
      (node (ref "D14") (pin "M2") (pinfunction "M2_M2") (pintype "passive"))
      (node (ref "D14") (pin "V2") (pinfunction "V2_V2") (pintype "passive"))
    )
    (net (code "302") (name "Net-(D14-PadP1)") (class "Default")
      (node (ref "D14") (pin "P1") (pinfunction "P1_P1") (pintype "passive"))
      (node (ref "D14") (pin "V1") (pinfunction "V1_V1") (pintype "passive"))
    )
    (net (code "303") (name "Net-(D14B-M2)") (class "Default")
      (node (ref "D14") (pin "D2") (pinfunction "M2_D2") (pintype "passive"))
      (node (ref "D14") (pin "H1") (pinfunction "P2_H1") (pintype "passive"))
    )
    (net (code "304") (name "Net-(D14B-P1)") (class "Default")
      (node (ref "D14") (pin "A1") (pinfunction "V1_A1") (pintype "passive"))
      (node (ref "D14") (pin "C1") (pinfunction "P1_C1") (pintype "passive"))
    )
    (net (code "305") (name "Net-(D15-PadN2)") (class "Default")
      (node (ref "D15") (pin "N2") (pinfunction "N2_N2") (pintype "passive"))
      (node (ref "D15") (pin "S2") (pinfunction "S2_S2") (pintype "passive"))
    )
    (net (code "306") (name "Net-(D16B-D2)") (class "Default")
      (node (ref "D16") (pin "R2") (pinfunction "E2_R2") (pintype "passive"))
      (node (ref "D16") (pin "V2") (pinfunction "D2_V2") (pintype "passive"))
    )
    (net (code "307") (name "Net-(D16B-H1)") (class "Default")
      (node (ref "D16") (pin "S1") (pinfunction "H1_S1") (pintype "passive"))
      (node (ref "D16") (pin "S2") (pinfunction "L2_S2") (pintype "passive"))
    )
    (net (code "308") (name "Net-(D17-PadD2)") (class "Default")
      (node (ref "D17") (pin "D2") (pinfunction "D2_D2") (pintype "passive"))
      (node (ref "D17") (pin "E2") (pinfunction "E2_E2") (pintype "passive"))
    )
    (net (code "309") (name "Net-(D17B-D2)") (class "Default")
      (node (ref "D17") (pin "R2") (pinfunction "E2_R2") (pintype "passive"))
      (node (ref "D17") (pin "S2") (pinfunction "D2_S2") (pintype "passive"))
    )
    (net (code "310") (name "PAR") (class "Default")
      (node (ref "A08") (pin "U1") (pinfunction "0_U1") (pintype "output"))
      (node (ref "A25") (pin "T1") (pinfunction "P$2_T1") (pintype "bidirectional"))
    )
    (net (code "311") (name "PC+ES") (class "Default")
      (node (ref "A11") (pin "H2") (pinfunction "IN_H2") (pintype "input"))
      (node (ref "A12") (pin "C1") (pinfunction "OUT_C1") (pintype "output"))
    )
    (net (code "312") (name "PWR_CLR") (class "Default")
      (node (ref "C06") (pin "R2") (pinfunction "OUT_R2") (pintype "output"))
    )
    (net (code "313") (name "RD+WD") (class "Default")
      (node (ref "A09") (pin "P1") (pinfunction "IN3_P1") (pintype "input"))
      (node (ref "B08") (pin "N2") (pinfunction "OUT_N2") (pintype "output"))
      (node (ref "B12") (pin "D2") (pinfunction "IN1_D2") (pintype "input"))
      (node (ref "C12") (pin "R1") (pinfunction "IN2_R1") (pintype "input"))
    )
    (net (code "314") (name "RDD_00") (class "Default")
      (node (ref "A21") (pin "U2") (pinfunction "U2_U2") (pintype "output"))
      (node (ref "B09") (pin "M2") (pinfunction "D_M2") (pintype "input"))
      (node (ref "D09") (pin "C1") (pinfunction "IN2A_C1") (pintype "input"))
      (node (ref "D09") (pin "F2") (pinfunction "IN2A_F2") (pintype "input"))
    )
    (net (code "315") (name "RDD_01") (class "Default")
      (node (ref "B09") (pin "P1") (pinfunction "D_P1") (pintype "input"))
      (node (ref "B20") (pin "U2") (pinfunction "U2_U2") (pintype "output"))
      (node (ref "D09") (pin "J1") (pinfunction "IN2A_J1") (pintype "input"))
      (node (ref "D09") (pin "M2") (pinfunction "IN2A_M2") (pintype "input"))
    )
    (net (code "316") (name "RDD_02") (class "Default")
      (node (ref "A20") (pin "U2") (pinfunction "U2_U2") (pintype "output"))
      (node (ref "B09") (pin "E2") (pinfunction "D_E2") (pintype "input"))
      (node (ref "D09") (pin "P1") (pinfunction "IN2A_P1") (pintype "input"))
      (node (ref "D09") (pin "T2") (pinfunction "IN2A_T2") (pintype "input"))
    )
    (net (code "317") (name "RDMK") (class "Default")
      (node (ref "B18") (pin "U2") (pinfunction "U2_U2") (pintype "output"))
      (node (ref "CD18") (pin "AS2") (pinfunction "AS2_AS2") (pintype "input"))
    )
    (net (code "318") (name "RD_EN") (class "Default")
      (node (ref "C11") (pin "J1") (pinfunction "IN2_J1") (pintype "input"))
      (node (ref "C11") (pin "N2") (pinfunction "OUT_N2") (pintype "output"))
    )
    (net (code "319") (name "RD_EN_LPB_00-02") (class "Default")
      (node (ref "C10") (pin "D2") (pinfunction "IN1A_D2") (pintype "input"))
      (node (ref "C13") (pin "T2") (pinfunction "OUT_T2") (pintype "output"))
      (node (ref "D09") (pin "D1") (pinfunction "IN2B_D1") (pintype "input"))
      (node (ref "D09") (pin "K1") (pinfunction "IN2B_K1") (pintype "input"))
      (node (ref "D09") (pin "R1") (pinfunction "IN2B_R1") (pintype "input"))
    )
    (net (code "320") (name "RD_EN_LPB_03-05") (class "Default")
      (node (ref "C10") (pin "R2") (pinfunction "IN1A_R2") (pintype "input"))
      (node (ref "C13") (pin "R2") (pinfunction "OUT_R2") (pintype "output"))
      (node (ref "D09") (pin "H2") (pinfunction "IN2B_H2") (pintype "input"))
      (node (ref "D09") (pin "N2") (pinfunction "IN2B_N2") (pintype "input"))
      (node (ref "D09") (pin "U2") (pinfunction "IN2B_U2") (pintype "input"))
    )
    (net (code "321") (name "READ_ALL") (class "Default")
      (node (ref "D07") (pin "N2") (pinfunction "O3_N2") (pintype "output"))
    )
    (net (code "322") (name "READ_DATA") (class "Default")
      (node (ref "A10") (pin "L1") (pinfunction "IN1_L1") (pintype "input"))
      (node (ref "C11") (pin "H1") (pinfunction "IN1_H1") (pintype "input"))
      (node (ref "D07") (pin "J2") (pinfunction "O2_J2") (pintype "output"))
    )
    (net (code "323") (name "RSTA") (class "Default")
      (node (ref "C04") (pin "B1") (pinfunction "B1_B1") (pintype "output"))
    )
    (net (code "324") (name "RSTB") (class "Default")
      (node (ref "C05") (pin "D1") (pinfunction "D1_D1") (pintype "output"))
    )
    (net (code "325") (name "SE") (class "Default")
      (node (ref "D07") (pin "L2") (pinfunction "O7_L2") (pintype "output"))
    )
    (net (code "326") (name "SEARCH") (class "Default")
      (node (ref "C11") (pin "D2") (pinfunction "IN1_D2") (pintype "input"))
      (node (ref "D07") (pin "E2") (pinfunction "O1_E2") (pintype "output"))
    )
    (net (code "327") (name "SEL") (class "Default")
      (node (ref "A08") (pin "H2") (pinfunction "1_H2") (pintype "output"))
      (node (ref "A25") (pin "S1") (pinfunction "P$2_S1") (pintype "bidirectional"))
    )
    (net (code "328") (name "SHIFT_CK") (class "Default")
      (node (ref "C17") (pin "K1") (pinfunction "OUT_K1") (pintype "output"))
      (node (ref "CD18") (pin "BR2") (pinfunction "BR2_BR2") (pintype "input"))
    )
    (net (code "329") (name "SH_DTB") (class "Default")
      (node (ref "A10") (pin "R2") (pinfunction "IN2_R2") (pintype "input"))
      (node (ref "B09") (pin "B1") (pinfunction "C_B1") (pintype "input"))
      (node (ref "B09") (pin "D2") (pinfunction "C_D2") (pintype "input"))
      (node (ref "B09") (pin "H1") (pinfunction "C_H1") (pintype "input"))
      (node (ref "B09") (pin "L2") (pinfunction "C_L2") (pintype "input"))
      (node (ref "B09") (pin "N1") (pinfunction "C_N1") (pintype "input"))
      (node (ref "B09") (pin "S2") (pinfunction "C_S2") (pintype "input"))
      (node (ref "B10") (pin "E1") (pinfunction "OUT_E1") (pintype "output"))
      (node (ref "C09") (pin "B1") (pinfunction "C_B1") (pintype "input"))
      (node (ref "C09") (pin "D2") (pinfunction "C_D2") (pintype "input"))
      (node (ref "C09") (pin "H1") (pinfunction "C_H1") (pintype "input"))
      (node (ref "C09") (pin "L2") (pinfunction "C_L2") (pintype "input"))
      (node (ref "C09") (pin "N1") (pinfunction "C_N1") (pintype "input"))
      (node (ref "C09") (pin "S2") (pinfunction "C_S2") (pintype "input"))
    )
    (net (code "330") (name "SH_EN") (class "Default")
      (node (ref "A11") (pin "N2") (pinfunction "OUT_N2") (pintype "output"))
      (node (ref "A12") (pin "E2") (pinfunction "IN2_E2") (pintype "input"))
      (node (ref "C10") (pin "A1") (pinfunction "IN1A_A1") (pintype "input"))
      (node (ref "C10") (pin "F1") (pinfunction "IN1A_F1") (pintype "input"))
      (node (ref "C10") (pin "M1") (pinfunction "IN1A_M1") (pintype "input"))
    )
    (net (code "331") (name "SH_ST") (class "Default")
      (node (ref "C17") (pin "A1") (pinfunction "IN_A1") (pintype "input"))
      (node (ref "CD18") (pin "AM1") (pinfunction "AM1_AM1") (pintype "output"))
    )
    (net (code "332") (name "SH_ST-B") (class "Default")
      (node (ref "C16") (pin "P2") (pinfunction "OUT_P2") (pintype "output"))
      (node (ref "CD18") (pin "BC1") (pinfunction "BC1_BC1") (pintype "input"))
    )
    (net (code "333") (name "SP_DY") (class "Default")
      (node (ref "D14") (pin "H2") (pinfunction "H2_H2") (pintype "output"))
    )
    (net (code "334") (name "ST_BLK_MK") (class "Default")
      (node (ref "A26") (pin "K1") (pinfunction "P$2_K1") (pintype "bidirectional"))
      (node (ref "C13") (pin "E2") (pinfunction "IN_E2") (pintype "input"))
      (node (ref "CD18") (pin "AR2") (pinfunction "AR2_AR2") (pintype "output"))
    )
    (net (code "335") (name "ST_CK") (class "Default")
      (node (ref "A10") (pin "P1") (pinfunction "IN1_P1") (pintype "input"))
      (node (ref "A26") (pin "P1") (pinfunction "P$2_P1") (pintype "bidirectional"))
      (node (ref "C13") (pin "J1") (pinfunction "IN_J1") (pintype "input"))
      (node (ref "CD18") (pin "BR1") (pinfunction "BR1_BR1") (pintype "output"))
      (node (ref "D17") (pin "M2") (pinfunction "K2_M2") (pintype "input"))
      (node (ref "D17") (pin "N2") (pinfunction "J2_N2") (pintype "input"))
      (node (ref "D17") (pin "P2") (pinfunction "H2_P2") (pintype "input"))
    )
    (net (code "336") (name "ST_CK_0P") (class "Default")
      (node (ref "B12") (pin "H2") (pinfunction "IN4_H2") (pintype "input"))
      (node (ref "C12") (pin "S1") (pinfunction "IN3_S1") (pintype "input"))
      (node (ref "C13") (pin "B1") (pinfunction "OUT_B1") (pintype "output"))
    )
    (net (code "337") (name "ST_DATA") (class "Default")
      (node (ref "B12") (pin "A1") (pinfunction "IN1_A1") (pintype "input"))
      (node (ref "C13") (pin "H2") (pinfunction "IN_H2") (pintype "input"))
      (node (ref "C16") (pin "J2") (pinfunction "OUT_J2") (pintype "output"))
    )
    (net (code "338") (name "ST_FINAL") (class "Default")
      (node (ref "A09") (pin "S2") (pinfunction "IN2_S2") (pintype "input"))
      (node (ref "A26") (pin "N1") (pinfunction "P$2_N1") (pintype "bidirectional"))
      (node (ref "C11") (pin "D1") (pinfunction "IN1_D1") (pintype "input"))
      (node (ref "C13") (pin "L1") (pinfunction "IN_L1") (pintype "input"))
      (node (ref "CD18") (pin "BL2") (pinfunction "BL2_BL2") (pintype "output"))
    )
    (net (code "339") (name "ST_IDLE") (class "Default")
      (node (ref "A26") (pin "R1") (pinfunction "P$2_R1") (pintype "bidirectional"))
      (node (ref "C13") (pin "K2") (pinfunction "IN_K2") (pintype "input"))
      (node (ref "CD18") (pin "BD2") (pinfunction "BD2_BD2") (pintype "input"))
    )
    (net (code "340") (name "ST_REV_CK") (class "Default")
      (node (ref "A26") (pin "L1") (pinfunction "P$2_L1") (pintype "bidirectional"))
      (node (ref "B11") (pin "S1") (pinfunction "IN3_S1") (pintype "input"))
      (node (ref "C11") (pin "A1") (pinfunction "IN1_A1") (pintype "input"))
      (node (ref "C13") (pin "D1") (pinfunction "IN_D1") (pintype "input"))
      (node (ref "CD18") (pin "BS1") (pinfunction "BS1_BS1") (pintype "output"))
      (node (ref "D12") (pin "F2") (pinfunction "IN3_F2") (pintype "input"))
      (node (ref "D12") (pin "H2") (pinfunction "IN4_H2") (pintype "input"))
    )
    (net (code "341") (name "SWTM") (class "Default")
      (node (ref "A26") (pin "V2") (pinfunction "P$2_V2") (pintype "bidirectional"))
      (node (ref "B06") (pin "P2") (pinfunction "IN_P2") (pintype "input"))
      (node (ref "B08") (pin "V1") (pinfunction "P$1_V1") (pintype "output"))
      (node (ref "B11") (pin "B1") (pinfunction "IN2_B1") (pintype "input"))
      (node (ref "C10") (pin "N2") (pinfunction "IN2B_N2") (pintype "input"))
      (node (ref "C12") (pin "P2") (pinfunction "IN2_P2") (pintype "input"))
      (node (ref "C15") (pin "L1") (pinfunction "IN1_L1") (pintype "input"))
    )
    (net (code "342") (name "SYNC") (class "Default")
      (node (ref "B10") (pin "D2") (pinfunction "IN1_D2") (pintype "input"))
      (node (ref "B10") (pin "E2") (pinfunction "IN2_E2") (pintype "input"))
      (node (ref "CD18") (pin "BN2") (pinfunction "BN2_BN2") (pintype "output"))
    )
    (net (code "343") (name "SYNC_EN") (class "Default")
      (node (ref "B11") (pin "M2") (pinfunction "OUT_M2") (pintype "output"))
    )
    (net (code "344") (name "T3") (class "Default")
      (node (ref "C17") (pin "S1") (pinfunction "OUT_S1") (pintype "output"))
      (node (ref "D12") (pin "N1") (pinfunction "IN2_N1") (pintype "input"))
      (node (ref "D12") (pin "P1") (pinfunction "IN3_P1") (pintype "input"))
    )
    (net (code "345") (name "TIM") (class "Default")
      (node (ref "A08") (pin "L1") (pinfunction "1_L1") (pintype "output"))
      (node (ref "A25") (pin "U1") (pinfunction "P$2_U1") (pintype "bidirectional"))
    )
    (net (code "346") (name "TM_EN") (class "Default")
      (node (ref "A18") (pin "R2") (pinfunction "R2_R2") (pintype "input"))
      (node (ref "B18") (pin "R2") (pinfunction "R2_R2") (pintype "input"))
      (node (ref "C13") (pin "N1") (pinfunction "IN_N1") (pintype "input"))
      (node (ref "C15") (pin "S1") (pinfunction "OUT_S1") (pintype "output"))
      (node (ref "C16") (pin "M1") (pinfunction "IN1_M1") (pintype "input"))
      (node (ref "C16") (pin "R2") (pinfunction "IN1_R2") (pintype "input"))
    )
    (net (code "347") (name "TP00") (class "Default")
      (node (ref "A08") (pin "B1") (pinfunction "C_B1") (pintype "input"))
      (node (ref "A15") (pin "L1") (pinfunction "OUT_L1") (pintype "output"))
      (node (ref "A16") (pin "M2") (pinfunction "K2_M2") (pintype "input"))
      (node (ref "A16") (pin "N2") (pinfunction "J2_N2") (pintype "input"))
      (node (ref "A16") (pin "P2") (pinfunction "H2_P2") (pintype "input"))
      (node (ref "B10") (pin "F2") (pinfunction "IN3_F2") (pintype "input"))
      (node (ref "B10") (pin "H2") (pinfunction "IN4_H2") (pintype "input"))
      (node (ref "B10") (pin "N1") (pinfunction "IN2_N1") (pintype "input"))
      (node (ref "B13") (pin "B1") (pinfunction "C_B1") (pintype "input"))
      (node (ref "B13") (pin "D2") (pinfunction "C_D2") (pintype "input"))
      (node (ref "B13") (pin "H1") (pinfunction "C_H1") (pintype "input"))
      (node (ref "B15") (pin "J1") (pinfunction "IN2_J1") (pintype "input"))
      (node (ref "C15") (pin "E1") (pinfunction "IN2_E1") (pintype "input"))
    )
    (net (code "348") (name "TP00_A") (class "Default")
      (node (ref "A15") (pin "S1") (pinfunction "OUT_S1") (pintype "output"))
      (node (ref "B10") (pin "H1") (pinfunction "IN2_H1") (pintype "input"))
      (node (ref "C12") (pin "E2") (pinfunction "IN2_E2") (pintype "input"))
    )
    (net (code "349") (name "TP01") (class "Default")
      (node (ref "A12") (pin "J2") (pinfunction "IN2_J2") (pintype "input"))
      (node (ref "A15") (pin "P2") (pinfunction "OUT_P2") (pintype "output"))
      (node (ref "B16") (pin "M2") (pinfunction "K2_M2") (pintype "input"))
      (node (ref "B16") (pin "N2") (pinfunction "J2_N2") (pintype "input"))
      (node (ref "B16") (pin "P2") (pinfunction "H2_P2") (pintype "input"))
      (node (ref "C11") (pin "J2") (pinfunction "IN2_J2") (pintype "input"))
      (node (ref "C15") (pin "B1") (pinfunction "IN2_B1") (pintype "input"))
      (node (ref "CD18") (pin "BF1") (pinfunction "BF1_BF1") (pintype "input"))
    )
    (net (code "350") (name "TP01_A") (class "Default")
      (node (ref "A15") (pin "V2") (pinfunction "OUT_V2") (pintype "output"))
      (node (ref "B12") (pin "T2") (pinfunction "IN3_T2") (pintype "input"))
      (node (ref "C15") (pin "M2") (pinfunction "IN2_M2") (pintype "input"))
    )
    (net (code "351") (name "T_TRK") (class "Default")
      (node (ref "A18") (pin "U2") (pinfunction "U2_U2") (pintype "output"))
      (node (ref "B15") (pin "E2") (pinfunction "IN2_E2") (pintype "input"))
      (node (ref "C15") (pin "R2") (pinfunction "IN2_R2") (pintype "input"))
      (node (ref "D14") (pin "S1") (pinfunction "S1_S1") (pintype "input"))
      (node (ref "D14") (pin "U1") (pinfunction "U1_U1") (pintype "input"))
    )
    (net (code "352") (name "U+M_DY") (class "Default")
      (node (ref "D14") (pin "K1") (pinfunction "H2_K1") (pintype "output"))
    )
    (net (code "353") (name "USR_00") (class "Default")
      (node (ref "A07") (pin "V2") (pinfunction "IN2_V2") (pintype "input"))
      (node (ref "A25") (pin "A1") (pinfunction "P$2_A1") (pintype "bidirectional"))
      (node (ref "B07") (pin "E1") (pinfunction "E1_E1") (pintype "output"))
    )
    (net (code "354") (name "USR_01") (class "Default")
      (node (ref "A07") (pin "U2") (pinfunction "IN1_U2") (pintype "input"))
      (node (ref "A25") (pin "B1") (pinfunction "P$2_B1") (pintype "bidirectional"))
      (node (ref "B07") (pin "H2") (pinfunction "H2_H2") (pintype "output"))
    )
    (net (code "355") (name "USR_02") (class "Default")
      (node (ref "A07") (pin "V1") (pinfunction "IN0_V1") (pintype "input"))
      (node (ref "A25") (pin "C1") (pinfunction "P$2_C1") (pintype "bidirectional"))
      (node (ref "B07") (pin "L1") (pinfunction "L1_L1") (pintype "output"))
    )
    (net (code "356") (name "UTS") (class "Default")
      (node (ref "A10") (pin "E1") (pinfunction "IN2_E1") (pintype "input"))
      (node (ref "A26") (pin "J1") (pinfunction "P$2_J1") (pintype "bidirectional"))
      (node (ref "B15") (pin "P1") (pinfunction "IN1_P1") (pintype "input"))
      (node (ref "C14") (pin "R2") (pinfunction "0_R2") (pintype "output"))
    )
    (net (code "357") (name "VCC") (class "Default")
      (node (ref "AB01") (pin "AA2") (pinfunction "VCC_AA2") (pintype "power_in"))
      (node (ref "AB01") (pin "AB1") (pinfunction "VCC_AB1") (pintype "power_in"))
      (node (ref "AB01") (pin "AC1") (pinfunction "VCC_AC1") (pintype "power_in"))
      (node (ref "AB01") (pin "AD1") (pinfunction "VCC_AD1") (pintype "power_in"))
      (node (ref "AB01") (pin "AE1") (pinfunction "VCC_AE1") (pintype "power_in"))
      (node (ref "AB01") (pin "AF1") (pinfunction "VCC_AF1") (pintype "power_in"))
      (node (ref "AB01") (pin "AH1") (pinfunction "VCC_AH1") (pintype "power_in"))
      (node (ref "AB01") (pin "AJ1") (pinfunction "VCC_AJ1") (pintype "power_in"))
      (node (ref "AB01") (pin "AK1") (pinfunction "VCC_AK1") (pintype "power_in"))
      (node (ref "AB01") (pin "AL1") (pinfunction "VCC_AL1") (pintype "power_in"))
      (node (ref "AB01") (pin "BA2") (pinfunction "VCC_BA2") (pintype "power_in"))
      (node (ref "AB01") (pin "BB1") (pinfunction "VCC_BB1") (pintype "power_in"))
      (node (ref "AB01") (pin "BC1") (pinfunction "VCC_BC1") (pintype "power_in"))
      (node (ref "AB01") (pin "BD1") (pinfunction "VCC_BD1") (pintype "power_in"))
      (node (ref "AB01") (pin "BE1") (pinfunction "VCC_BE1") (pintype "power_in"))
    )
    (net (code "358") (name "W+UTS") (class "Default")
      (node (ref "A15") (pin "A1") (pinfunction "IN1_A1") (pintype "input"))
      (node (ref "A15") (pin "H2") (pinfunction "IN4_H2") (pintype "input"))
      (node (ref "C12") (pin "M2") (pinfunction "OUT_M2") (pintype "output"))
    )
    (net (code "359") (name "W-INH") (class "Default")
      (node (ref "A08") (pin "V1") (pinfunction "0_V1") (pintype "output"))
    )
    (net (code "360") (name "W01") (class "Default")
      (node (ref "A26") (pin "J2") (pinfunction "P$2_J2") (pintype "bidirectional"))
      (node (ref "CD18") (pin "BJ2") (pinfunction "BJ2_BJ2") (pintype "output"))
    )
    (net (code "361") (name "W01-W05") (class "Default")
      (node (ref "CD18") (pin "AK1") (pinfunction "AK1_AK1") (pintype "output"))
    )
    (net (code "362") (name "W02") (class "Default")
      (node (ref "A26") (pin "K2") (pinfunction "P$2_K2") (pintype "bidirectional"))
      (node (ref "CD18") (pin "BV2") (pinfunction "BV2_BV2") (pintype "output"))
    )
    (net (code "363") (name "W03") (class "Default")
      (node (ref "A26") (pin "L2") (pinfunction "P$2_L2") (pintype "bidirectional"))
      (node (ref "CD18") (pin "BE2") (pinfunction "BE2_BE2") (pintype "output"))
    )
    (net (code "364") (name "W04") (class "Default")
      (node (ref "A26") (pin "M2") (pinfunction "P$2_M2") (pintype "bidirectional"))
      (node (ref "CD18") (pin "AT2") (pinfunction "AT2_AT2") (pintype "output"))
    )
    (net (code "365") (name "W05") (class "Default")
      (node (ref "A26") (pin "N2") (pinfunction "P$2_N2") (pintype "bidirectional"))
      (node (ref "CD18") (pin "BU2") (pinfunction "BU2_BU2") (pintype "output"))
    )
    (net (code "366") (name "W06") (class "Default")
      (node (ref "A26") (pin "P2") (pinfunction "P$2_P2") (pintype "bidirectional"))
      (node (ref "CD18") (pin "AM2") (pinfunction "AM2_AM2") (pintype "output"))
    )
    (net (code "367") (name "W07") (class "Default")
      (node (ref "A26") (pin "R2") (pinfunction "P$2_R2") (pintype "bidirectional"))
      (node (ref "CD18") (pin "AK2") (pinfunction "AK2_AK2") (pintype "output"))
    )
    (net (code "368") (name "W08") (class "Default")
      (node (ref "A26") (pin "S2") (pinfunction "P$2_S2") (pintype "bidirectional"))
      (node (ref "CD18") (pin "AL1") (pinfunction "AL1_AL1") (pintype "output"))
    )
    (net (code "369") (name "W09") (class "Default")
      (node (ref "A26") (pin "T2") (pinfunction "P$2_T2") (pintype "bidirectional"))
      (node (ref "CD18") (pin "BF2") (pinfunction "BF2_BF2") (pintype "output"))
    )
    (net (code "370") (name "WB00") (class "Default")
      (node (ref "A21") (pin "N2") (pinfunction "N2_N2") (pintype "input"))
      (node (ref "A25") (pin "P2") (pinfunction "P$2_P2") (pintype "bidirectional"))
      (node (ref "B18") (pin "N2") (pinfunction "N2_N2") (pintype "input"))
      (node (ref "C14") (pin "F1") (pinfunction "0_F1") (pintype "output"))
      (node (ref "D09") (pin "A1") (pinfunction "IN1A_A1") (pintype "input"))
    )
    (net (code "371") (name "WB01") (class "Default")
      (node (ref "A25") (pin "R2") (pinfunction "P$2_R2") (pintype "bidirectional"))
      (node (ref "B20") (pin "N2") (pinfunction "N2_N2") (pintype "input"))
      (node (ref "C14") (pin "J2") (pinfunction "0_J2") (pintype "output"))
      (node (ref "D09") (pin "F1") (pinfunction "IN1A_F1") (pintype "input"))
    )
    (net (code "372") (name "WB02") (class "Default")
      (node (ref "A20") (pin "N2") (pinfunction "N2_N2") (pintype "input"))
      (node (ref "A25") (pin "S2") (pinfunction "P$2_S2") (pintype "bidirectional"))
      (node (ref "C14") (pin "M1") (pinfunction "0_M1") (pintype "output"))
      (node (ref "D09") (pin "M1") (pinfunction "IN1A_M1") (pintype "input"))
    )
    (net (code "373") (name "WC") (class "Default")
      (node (ref "A26") (pin "H1") (pinfunction "P$2_H1") (pintype "bidirectional"))
      (node (ref "B10") (pin "M1") (pinfunction "IN1_M1") (pintype "input"))
      (node (ref "B11") (pin "K1") (pinfunction "IN1_K1") (pintype "input"))
      (node (ref "D11") (pin "S1") (pinfunction "1_S1") (pintype "output"))
    )
    (net (code "374") (name "WC0") (class "Default")
      (node (ref "C01") (pin "H1") (pinfunction "OUT_H1") (pintype "output"))
      (node (ref "C06") (pin "M2") (pinfunction "IN_M2") (pintype "input"))
    )
    (net (code "375") (name "WRITE_ALL") (class "Default")
      (node (ref "A08") (pin "S2") (pinfunction "C_S2") (pintype "input"))
      (node (ref "B11") (pin "M1") (pinfunction "IN3_M1") (pintype "input"))
      (node (ref "B12") (pin "F1") (pinfunction "IN1_F1") (pintype "input"))
      (node (ref "D07") (pin "M2") (pinfunction "O5_M2") (pintype "output"))
    )
    (net (code "376") (name "WRITE_DATA") (class "Default")
      (node (ref "A09") (pin "R2") (pinfunction "IN1_R2") (pintype "input"))
      (node (ref "B11") (pin "R1") (pinfunction "IN2_R1") (pintype "input"))
      (node (ref "B12") (pin "B1") (pinfunction "IN2_B1") (pintype "input"))
      (node (ref "D07") (pin "F2") (pinfunction "O4_F2") (pintype "output"))
    )
    (net (code "377") (name "WRITE_OK") (class "Default")
      (node (ref "A22") (pin "D2") (pinfunction "D2_D2") (pintype "output"))
      (node (ref "B11") (pin "C1") (pinfunction "IN3_C1") (pintype "input"))
      (node (ref "B15") (pin "R1") (pinfunction "IN2_R1") (pintype "input"))
      (node (ref "C17") (pin "H2") (pinfunction "IN_H2") (pintype "input"))
    )
    (net (code "378") (name "WRITE_OK+UTS") (class "Default")
      (node (ref "B12") (pin "D1") (pinfunction "IN4_D1") (pintype "input"))
      (node (ref "B12") (pin "K1") (pinfunction "IN4_K1") (pintype "input"))
      (node (ref "C17") (pin "M1") (pinfunction "OUT_M1") (pintype "output"))
    )
    (net (code "379") (name "WRTM") (class "Default")
      (node (ref "B11") (pin "A1") (pinfunction "IN1_A1") (pintype "input"))
      (node (ref "C10") (pin "K2") (pinfunction "IN1A_K2") (pintype "input"))
      (node (ref "C12") (pin "N2") (pinfunction "IN1_N2") (pintype "input"))
      (node (ref "D07") (pin "H2") (pinfunction "O6_H2") (pintype "output"))
    )
    (net (code "380") (name "WRTM+FR03") (class "Default")
      (node (ref "B08") (pin "K2") (pinfunction "OUT_K2") (pintype "output"))
      (node (ref "C12") (pin "M1") (pinfunction "IN3_M1") (pintype "input"))
      (node (ref "C12") (pin "V2") (pinfunction "IN3_V2") (pintype "input"))
    )
    (net (code "381") (name "WR_EN") (class "Default")
      (node (ref "A20") (pin "R2") (pinfunction "R2_R2") (pintype "input"))
      (node (ref "A21") (pin "R2") (pinfunction "R2_R2") (pintype "input"))
      (node (ref "A26") (pin "F1") (pinfunction "P$2_F1") (pintype "bidirectional"))
      (node (ref "B20") (pin "R2") (pinfunction "R2_R2") (pintype "input"))
      (node (ref "C10") (pin "H2") (pinfunction "IN2B_H2") (pintype "input"))
      (node (ref "C10") (pin "U2") (pinfunction "IN2B_U2") (pintype "input"))
      (node (ref "C12") (pin "D2") (pinfunction "IN1_D2") (pintype "input"))
      (node (ref "C14") (pin "U1") (pinfunction "0_U1") (pintype "output"))
      (node (ref "C15") (pin "A1") (pinfunction "IN1_A1") (pintype "input"))
      (node (ref "C15") (pin "M1") (pinfunction "IN2_M1") (pintype "input"))
      (node (ref "D09") (pin "B1") (pinfunction "IN1B_B1") (pintype "input"))
      (node (ref "D09") (pin "E2") (pinfunction "IN1B_E2") (pintype "input"))
      (node (ref "D09") (pin "H1") (pinfunction "IN1B_H1") (pintype "input"))
      (node (ref "D09") (pin "L2") (pinfunction "IN1B_L2") (pintype "input"))
      (node (ref "D09") (pin "N1") (pinfunction "IN1B_N1") (pintype "input"))
      (node (ref "D09") (pin "S2") (pinfunction "IN1B_S2") (pintype "input"))
    )
    (net (code "382") (name "XOR_TO_LPB") (class "Default")
      (node (ref "C10") (pin "E2") (pinfunction "IN1B_E2") (pintype "input"))
      (node (ref "C10") (pin "F2") (pinfunction "IN2A_F2") (pintype "input"))
      (node (ref "C10") (pin "S2") (pinfunction "IN1B_S2") (pintype "input"))
      (node (ref "C10") (pin "T2") (pinfunction "IN2A_T2") (pintype "input"))
      (node (ref "D12") (pin "P2") (pinfunction "OUT_P2") (pintype "output"))
    )
    (net (code "383") (name "XSAD") (class "Default")
      (node (ref "A09") (pin "R1") (pinfunction "IN4_R1") (pintype "input"))
      (node (ref "A11") (pin "L2") (pinfunction "OUT_L2") (pintype "output"))
    )
    (net (code "384") (name "XSA_DY") (class "Default")
      (node (ref "A08") (pin "D2") (pinfunction "C_D2") (pintype "input"))
      (node (ref "B14") (pin "B1") (pinfunction "C_B1") (pintype "input"))
      (node (ref "B14") (pin "L2") (pinfunction "C_L2") (pintype "input"))
      (node (ref "C17") (pin "T2") (pinfunction "OUT_T2") (pintype "output"))
    )
    (net (code "385") (name "XSTA") (class "Default")
      (node (ref "B07") (pin "B1") (pinfunction "B1_B1") (pintype "input"))
      (node (ref "B07") (pin "D2") (pinfunction "D2_D2") (pintype "input"))
      (node (ref "B07") (pin "H1") (pinfunction "H1_H1") (pintype "input"))
      (node (ref "B07") (pin "L2") (pinfunction "L2_L2") (pintype "input"))
      (node (ref "B07") (pin "N1") (pinfunction "N1_N1") (pintype "input"))
      (node (ref "B07") (pin "S2") (pinfunction "S2_S2") (pintype "input"))
      (node (ref "C04") (pin "F1") (pinfunction "F1_F1") (pintype "output"))
      (node (ref "C07") (pin "B1") (pinfunction "B1_B1") (pintype "input"))
      (node (ref "C07") (pin "D2") (pinfunction "D2_D2") (pintype "input"))
      (node (ref "C07") (pin "H1") (pinfunction "H1_H1") (pintype "input"))
      (node (ref "C07") (pin "L2") (pinfunction "L2_L2") (pintype "input"))
      (node (ref "D11") (pin "N1") (pinfunction "C_N1") (pintype "input"))
    )
    (net (code "386") (name "unconnected-(A07A-O8-PadP2)") (class "Default")
      (node (ref "A07") (pin "P2") (pinfunction "O8_P2") (pintype "output"))
    )
    (net (code "387") (name "unconnected-(A07A-O9-PadR2)") (class "Default")
      (node (ref "A07") (pin "R2") (pinfunction "O9_R2") (pintype "output"))
    )
    (net (code "388") (name "unconnected-(A07A-~{O8}-PadP1)") (class "Default")
      (node (ref "A07") (pin "P1") (pinfunction "~{O8}_P1") (pintype "output"))
    )
    (net (code "389") (name "unconnected-(A07A-~{O9}-PadR1)") (class "Default")
      (node (ref "A07") (pin "R1") (pinfunction "~{O9}_R1") (pintype "output"))
    )
    (net (code "390") (name "unconnected-(A14-PadD1)") (class "Default")
      (node (ref "A14") (pin "D1") (pinfunction "D1_D1") (pintype "passive"))
    )
    (net (code "391") (name "unconnected-(A14-PadE1)") (class "Default")
      (node (ref "A14") (pin "E1") (pinfunction "E1_E1") (pintype "passive"))
    )
    (net (code "392") (name "unconnected-(A14-PadF1)") (class "Default")
      (node (ref "A14") (pin "F1") (pinfunction "F1_F1") (pintype "passive"))
    )
    (net (code "393") (name "unconnected-(A14-PadJ1)") (class "Default")
      (node (ref "A14") (pin "J1") (pinfunction "J1_J1") (pintype "passive"))
    )
    (net (code "394") (name "unconnected-(A14B-D1-PadN1)") (class "Default")
      (node (ref "A14") (pin "N1") (pinfunction "D1_N1") (pintype "passive"))
    )
    (net (code "395") (name "unconnected-(A14B-E1-PadP1)") (class "Default")
      (node (ref "A14") (pin "P1") (pinfunction "E1_P1") (pintype "passive"))
    )
    (net (code "396") (name "unconnected-(A14B-F1-PadR1)") (class "Default")
      (node (ref "A14") (pin "R1") (pinfunction "F1_R1") (pintype "passive"))
    )
    (net (code "397") (name "unconnected-(A14B-J1-PadU1)") (class "Default")
      (node (ref "A14") (pin "U1") (pinfunction "J1_U1") (pintype "passive"))
    )
    (net (code "398") (name "unconnected-(A18-PadH2)") (class "Default")
      (node (ref "A18") (pin "H2") (pinfunction "H2_H2") (pintype "input"))
    )
    (net (code "399") (name "unconnected-(A18-PadL2)") (class "Default")
      (node (ref "A18") (pin "L2") (pinfunction "L2_L2") (pintype "input"))
    )
    (net (code "400") (name "unconnected-(A18-PadM2)") (class "Default")
      (node (ref "A18") (pin "M2") (pinfunction "M2_M2") (pintype "input"))
    )
    (net (code "401") (name "unconnected-(A20-PadH2)") (class "Default")
      (node (ref "A20") (pin "H2") (pinfunction "H2_H2") (pintype "input"))
    )
    (net (code "402") (name "unconnected-(A20-PadL2)") (class "Default")
      (node (ref "A20") (pin "L2") (pinfunction "L2_L2") (pintype "input"))
    )
    (net (code "403") (name "unconnected-(A20-PadM2)") (class "Default")
      (node (ref "A20") (pin "M2") (pinfunction "M2_M2") (pintype "input"))
    )
    (net (code "404") (name "unconnected-(A21-PadH2)") (class "Default")
      (node (ref "A21") (pin "H2") (pinfunction "H2_H2") (pintype "input"))
    )
    (net (code "405") (name "unconnected-(A21-PadL2)") (class "Default")
      (node (ref "A21") (pin "L2") (pinfunction "L2_L2") (pintype "input"))
    )
    (net (code "406") (name "unconnected-(A21-PadM2)") (class "Default")
      (node (ref "A21") (pin "M2") (pinfunction "M2_M2") (pintype "input"))
    )
    (net (code "407") (name "unconnected-(A22-PadE2)") (class "Default")
      (node (ref "A22") (pin "E2") (pinfunction "E2_E2") (pintype "passive"))
    )
    (net (code "408") (name "unconnected-(AB01-PadBM1)") (class "Default")
      (node (ref "AB01") (pin "BM1") (pinfunction "BM1_BM1") (pintype "output"))
    )
    (net (code "409") (name "unconnected-(AB01-PadBN1)") (class "Default")
      (node (ref "AB01") (pin "BN1") (pinfunction "BN1_BN1") (pintype "input"))
    )
    (net (code "410") (name "unconnected-(AB01-PadBP1)") (class "Default")
      (node (ref "AB01") (pin "BP1") (pinfunction "BP1_BP1") (pintype "input"))
    )
    (net (code "411") (name "unconnected-(AB01-PadBR1)") (class "Default")
      (node (ref "AB01") (pin "BR1") (pinfunction "BR1_BR1") (pintype "output"))
    )
    (net (code "412") (name "unconnected-(B05F-B-PadL2)") (class "Default")
      (node (ref "B05") (pin "L2") (pinfunction "B_L2") (pintype "input"))
    )
    (net (code "413") (name "unconnected-(B05F-E-PadP2)") (class "Default")
      (node (ref "B05") (pin "P2") (pinfunction "E_P2") (pintype "open_collector"))
    )
    (net (code "414") (name "unconnected-(B18-PadH2)") (class "Default")
      (node (ref "B18") (pin "H2") (pinfunction "H2_H2") (pintype "input"))
    )
    (net (code "415") (name "unconnected-(B18-PadL2)") (class "Default")
      (node (ref "B18") (pin "L2") (pinfunction "L2_L2") (pintype "input"))
    )
    (net (code "416") (name "unconnected-(B18-PadM2)") (class "Default")
      (node (ref "B18") (pin "M2") (pinfunction "M2_M2") (pintype "input"))
    )
    (net (code "417") (name "unconnected-(B20-PadH2)") (class "Default")
      (node (ref "B20") (pin "H2") (pinfunction "H2_H2") (pintype "input"))
    )
    (net (code "418") (name "unconnected-(B20-PadL2)") (class "Default")
      (node (ref "B20") (pin "L2") (pinfunction "L2_L2") (pintype "input"))
    )
    (net (code "419") (name "unconnected-(B20-PadM2)") (class "Default")
      (node (ref "B20") (pin "M2") (pinfunction "M2_M2") (pintype "input"))
    )
    (net (code "420") (name "unconnected-(B22H-A-PadR2)") (class "Default")
      (node (ref "B22") (pin "R2") (pinfunction "A_R2") (pintype "input"))
    )
    (net (code "421") (name "unconnected-(B22H-D-PadU2)") (class "Default")
      (node (ref "B22") (pin "U2") (pinfunction "D_U2") (pintype "output"))
    )
    (net (code "422") (name "unconnected-(C02A-IN13-PadP2)") (class "Default")
      (node (ref "C02") (pin "P2") (pinfunction "IN13_P2") (pintype "input"))
    )
    (net (code "423") (name "unconnected-(C02A-IN14-PadS2)") (class "Default")
      (node (ref "C02") (pin "S2") (pinfunction "IN14_S2") (pintype "input"))
    )
    (net (code "424") (name "unconnected-(C02A-O13-PadR2)") (class "Default")
      (node (ref "C02") (pin "R2") (pinfunction "O13_R2") (pintype "output"))
    )
    (net (code "425") (name "unconnected-(C02A-O14-PadT2)") (class "Default")
      (node (ref "C02") (pin "T2") (pinfunction "O14_T2") (pintype "output"))
    )
    (net (code "426") (name "unconnected-(C03A-IN13-PadP2)") (class "Default")
      (node (ref "C03") (pin "P2") (pinfunction "IN13_P2") (pintype "input"))
    )
    (net (code "427") (name "unconnected-(C03A-IN14-PadS2)") (class "Default")
      (node (ref "C03") (pin "S2") (pinfunction "IN14_S2") (pintype "input"))
    )
    (net (code "428") (name "unconnected-(C03A-IN15-PadU2)") (class "Default")
      (node (ref "C03") (pin "U2") (pinfunction "IN15_U2") (pintype "input"))
    )
    (net (code "429") (name "unconnected-(C03A-O13-PadR2)") (class "Default")
      (node (ref "C03") (pin "R2") (pinfunction "O13_R2") (pintype "output"))
    )
    (net (code "430") (name "unconnected-(C03A-O14-PadT2)") (class "Default")
      (node (ref "C03") (pin "T2") (pinfunction "O14_T2") (pintype "output"))
    )
    (net (code "431") (name "unconnected-(C03A-O15-PadV2)") (class "Default")
      (node (ref "C03") (pin "V2") (pinfunction "O15_V2") (pintype "output"))
    )
    (net (code "432") (name "unconnected-(C07-PadN1)") (class "Default")
      (node (ref "C07") (pin "N1") (pinfunction "N1_N1") (pintype "input"))
    )
    (net (code "433") (name "unconnected-(C07-PadP1)") (class "Default")
      (node (ref "C07") (pin "P1") (pinfunction "P1_P1") (pintype "input"))
    )
    (net (code "434") (name "unconnected-(C07-PadR1)") (class "Default")
      (node (ref "C07") (pin "R1") (pinfunction "R1_R1") (pintype "input"))
    )
    (net (code "435") (name "unconnected-(C07-PadS1)") (class "Default")
      (node (ref "C07") (pin "S1") (pinfunction "S1_S1") (pintype "output"))
    )
    (net (code "436") (name "unconnected-(C07-PadS2)") (class "Default")
      (node (ref "C07") (pin "S2") (pinfunction "S2_S2") (pintype "input"))
    )
    (net (code "437") (name "unconnected-(C07-PadT2)") (class "Default")
      (node (ref "C07") (pin "T2") (pinfunction "T2_T2") (pintype "input"))
    )
    (net (code "438") (name "unconnected-(C07-PadU1)") (class "Default")
      (node (ref "C07") (pin "U1") (pinfunction "U1_U1") (pintype "output"))
    )
    (net (code "439") (name "unconnected-(C07-PadU2)") (class "Default")
      (node (ref "C07") (pin "U2") (pinfunction "U2_U2") (pintype "input"))
    )
    (net (code "440") (name "unconnected-(C07-PadV1)") (class "Default")
      (node (ref "C07") (pin "V1") (pinfunction "V1_V1") (pintype "output"))
    )
    (net (code "441") (name "unconnected-(C07-PadV2)") (class "Default")
      (node (ref "C07") (pin "V2") (pinfunction "V2_V2") (pintype "output"))
    )
    (net (code "442") (name "unconnected-(CD18-PadAN2)") (class "Default")
      (node (ref "CD18") (pin "AN2") (pinfunction "AN2_AN2") (pintype "output"))
    )
    (net (code "443") (name "unconnected-(CD18-PadAU1)") (class "Default")
      (node (ref "CD18") (pin "AU1") (pinfunction "AU1_AU1") (pintype "output"))
    )
    (net (code "444") (name "unconnected-(D07A-O8-PadP2)") (class "Default")
      (node (ref "D07") (pin "P2") (pinfunction "O8_P2") (pintype "output"))
    )
    (net (code "445") (name "unconnected-(D07A-O9-PadR2)") (class "Default")
      (node (ref "D07") (pin "R2") (pinfunction "O9_R2") (pintype "output"))
    )
    (net (code "446") (name "unconnected-(D07A-~{O8}-PadP1)") (class "Default")
      (node (ref "D07") (pin "P1") (pinfunction "~{O8}_P1") (pintype "output"))
    )
    (net (code "447") (name "unconnected-(D07A-~{O9}-PadR1)") (class "Default")
      (node (ref "D07") (pin "R1") (pinfunction "~{O9}_R1") (pintype "output"))
    )
    (net (code "448") (name "unconnected-(D13-PadD2)") (class "Default")
      (node (ref "D13") (pin "D2") (pinfunction "D2_D2") (pintype "passive"))
    )
    (net (code "449") (name "unconnected-(D13-PadE2)") (class "Default")
      (node (ref "D13") (pin "E2") (pinfunction "E2_E2") (pintype "passive"))
    )
    (net (code "450") (name "unconnected-(D14-PadN2)") (class "Default")
      (node (ref "D14") (pin "N2") (pinfunction "N2_N2") (pintype "passive"))
    )
    (net (code "451") (name "unconnected-(D14-PadP2)") (class "Default")
      (node (ref "D14") (pin "P2") (pinfunction "P2_P2") (pintype "passive"))
    )
    (net (code "452") (name "unconnected-(D14-PadR2)") (class "Default")
      (node (ref "D14") (pin "R2") (pinfunction "R2_R2") (pintype "passive"))
    )
    (net (code "453") (name "unconnected-(D14-PadS2)") (class "Default")
      (node (ref "D14") (pin "S2") (pinfunction "S2_S2") (pintype "passive"))
    )
    (net (code "454") (name "unconnected-(D14-PadU2)") (class "Default")
      (node (ref "D14") (pin "U2") (pinfunction "U2_U2") (pintype "passive"))
    )
    (net (code "455") (name "unconnected-(D14B-N2-PadJ1)") (class "Default")
      (node (ref "D14") (pin "J1") (pinfunction "N2_J1") (pintype "passive"))
    )
    (net (code "456") (name "unconnected-(D14B-R2-PadF1)") (class "Default")
      (node (ref "D14") (pin "F1") (pinfunction "R2_F1") (pintype "passive"))
    )
    (net (code "457") (name "unconnected-(D14B-S2-PadE1)") (class "Default")
      (node (ref "D14") (pin "E1") (pinfunction "S2_E1") (pintype "passive"))
    )
    (net (code "458") (name "unconnected-(D14B-U2-PadD1)") (class "Default")
      (node (ref "D14") (pin "D1") (pinfunction "U2_D1") (pintype "passive"))
    )
    (net (code "459") (name "unconnected-(D14B-V2-PadB1)") (class "Default")
      (node (ref "D14") (pin "B1") (pinfunction "V2_B1") (pintype "passive"))
    )
    (net (code "460") (name "unconnected-(D15-PadE2)") (class "Default")
      (node (ref "D15") (pin "E2") (pinfunction "E2_E2") (pintype "output"))
    )
    (net (code "461") (name "unconnected-(D15-PadM2)") (class "Default")
      (node (ref "D15") (pin "M2") (pinfunction "M2_M2") (pintype "passive"))
    )
    (net (code "462") (name "unconnected-(D15-PadP2)") (class "Default")
      (node (ref "D15") (pin "P2") (pinfunction "P2_P2") (pintype "passive"))
    )
    (net (code "463") (name "unconnected-(D15-PadR2)") (class "Default")
      (node (ref "D15") (pin "R2") (pinfunction "R2_R2") (pintype "passive"))
    )
    (net (code "464") (name "unconnected-(D15-PadT2)") (class "Default")
      (node (ref "D15") (pin "T2") (pinfunction "T2_T2") (pintype "passive"))
    )
    (net (code "465") (name "unconnected-(D16B-D1-PadN1)") (class "Default")
      (node (ref "D16") (pin "N1") (pinfunction "D1_N1") (pintype "passive"))
    )
    (net (code "466") (name "unconnected-(D16B-E1-PadP1)") (class "Default")
      (node (ref "D16") (pin "P1") (pinfunction "E1_P1") (pintype "passive"))
    )
    (net (code "467") (name "unconnected-(D16B-F1-PadR1)") (class "Default")
      (node (ref "D16") (pin "R1") (pinfunction "F1_R1") (pintype "passive"))
    )
    (net (code "468") (name "unconnected-(D16B-J1-PadU1)") (class "Default")
      (node (ref "D16") (pin "U1") (pinfunction "J1_U1") (pintype "passive"))
    )
    (net (code "469") (name "~{-ADDR_ACC}") (class "Default")
      (node (ref "C02") (pin "V2") (pinfunction "O15_V2") (pintype "output"))
      (node (ref "C17") (pin "N1") (pinfunction "IN_N1") (pintype "input"))
    )
    (net (code "470") (name "~{-WRITE_DATA}") (class "Default")
      (node (ref "B12") (pin "P1") (pinfunction "IN3_P1") (pintype "input"))
    )
    (net (code "471") (name "~{-XSTA}") (class "Default")
      (node (ref "D13") (pin "M2") (pinfunction "K2_M2") (pintype "input"))
      (node (ref "D13") (pin "N2") (pinfunction "J2_N2") (pintype "input"))
      (node (ref "D13") (pin "P2") (pinfunction "H2_P2") (pintype "input"))
    )
    (net (code "472") (name "~{0_TO_AC}") (class "Default")
      (node (ref "B05") (pin "H1") (pinfunction "B_H1") (pintype "input"))
      (node (ref "B06") (pin "T2") (pinfunction "OUT_T2") (pintype "output"))
    )
    (net (code "473") (name "~{0_TO_DTB}") (class "Default")
      (node (ref "A11") (pin "L1") (pinfunction "IN_L1") (pintype "input"))
      (node (ref "B09") (pin "A1") (pinfunction "R_A1") (pintype "input"))
      (node (ref "B09") (pin "K2") (pinfunction "R_K2") (pintype "input"))
      (node (ref "B10") (pin "L1") (pinfunction "OUT_L1") (pintype "output"))
      (node (ref "C09") (pin "A1") (pinfunction "R_A1") (pintype "input"))
      (node (ref "C09") (pin "K2") (pinfunction "R_K2") (pintype "input"))
    )
    (net (code "474") (name "~{0_TO_EF}") (class "Default")
      (node (ref "A08") (pin "A1") (pinfunction "R_A1") (pintype "input"))
      (node (ref "A08") (pin "N2") (pinfunction "S_N2") (pintype "input"))
      (node (ref "A08") (pin "R1") (pinfunction "S_R1") (pintype "input"))
      (node (ref "A11") (pin "F2") (pinfunction "OUT_F2") (pintype "output"))
    )
    (net (code "475") (name "~{0_TO_LPB}") (class "Default")
      (node (ref "D08") (pin "A1") (pinfunction "A1_A1") (pintype "input"))
      (node (ref "D08") (pin "K2") (pinfunction "K2_K2") (pintype "input"))
      (node (ref "D12") (pin "J2") (pinfunction "OUT_J2") (pintype "output"))
    )
    (net (code "476") (name "~{0_TO_STATE}") (class "Default")
      (node (ref "C16") (pin "L1") (pinfunction "OUT_L1") (pintype "output"))
      (node (ref "CD18") (pin "AV2") (pinfunction "AV2_AV2") (pintype "input"))
    )
    (net (code "477") (name "~{0_TO_STA}") (class "Default")
      (node (ref "A11") (pin "P1") (pinfunction "OUT_P1") (pintype "output"))
      (node (ref "B07") (pin "A1") (pinfunction "A1_A1") (pintype "input"))
      (node (ref "B07") (pin "K2") (pinfunction "K2_K2") (pintype "input"))
      (node (ref "B11") (pin "P2") (pinfunction "IN2_P2") (pintype "input"))
      (node (ref "C07") (pin "A1") (pinfunction "A1_A1") (pintype "input"))
    )
    (net (code "478") (name "~{0_TO_W}") (class "Default")
      (node (ref "C16") (pin "E1") (pinfunction "OUT_E1") (pintype "output"))
      (node (ref "CD18") (pin "BH2") (pinfunction "BH2_BH2") (pintype "input"))
    )
    (net (code "479") (name "~{00}") (class "Default")
      (node (ref "A07") (pin "D1") (pinfunction "~{O0}_D1") (pintype "output"))
      (node (ref "B22") (pin "S2") (pinfunction "B_S2") (pintype "input"))
    )
    (net (code "480") (name "~{01}") (class "Default")
      (node (ref "A07") (pin "E1") (pinfunction "~{O1}_E1") (pintype "output"))
      (node (ref "A23") (pin "N1") (pinfunction "B_N1") (pintype "input"))
    )
    (net (code "481") (name "~{02}") (class "Default")
      (node (ref "A07") (pin "J1") (pinfunction "~{O2}_J1") (pintype "output"))
      (node (ref "A23") (pin "D2") (pinfunction "A_D2") (pintype "input"))
    )
    (net (code "482") (name "~{03}") (class "Default")
      (node (ref "A07") (pin "N1") (pinfunction "~{O3}_N1") (pintype "output"))
      (node (ref "A23") (pin "E2") (pinfunction "B_E2") (pintype "input"))
    )
    (net (code "483") (name "~{04}") (class "Default")
      (node (ref "A07") (pin "F1") (pinfunction "~{O4}_F1") (pintype "output"))
      (node (ref "A23") (pin "K2") (pinfunction "A_K2") (pintype "input"))
    )
    (net (code "484") (name "~{05}") (class "Default")
      (node (ref "A07") (pin "M1") (pinfunction "~{O5}_M1") (pintype "output"))
      (node (ref "A23") (pin "L2") (pinfunction "B_L2") (pintype "input"))
    )
    (net (code "485") (name "~{06}") (class "Default")
      (node (ref "A07") (pin "H1") (pinfunction "~{O6}_H1") (pintype "output"))
      (node (ref "A23") (pin "R2") (pinfunction "A_R2") (pintype "input"))
    )
    (net (code "486") (name "~{07}") (class "Default")
      (node (ref "A07") (pin "L1") (pinfunction "~{O7}_L1") (pintype "output"))
      (node (ref "A23") (pin "S2") (pinfunction "B_S2") (pintype "input"))
    )
    (net (code "487") (name "~{76}") (class "Default")
      (node (ref "C06") (pin "T2") (pinfunction "OUT_T2") (pintype "output"))
      (node (ref "D12") (pin "R2") (pinfunction "IN1_R2") (pintype "input"))
      (node (ref "D12") (pin "S2") (pinfunction "IN2_S2") (pintype "input"))
    )
    (net (code "488") (name "~{77}") (class "Default")
      (node (ref "C06") (pin "V2") (pinfunction "OUT_V2") (pintype "output"))
      (node (ref "D12") (pin "T2") (pinfunction "IN3_T2") (pintype "input"))
      (node (ref "D12") (pin "U2") (pinfunction "IN4_U2") (pintype "input"))
    )
    (net (code "489") (name "~{ADDR_ACC}") (class "Default")
      (node (ref "B08") (pin "T2") (pinfunction "IN1_T2") (pintype "input"))
    )
    (net (code "490") (name "~{B-BRK}") (class "Default")
      (node (ref "B02") (pin "C1") (pinfunction "C_C1") (pintype "input"))
      (node (ref "B02") (pin "F2") (pinfunction "C_F2") (pintype "input"))
      (node (ref "B02") (pin "J1") (pinfunction "C_J1") (pintype "input"))
      (node (ref "B02") (pin "M2") (pinfunction "C_M2") (pintype "input"))
      (node (ref "B02") (pin "P1") (pinfunction "C_P1") (pintype "input"))
      (node (ref "B02") (pin "T2") (pinfunction "C_T2") (pintype "input"))
      (node (ref "B10") (pin "V2") (pinfunction "OUT_V2") (pintype "output"))
    )
    (net (code "491") (name "~{BAC_00}") (class "Default")
      (node (ref "B06") (pin "A1") (pinfunction "IN_A1") (pintype "input"))
      (node (ref "C03") (pin "B1") (pinfunction "O1_B1") (pintype "output"))
      (node (ref "D10") (pin "F1") (pinfunction "IN1_F1") (pintype "input"))
    )
    (net (code "492") (name "~{BAC_01}") (class "Default")
      (node (ref "B06") (pin "D1") (pinfunction "IN_D1") (pintype "input"))
      (node (ref "C03") (pin "E1") (pinfunction "O2_E1") (pintype "output"))
      (node (ref "D10") (pin "H1") (pinfunction "IN2_H1") (pintype "input"))
    )
    (net (code "493") (name "~{BAC_02}") (class "Default")
      (node (ref "B06") (pin "F1") (pinfunction "IN_F1") (pintype "input"))
      (node (ref "C03") (pin "H1") (pinfunction "O3_H1") (pintype "output"))
      (node (ref "D10") (pin "J1") (pinfunction "IN3_J1") (pintype "input"))
    )
    (net (code "494") (name "~{BAC_03}") (class "Default")
      (node (ref "B06") (pin "J1") (pinfunction "IN_J1") (pintype "input"))
      (node (ref "C03") (pin "K1") (pinfunction "O4_K1") (pintype "output"))
      (node (ref "D10") (pin "K1") (pinfunction "IN4_K1") (pintype "input"))
    )
    (net (code "495") (name "~{BAC_04}") (class "Default")
      (node (ref "B06") (pin "L1") (pinfunction "IN_L1") (pintype "input"))
      (node (ref "C03") (pin "M1") (pinfunction "O5_M1") (pintype "output"))
      (node (ref "D10") (pin "K2") (pinfunction "IN5_K2") (pintype "input"))
    )
    (net (code "496") (name "~{BAC_05}") (class "Default")
      (node (ref "B06") (pin "N1") (pinfunction "IN_N1") (pintype "input"))
      (node (ref "C03") (pin "P1") (pinfunction "O6_P1") (pintype "output"))
    )
    (net (code "497") (name "~{BAC_06}") (class "Default")
      (node (ref "B06") (pin "R1") (pinfunction "IN_R1") (pintype "input"))
      (node (ref "C03") (pin "S1") (pinfunction "O7_S1") (pintype "output"))
    )
    (net (code "498") (name "~{BAC_07}") (class "Default")
      (node (ref "B06") (pin "V1") (pinfunction "IN_V1") (pintype "input"))
      (node (ref "C03") (pin "U1") (pinfunction "O8_U1") (pintype "output"))
    )
    (net (code "499") (name "~{BAC_08}") (class "Default")
      (node (ref "B06") (pin "C1") (pinfunction "IN_C1") (pintype "input"))
      (node (ref "C03") (pin "F2") (pinfunction "O9_F2") (pintype "output"))
    )
    (net (code "500") (name "~{BAC_09}") (class "Default")
      (node (ref "B06") (pin "E2") (pinfunction "IN_E2") (pintype "input"))
      (node (ref "C03") (pin "J2") (pinfunction "O10_J2") (pintype "output"))
    )
    (net (code "501") (name "~{BAC_10}") (class "Default")
      (node (ref "A10") (pin "D2") (pinfunction "IN1_D2") (pintype "input"))
      (node (ref "B06") (pin "H2") (pinfunction "IN_H2") (pintype "input"))
      (node (ref "C03") (pin "L2") (pinfunction "O11_L2") (pintype "output"))
    )
    (net (code "502") (name "~{BAC_11}") (class "Default")
      (node (ref "B06") (pin "K2") (pinfunction "IN_K2") (pintype "input"))
      (node (ref "C03") (pin "N2") (pinfunction "O12_N2") (pintype "output"))
      (node (ref "C11") (pin "R2") (pinfunction "IN2_R2") (pintype "input"))
    )
    (net (code "503") (name "~{BLK_IN_SYNC}") (class "Default")
      (node (ref "A10") (pin "A1") (pinfunction "IN1_A1") (pintype "input"))
      (node (ref "C13") (pin "R1") (pinfunction "IN_R1") (pintype "input"))
      (node (ref "D10") (pin "J2") (pinfunction "OUT_J2") (pintype "output"))
    )
    (net (code "504") (name "~{BMB_00}") (class "Default")
      (node (ref "C02") (pin "B1") (pinfunction "O1_B1") (pintype "output"))
      (node (ref "C06") (pin "A1") (pinfunction "IN_A1") (pintype "input"))
    )
    (net (code "505") (name "~{BMB_01}") (class "Default")
      (node (ref "C02") (pin "E1") (pinfunction "O2_E1") (pintype "output"))
      (node (ref "C06") (pin "D1") (pinfunction "IN_D1") (pintype "input"))
    )
    (net (code "506") (name "~{BMB_02}") (class "Default")
      (node (ref "C02") (pin "H1") (pinfunction "O3_H1") (pintype "output"))
      (node (ref "C06") (pin "F1") (pinfunction "IN_F1") (pintype "input"))
    )
    (net (code "507") (name "~{BMB_03}") (class "Default")
      (node (ref "C02") (pin "K1") (pinfunction "O4_K1") (pintype "output"))
      (node (ref "C06") (pin "J1") (pinfunction "IN_J1") (pintype "input"))
    )
    (net (code "508") (name "~{BMB_04}") (class "Default")
      (node (ref "C02") (pin "M1") (pinfunction "O5_M1") (pintype "output"))
      (node (ref "C06") (pin "L1") (pinfunction "IN_L1") (pintype "input"))
    )
    (net (code "509") (name "~{BMB_05}") (class "Default")
      (node (ref "C02") (pin "P1") (pinfunction "O6_P1") (pintype "output"))
      (node (ref "C06") (pin "N1") (pinfunction "IN_N1") (pintype "input"))
    )
    (net (code "510") (name "~{BMB_06}") (class "Default")
      (node (ref "C02") (pin "S1") (pinfunction "O7_S1") (pintype "output"))
      (node (ref "C06") (pin "R1") (pinfunction "IN_R1") (pintype "input"))
    )
    (net (code "511") (name "~{BMB_07}") (class "Default")
      (node (ref "C02") (pin "U1") (pinfunction "O8_U1") (pintype "output"))
      (node (ref "C06") (pin "V1") (pinfunction "IN_V1") (pintype "input"))
    )
    (net (code "512") (name "~{BMB_08}") (class "Default")
      (node (ref "C02") (pin "F2") (pinfunction "O9_F2") (pintype "output"))
      (node (ref "C06") (pin "C1") (pinfunction "IN_C1") (pintype "input"))
    )
    (net (code "513") (name "~{BMB_09}") (class "Default")
      (node (ref "C02") (pin "J2") (pinfunction "O10_J2") (pintype "output"))
      (node (ref "C06") (pin "E2") (pinfunction "IN_E2") (pintype "input"))
    )
    (net (code "514") (name "~{BMB_10}") (class "Default")
      (node (ref "C02") (pin "L2") (pinfunction "O11_L2") (pintype "output"))
      (node (ref "C06") (pin "H2") (pinfunction "IN_H2") (pintype "input"))
    )
    (net (code "515") (name "~{BMB_11}") (class "Default")
      (node (ref "C02") (pin "N2") (pinfunction "O12_N2") (pintype "output"))
      (node (ref "C06") (pin "K2") (pinfunction "IN_K2") (pintype "input"))
    )
    (net (code "516") (name "~{BMR00}") (class "Default")
      (node (ref "A23") (pin "H1") (pinfunction "B_H1") (pintype "input"))
      (node (ref "B14") (pin "R2") (pinfunction "0_R2") (pintype "output"))
    )
    (net (code "517") (name "~{BMR01}") (class "Default")
      (node (ref "A23") (pin "A1") (pinfunction "A_A1") (pintype "input"))
      (node (ref "B14") (pin "E1") (pinfunction "1_E1") (pintype "output"))
    )
    (net (code "518") (name "~{C00}") (class "Default")
      (node (ref "A12") (pin "P2") (pinfunction "IN1_P2") (pintype "input"))
      (node (ref "B13") (pin "P1") (pinfunction "D_P1") (pintype "input"))
      (node (ref "B13") (pin "S2") (pinfunction "C_S2") (pintype "input"))
      (node (ref "B13") (pin "U1") (pinfunction "0_U1") (pintype "output"))
      (node (ref "B15") (pin "H1") (pinfunction "IN1_H1") (pintype "input"))
      (node (ref "C15") (pin "J2") (pinfunction "IN2_J2") (pintype "input"))
    )
    (net (code "519") (name "~{C01}") (class "Default")
      (node (ref "A12") (pin "R2") (pinfunction "IN2_R2") (pintype "input"))
      (node (ref "B10") (pin "P1") (pinfunction "IN3_P1") (pintype "input"))
      (node (ref "B13") (pin "M2") (pinfunction "D_M2") (pintype "input"))
      (node (ref "B13") (pin "R2") (pinfunction "0_R2") (pintype "output"))
      (node (ref "C12") (pin "F2") (pinfunction "IN3_F2") (pintype "input"))
      (node (ref "D10") (pin "D1") (pinfunction "IN4_D1") (pintype "input"))
    )
    (net (code "520") (name "~{CK00}") (class "Default")
      (node (ref "A18") (pin "N2") (pinfunction "N2_N2") (pintype "input"))
      (node (ref "B14") (pin "T2") (pinfunction "D_T2") (pintype "input"))
      (node (ref "B14") (pin "U1") (pinfunction "0_U1") (pintype "output"))
    )
    (net (code "521") (name "~{CK01}") (class "Default")
      (node (ref "B14") (pin "V1") (pinfunction "0_V1") (pintype "output"))
      (node (ref "C16") (pin "S2") (pinfunction "IN2_S2") (pintype "input"))
      (node (ref "C16") (pin "T2") (pinfunction "IN3_T2") (pintype "input"))
      (node (ref "C16") (pin "U2") (pinfunction "IN4_U2") (pintype "input"))
    )
    (net (code "522") (name "~{CLR_DF}") (class "Default")
      (node (ref "A11") (pin "U1") (pinfunction "OUT_U1") (pintype "output"))
      (node (ref "D11") (pin "N2") (pinfunction "S_N2") (pintype "input"))
    )
    (net (code "523") (name "~{CLR_DTF}") (class "Default")
      (node (ref "C13") (pin "U1") (pinfunction "OUT_U1") (pintype "output"))
      (node (ref "D11") (pin "U2") (pinfunction "S_U2") (pintype "input"))
    )
    (net (code "524") (name "~{CSTA}") (class "Default")
      (node (ref "A10") (pin "L2") (pinfunction "IN1_L2") (pintype "input"))
      (node (ref "C04") (pin "C1") (pinfunction "C1_C1") (pintype "output"))
    )
    (net (code "525") (name "~{DATA}") (class "Default")
      (node (ref "B12") (pin "N1") (pinfunction "IN2_N1") (pintype "input"))
      (node (ref "C11") (pin "L2") (pinfunction "IN1_L2") (pintype "input"))
      (node (ref "C13") (pin "H1") (pinfunction "OUT_H1") (pintype "output"))
      (node (ref "C16") (pin "D2") (pinfunction "IN1_D2") (pintype "input"))
    )
    (net (code "526") (name "~{DB_00}") (class "Default")
      (node (ref "A06") (pin "B1") (pinfunction "P$2_B1") (pintype "bidirectional"))
      (node (ref "B02") (pin "D1") (pinfunction "D_D1") (pintype "open_collector"))
      (node (ref "D06") (pin "B1") (pinfunction "P$2_B1") (pintype "bidirectional"))
    )
    (net (code "527") (name "~{DB_01}") (class "Default")
      (node (ref "A06") (pin "D1") (pinfunction "P$2_D1") (pintype "bidirectional"))
      (node (ref "B02") (pin "E1") (pinfunction "E_E1") (pintype "open_collector"))
      (node (ref "D06") (pin "D1") (pinfunction "P$2_D1") (pintype "bidirectional"))
    )
    (net (code "528") (name "~{DB_02}") (class "Default")
      (node (ref "A06") (pin "E1") (pinfunction "P$2_E1") (pintype "bidirectional"))
      (node (ref "B02") (pin "K1") (pinfunction "D_K1") (pintype "open_collector"))
      (node (ref "D06") (pin "E1") (pinfunction "P$2_E1") (pintype "bidirectional"))
    )
    (net (code "529") (name "~{DB_03}") (class "Default")
      (node (ref "A06") (pin "H1") (pinfunction "P$2_H1") (pintype "bidirectional"))
      (node (ref "B02") (pin "L1") (pinfunction "E_L1") (pintype "open_collector"))
      (node (ref "D06") (pin "H1") (pinfunction "P$2_H1") (pintype "bidirectional"))
    )
    (net (code "530") (name "~{DB_04}") (class "Default")
      (node (ref "A06") (pin "J1") (pinfunction "P$2_J1") (pintype "bidirectional"))
      (node (ref "B02") (pin "R1") (pinfunction "D_R1") (pintype "open_collector"))
      (node (ref "D06") (pin "J1") (pinfunction "P$2_J1") (pintype "bidirectional"))
    )
    (net (code "531") (name "~{DB_05}") (class "Default")
      (node (ref "A06") (pin "L1") (pinfunction "P$2_L1") (pintype "bidirectional"))
      (node (ref "B02") (pin "S1") (pinfunction "E_S1") (pintype "open_collector"))
      (node (ref "D06") (pin "L1") (pinfunction "P$2_L1") (pintype "bidirectional"))
    )
    (net (code "532") (name "~{DB_06}") (class "Default")
      (node (ref "A06") (pin "M1") (pinfunction "P$2_M1") (pintype "bidirectional"))
      (node (ref "B02") (pin "H2") (pinfunction "D_H2") (pintype "open_collector"))
      (node (ref "D06") (pin "M1") (pinfunction "P$2_M1") (pintype "bidirectional"))
    )
    (net (code "533") (name "~{DB_07}") (class "Default")
      (node (ref "A06") (pin "P1") (pinfunction "P$2_P1") (pintype "bidirectional"))
      (node (ref "B02") (pin "J2") (pinfunction "E_J2") (pintype "open_collector"))
      (node (ref "D06") (pin "P1") (pinfunction "P$2_P1") (pintype "bidirectional"))
    )
    (net (code "534") (name "~{DB_08}") (class "Default")
      (node (ref "A06") (pin "S1") (pinfunction "P$2_S1") (pintype "bidirectional"))
      (node (ref "B02") (pin "N2") (pinfunction "D_N2") (pintype "open_collector"))
      (node (ref "D06") (pin "S1") (pinfunction "P$2_S1") (pintype "bidirectional"))
    )
    (net (code "535") (name "~{DB_09}") (class "Default")
      (node (ref "A06") (pin "D2") (pinfunction "P$2_D2") (pintype "bidirectional"))
      (node (ref "B02") (pin "P2") (pinfunction "E_P2") (pintype "open_collector"))
      (node (ref "D06") (pin "D2") (pinfunction "P$2_D2") (pintype "bidirectional"))
    )
    (net (code "536") (name "~{DB_10}") (class "Default")
      (node (ref "A06") (pin "E2") (pinfunction "P$2_E2") (pintype "bidirectional"))
      (node (ref "B02") (pin "U2") (pinfunction "D_U2") (pintype "open_collector"))
      (node (ref "D06") (pin "E2") (pinfunction "P$2_E2") (pintype "bidirectional"))
    )
    (net (code "537") (name "~{DB_11}") (class "Default")
      (node (ref "A06") (pin "H2") (pinfunction "P$2_H2") (pintype "bidirectional"))
      (node (ref "B02") (pin "V2") (pinfunction "E_V2") (pintype "open_collector"))
      (node (ref "D06") (pin "H2") (pinfunction "P$2_H2") (pintype "bidirectional"))
    )
    (net (code "538") (name "~{DF}") (class "Default")
      (node (ref "B05") (pin "A1") (pinfunction "A_A1") (pintype "input"))
      (node (ref "B12") (pin "J1") (pinfunction "IN3_J1") (pintype "input"))
      (node (ref "D11") (pin "P2") (pinfunction "1_P2") (pintype "output"))
    )
    (net (code "539") (name "~{DTB_00}") (class "Default")
      (node (ref "B02") (pin "A1") (pinfunction "A_A1") (pintype "input"))
      (node (ref "C09") (pin "F1") (pinfunction "0_F1") (pintype "output"))
    )
    (net (code "540") (name "~{DTB_01}") (class "Default")
      (node (ref "B02") (pin "B1") (pinfunction "B_B1") (pintype "input"))
      (node (ref "C09") (pin "J2") (pinfunction "0_J2") (pintype "output"))
    )
    (net (code "541") (name "~{DTB_02}") (class "Default")
      (node (ref "B02") (pin "F1") (pinfunction "A_F1") (pintype "input"))
      (node (ref "C09") (pin "M1") (pinfunction "0_M1") (pintype "output"))
    )
    (net (code "542") (name "~{DTB_03}") (class "Default")
      (node (ref "B02") (pin "H1") (pinfunction "B_H1") (pintype "input"))
      (node (ref "C09") (pin "R2") (pinfunction "0_R2") (pintype "output"))
    )
    (net (code "543") (name "~{DTB_04}") (class "Default")
      (node (ref "B02") (pin "M1") (pinfunction "A_M1") (pintype "input"))
      (node (ref "C09") (pin "U1") (pinfunction "0_U1") (pintype "output"))
    )
    (net (code "544") (name "~{DTB_05}") (class "Default")
      (node (ref "B02") (pin "N1") (pinfunction "B_N1") (pintype "input"))
      (node (ref "C09") (pin "V1") (pinfunction "0_V1") (pintype "output"))
    )
    (net (code "545") (name "~{DTB_06}") (class "Default")
      (node (ref "B02") (pin "D2") (pinfunction "A_D2") (pintype "input"))
      (node (ref "B09") (pin "F1") (pinfunction "0_F1") (pintype "output"))
    )
    (net (code "546") (name "~{DTB_07}") (class "Default")
      (node (ref "B02") (pin "E2") (pinfunction "B_E2") (pintype "input"))
      (node (ref "B09") (pin "V1") (pinfunction "0_V1") (pintype "output"))
    )
    (net (code "547") (name "~{DTB_08}") (class "Default")
      (node (ref "B02") (pin "K2") (pinfunction "A_K2") (pintype "input"))
      (node (ref "B09") (pin "M1") (pinfunction "0_M1") (pintype "output"))
    )
    (net (code "548") (name "~{DTB_09}") (class "Default")
      (node (ref "B02") (pin "L2") (pinfunction "B_L2") (pintype "input"))
      (node (ref "B09") (pin "R2") (pinfunction "0_R2") (pintype "output"))
    )
    (net (code "549") (name "~{DTB_10}") (class "Default")
      (node (ref "B02") (pin "R2") (pinfunction "A_R2") (pintype "input"))
      (node (ref "B09") (pin "U1") (pinfunction "0_U1") (pintype "output"))
    )
    (net (code "550") (name "~{DTB_11}") (class "Default")
      (node (ref "B02") (pin "S2") (pinfunction "B_S2") (pintype "input"))
      (node (ref "B09") (pin "J2") (pinfunction "0_J2") (pintype "output"))
    )
    (net (code "551") (name "~{DTF}") (class "Default")
      (node (ref "B04") (pin "L2") (pinfunction "B_L2") (pintype "input"))
      (node (ref "B12") (pin "C1") (pinfunction "IN3_C1") (pintype "input"))
      (node (ref "D11") (pin "V2") (pinfunction "1_V2") (pintype "output"))
    )
    (net (code "552") (name "~{DTSF}") (class "Default")
      (node (ref "C05") (pin "A1") (pinfunction "A1_A1") (pintype "output"))
    )
    (net (code "553") (name "~{EA_00}") (class "Default")
      (node (ref "A06") (pin "V2") (pinfunction "P$2_V2") (pintype "bidirectional"))
      (node (ref "B05") (pin "R1") (pinfunction "D_R1") (pintype "open_collector"))
      (node (ref "D06") (pin "V2") (pinfunction "P$2_V2") (pintype "bidirectional"))
    )
    (net (code "554") (name "~{EA_01}") (class "Default")
      (node (ref "A06") (pin "T2") (pinfunction "P$2_T2") (pintype "bidirectional"))
      (node (ref "B05") (pin "S1") (pinfunction "E_S1") (pintype "open_collector"))
      (node (ref "D06") (pin "T2") (pinfunction "P$2_T2") (pintype "bidirectional"))
    )
    (net (code "555") (name "~{EA_02}") (class "Default")
      (node (ref "A06") (pin "S2") (pinfunction "P$2_S2") (pintype "bidirectional"))
      (node (ref "B05") (pin "H2") (pinfunction "D_H2") (pintype "open_collector"))
      (node (ref "D06") (pin "S2") (pinfunction "P$2_S2") (pintype "bidirectional"))
    )
    (net (code "556") (name "~{EF}") (class "Default")
      (node (ref "A11") (pin "K1") (pinfunction "OUT_K1") (pintype "output"))
      (node (ref "B04") (pin "A1") (pinfunction "A_A1") (pintype "input"))
    )
    (net (code "557") (name "~{END}") (class "Default")
      (node (ref "A08") (pin "F1") (pinfunction "0_F1") (pintype "output"))
      (node (ref "A09") (pin "M2") (pinfunction "IN3_M2") (pintype "input"))
      (node (ref "B04") (pin "F1") (pinfunction "A_F1") (pintype "input"))
    )
    (net (code "558") (name "~{ENI}") (class "Default")
      (node (ref "B03") (pin "L2") (pinfunction "B_L2") (pintype "input"))
      (node (ref "C07") (pin "M1") (pinfunction "M1_M1") (pintype "output"))
    )
    (net (code "559") (name "~{FR_00}") (class "Default")
      (node (ref "B03") (pin "N1") (pinfunction "B_N1") (pintype "input"))
      (node (ref "B07") (pin "U1") (pinfunction "U1_U1") (pintype "output"))
      (node (ref "C12") (pin "K1") (pinfunction "IN1_K1") (pintype "input"))
      (node (ref "C12") (pin "P1") (pinfunction "IN1_P1") (pintype "input"))
    )
    (net (code "560") (name "~{FR_01}") (class "Default")
      (node (ref "A12") (pin "H2") (pinfunction "IN1_H2") (pintype "input"))
      (node (ref "B03") (pin "D2") (pinfunction "A_D2") (pintype "input"))
      (node (ref "B05") (pin "E2") (pinfunction "B_E2") (pintype "input"))
      (node (ref "B07") (pin "V1") (pinfunction "V1_V1") (pintype "output"))
    )
    (net (code "561") (name "~{FR_02}") (class "Default")
      (node (ref "B03") (pin "E2") (pinfunction "B_E2") (pintype "input"))
      (node (ref "C07") (pin "F1") (pinfunction "F1_F1") (pintype "output"))
    )
    (net (code "562") (name "~{FR_03}") (class "Default")
      (node (ref "B03") (pin "K2") (pinfunction "A_K2") (pintype "input"))
      (node (ref "B08") (pin "J2") (pinfunction "IN2_J2") (pintype "input"))
      (node (ref "C07") (pin "J2") (pinfunction "J2_J2") (pintype "output"))
    )
    (net (code "563") (name "~{IM_00}") (class "Default")
      (node (ref "A04") (pin "B1") (pinfunction "P$2_B1") (pintype "bidirectional"))
      (node (ref "B03") (pin "D1") (pinfunction "D_D1") (pintype "open_collector"))
      (node (ref "B04") (pin "D1") (pinfunction "D_D1") (pintype "open_collector"))
      (node (ref "D04") (pin "B1") (pinfunction "P$2_B1") (pintype "bidirectional"))
    )
    (net (code "564") (name "~{IM_01}") (class "Default")
      (node (ref "A04") (pin "D1") (pinfunction "P$2_D1") (pintype "bidirectional"))
      (node (ref "B03") (pin "E1") (pinfunction "E_E1") (pintype "open_collector"))
      (node (ref "B04") (pin "E1") (pinfunction "E_E1") (pintype "open_collector"))
      (node (ref "D04") (pin "D1") (pinfunction "P$2_D1") (pintype "bidirectional"))
    )
    (net (code "565") (name "~{IM_02}") (class "Default")
      (node (ref "A04") (pin "E1") (pinfunction "P$2_E1") (pintype "bidirectional"))
      (node (ref "B03") (pin "K1") (pinfunction "D_K1") (pintype "open_collector"))
      (node (ref "B04") (pin "K1") (pinfunction "D_K1") (pintype "open_collector"))
      (node (ref "D04") (pin "E1") (pinfunction "P$2_E1") (pintype "bidirectional"))
    )
    (net (code "566") (name "~{IM_03}") (class "Default")
      (node (ref "A04") (pin "H1") (pinfunction "P$2_H1") (pintype "bidirectional"))
      (node (ref "B03") (pin "L1") (pinfunction "E_L1") (pintype "open_collector"))
      (node (ref "B04") (pin "L1") (pinfunction "E_L1") (pintype "open_collector"))
      (node (ref "D04") (pin "H1") (pinfunction "P$2_H1") (pintype "bidirectional"))
    )
    (net (code "567") (name "~{IM_04}") (class "Default")
      (node (ref "A04") (pin "J1") (pinfunction "P$2_J1") (pintype "bidirectional"))
      (node (ref "B03") (pin "R1") (pinfunction "D_R1") (pintype "open_collector"))
      (node (ref "B04") (pin "R1") (pinfunction "D_R1") (pintype "open_collector"))
      (node (ref "D04") (pin "J1") (pinfunction "P$2_J1") (pintype "bidirectional"))
    )
    (net (code "568") (name "~{IM_05}") (class "Default")
      (node (ref "A04") (pin "L1") (pinfunction "P$2_L1") (pintype "bidirectional"))
      (node (ref "B03") (pin "S1") (pinfunction "E_S1") (pintype "open_collector"))
      (node (ref "B04") (pin "S1") (pinfunction "E_S1") (pintype "open_collector"))
      (node (ref "D04") (pin "L1") (pinfunction "P$2_L1") (pintype "bidirectional"))
    )
    (net (code "569") (name "~{IM_06}") (class "Default")
      (node (ref "A04") (pin "M1") (pinfunction "P$2_M1") (pintype "bidirectional"))
      (node (ref "B03") (pin "H2") (pinfunction "D_H2") (pintype "open_collector"))
      (node (ref "B04") (pin "H2") (pinfunction "D_H2") (pintype "open_collector"))
      (node (ref "D04") (pin "M1") (pinfunction "P$2_M1") (pintype "bidirectional"))
    )
    (net (code "570") (name "~{IM_07}") (class "Default")
      (node (ref "A04") (pin "P1") (pinfunction "P$2_P1") (pintype "bidirectional"))
      (node (ref "B03") (pin "J2") (pinfunction "E_J2") (pintype "open_collector"))
      (node (ref "B04") (pin "J2") (pinfunction "E_J2") (pintype "open_collector"))
      (node (ref "D04") (pin "P1") (pinfunction "P$2_P1") (pintype "bidirectional"))
    )
    (net (code "571") (name "~{IM_08}") (class "Default")
      (node (ref "A04") (pin "S1") (pinfunction "P$2_S1") (pintype "bidirectional"))
      (node (ref "B03") (pin "N2") (pinfunction "D_N2") (pintype "open_collector"))
      (node (ref "B04") (pin "N2") (pinfunction "D_N2") (pintype "open_collector"))
      (node (ref "D04") (pin "S1") (pinfunction "P$2_S1") (pintype "bidirectional"))
    )
    (net (code "572") (name "~{IM_09}") (class "Default")
      (node (ref "A04") (pin "D2") (pinfunction "P$2_D2") (pintype "bidirectional"))
      (node (ref "B03") (pin "P2") (pinfunction "E_P2") (pintype "open_collector"))
      (node (ref "D04") (pin "D2") (pinfunction "P$2_D2") (pintype "bidirectional"))
    )
    (net (code "573") (name "~{IM_10}") (class "Default")
      (node (ref "A04") (pin "E2") (pinfunction "P$2_E2") (pintype "bidirectional"))
      (node (ref "D04") (pin "E2") (pinfunction "P$2_E2") (pintype "bidirectional"))
    )
    (net (code "574") (name "~{IM_11}") (class "Default")
      (node (ref "A04") (pin "H2") (pinfunction "P$2_H2") (pintype "bidirectional"))
      (node (ref "B04") (pin "P2") (pinfunction "E_P2") (pintype "open_collector"))
      (node (ref "D04") (pin "H2") (pinfunction "P$2_H2") (pintype "bidirectional"))
    )
    (net (code "575") (name "~{INT_RQ}") (class "Default")
      (node (ref "A12") (pin "K1") (pinfunction "OUT_K1") (pintype "output"))
      (node (ref "B05") (pin "B1") (pinfunction "B_B1") (pintype "input"))
    )
    (net (code "576") (name "~{LDMF}") (class "Default")
      (node (ref "B08") (pin "P2") (pinfunction "IN1_P2") (pintype "input"))
      (node (ref "C05") (pin "E1") (pinfunction "E1_E1") (pintype "output"))
    )
    (net (code "577") (name "~{LPB_00}") (class "Default")
      (node (ref "D08") (pin "F1") (pinfunction "F1_F1") (pintype "output"))
      (node (ref "D10") (pin "M1") (pinfunction "IN1_M1") (pintype "input"))
    )
    (net (code "578") (name "~{LPB_01}") (class "Default")
      (node (ref "D08") (pin "M1") (pinfunction "M1_M1") (pintype "output"))
      (node (ref "D10") (pin "N1") (pinfunction "IN2_N1") (pintype "input"))
    )
    (net (code "579") (name "~{LPB_02}") (class "Default")
      (node (ref "D08") (pin "U1") (pinfunction "U1_U1") (pintype "output"))
      (node (ref "D10") (pin "P1") (pinfunction "IN3_P1") (pintype "input"))
    )
    (net (code "580") (name "~{LPB_03}") (class "Default")
      (node (ref "D08") (pin "J2") (pinfunction "J2_J2") (pintype "output"))
      (node (ref "D10") (pin "R1") (pinfunction "IN4_R1") (pintype "input"))
    )
    (net (code "581") (name "~{LPB_04}") (class "Default")
      (node (ref "D08") (pin "R2") (pinfunction "R2_R2") (pintype "output"))
      (node (ref "D10") (pin "R2") (pinfunction "IN5_R2") (pintype "input"))
    )
    (net (code "582") (name "~{LPB_05}") (class "Default")
      (node (ref "D08") (pin "V1") (pinfunction "V1_V1") (pintype "output"))
      (node (ref "D10") (pin "S2") (pinfunction "IN6_S2") (pintype "input"))
      (node (ref "D10") (pin "T2") (pinfunction "IN7_T2") (pintype "input"))
      (node (ref "D10") (pin "U2") (pinfunction "IN8_U2") (pintype "input"))
    )
    (net (code "583") (name "~{M-STOP}") (class "Default")
      (node (ref "A11") (pin "S1") (pinfunction "OUT_S1") (pintype "output"))
      (node (ref "B14") (pin "D1") (pinfunction "S_D1") (pintype "input"))
      (node (ref "C07") (pin "K2") (pinfunction "K2_K2") (pintype "input"))
      (node (ref "D14") (pin "L1") (pinfunction "M1_L1") (pintype "input"))
    )
    (net (code "584") (name "~{MB_TO_DTB}") (class "Default")
      (node (ref "D12") (pin "F1") (pinfunction "IN1_F1") (pintype "input"))
      (node (ref "D12") (pin "H1") (pinfunction "IN2_H1") (pintype "input"))
      (node (ref "D12") (pin "J1") (pinfunction "IN3_J1") (pintype "input"))
      (node (ref "D12") (pin "K1") (pinfunction "IN4_K1") (pintype "input"))
      (node (ref "D12") (pin "S1") (pinfunction "OUT_S1") (pintype "output"))
    )
    (net (code "585") (name "~{MC00}") (class "Default")
      (node (ref "A10") (pin "R1") (pinfunction "IN2_R1") (pintype "input"))
      (node (ref "B11") (pin "T2") (pinfunction "IN1_T2") (pintype "input"))
      (node (ref "B13") (pin "F1") (pinfunction "0_F1") (pintype "output"))
    )
    (net (code "586") (name "~{MC01}") (class "Default")
      (node (ref "B11") (pin "P1") (pinfunction "IN1_P1") (pintype "input"))
      (node (ref "B13") (pin "J2") (pinfunction "0_J2") (pintype "output"))
      (node (ref "C11") (pin "B1") (pinfunction "IN2_B1") (pintype "input"))
      (node (ref "D10") (pin "E2") (pinfunction "IN6_E2") (pintype "input"))
    )
    (net (code "587") (name "~{MC02}") (class "Default")
      (node (ref "B13") (pin "C1") (pinfunction "D_C1") (pintype "input"))
      (node (ref "B13") (pin "M1") (pinfunction "0_M1") (pintype "output"))
      (node (ref "D10") (pin "F2") (pinfunction "IN7_F2") (pintype "input"))
    )
    (net (code "588") (name "~{MF00}") (class "Default")
      (node (ref "B04") (pin "D2") (pinfunction "A_D2") (pintype "input"))
      (node (ref "B05") (pin "M1") (pinfunction "A_M1") (pintype "input"))
      (node (ref "D11") (pin "F1") (pinfunction "0_F1") (pintype "output"))
    )
    (net (code "589") (name "~{MF01}") (class "Default")
      (node (ref "B04") (pin "E2") (pinfunction "B_E2") (pintype "input"))
      (node (ref "B05") (pin "N1") (pinfunction "B_N1") (pintype "input"))
      (node (ref "D11") (pin "J2") (pinfunction "0_J2") (pintype "output"))
    )
    (net (code "590") (name "~{MF02}") (class "Default")
      (node (ref "B04") (pin "K2") (pinfunction "A_K2") (pintype "input"))
      (node (ref "B05") (pin "D2") (pinfunction "A_D2") (pintype "input"))
      (node (ref "D11") (pin "M1") (pinfunction "0_M1") (pintype "output"))
    )
    (net (code "591") (name "~{MKTK}") (class "Default")
      (node (ref "A08") (pin "P2") (pinfunction "1_P2") (pintype "output"))
      (node (ref "A09") (pin "K2") (pinfunction "IN1_K2") (pintype "input"))
      (node (ref "B04") (pin "B1") (pinfunction "B_B1") (pintype "input"))
    )
    (net (code "592") (name "~{MKT}") (class "Default")
      (node (ref "B10") (pin "R1") (pinfunction "IN4_R1") (pintype "input"))
      (node (ref "B13") (pin "T2") (pinfunction "D_T2") (pintype "input"))
      (node (ref "B13") (pin "V1") (pinfunction "0_V1") (pintype "output"))
      (node (ref "C14") (pin "N1") (pinfunction "C_N1") (pintype "input"))
      (node (ref "D10") (pin "H2") (pinfunction "IN8_H2") (pintype "input"))
    )
    (net (code "593") (name "~{MK_BLK_END}") (class "Default")
      (node (ref "A09") (pin "C1") (pinfunction "IN3_C1") (pintype "input"))
      (node (ref "CD18") (pin "BV1") (pinfunction "BV1_BV1") (pintype "output"))
    )
    (net (code "594") (name "~{MK_BLK_MK}") (class "Default")
      (node (ref "CD18") (pin "AD2") (pinfunction "AD2_AD2") (pintype "output"))
    )
    (net (code "595") (name "~{MK_BLK_START}") (class "Default")
      (node (ref "A09") (pin "A1") (pinfunction "IN1_A1") (pintype "input"))
      (node (ref "CD18") (pin "AF1") (pinfunction "AF1_AF1") (pintype "output"))
    )
    (net (code "596") (name "~{MK_BLK_SYNC}") (class "Default")
      (node (ref "CD18") (pin "BT2") (pinfunction "BT2_BT2") (pintype "output"))
    )
    (net (code "597") (name "~{MK_DATA_SYNC}") (class "Default")
      (node (ref "CD18") (pin "AJ1") (pinfunction "AJ1_AJ1") (pintype "output"))
    )
    (net (code "598") (name "~{MK_DATA}") (class "Default")
      (node (ref "A09") (pin "B1") (pinfunction "IN2_B1") (pintype "input"))
      (node (ref "CD18") (pin "AU2") (pinfunction "AU2_AU2") (pintype "output"))
    )
    (net (code "599") (name "~{MK_END}") (class "Default")
      (node (ref "A09") (pin "D1") (pinfunction "IN4_D1") (pintype "input"))
      (node (ref "CD18") (pin "AH2") (pinfunction "AH2_AH2") (pintype "output"))
    )
    (net (code "600") (name "~{MOVE}") (class "Default")
      (node (ref "D07") (pin "D1") (pinfunction "~{O0}_D1") (pintype "output"))
    )
    (net (code "601") (name "~{MR00}") (class "Default")
      (node (ref "B03") (pin "H1") (pinfunction "B_H1") (pintype "input"))
      (node (ref "B07") (pin "R2") (pinfunction "R2_R2") (pintype "output"))
    )
    (net (code "602") (name "~{MR01}") (class "Default")
      (node (ref "B03") (pin "M1") (pinfunction "A_M1") (pintype "input"))
      (node (ref "B14") (pin "C1") (pinfunction "D_C1") (pintype "input"))
      (node (ref "C07") (pin "R2") (pinfunction "R2_R2") (pintype "output"))
    )
    (net (code "603") (name "~{PAR}") (class "Default")
      (node (ref "A08") (pin "S1") (pinfunction "1_S1") (pintype "output"))
      (node (ref "A12") (pin "E1") (pinfunction "IN2_E1") (pintype "input"))
      (node (ref "B04") (pin "M1") (pinfunction "A_M1") (pintype "input"))
    )
    (net (code "604") (name "~{PC+ES}") (class "Default")
      (node (ref "A11") (pin "J2") (pinfunction "OUT_J2") (pintype "output"))
      (node (ref "B11") (pin "R2") (pinfunction "IN3_R2") (pintype "input"))
    )
    (net (code "605") (name "~{PWR_CLR}") (class "Default")
      (node (ref "A10") (pin "H2") (pinfunction "IN1_H2") (pintype "input"))
      (node (ref "A10") (pin "M2") (pinfunction "IN2_M2") (pintype "input"))
      (node (ref "A12") (pin "A1") (pinfunction "IN1_A1") (pintype "input"))
      (node (ref "A23") (pin "M1") (pinfunction "A_M1") (pintype "input"))
      (node (ref "B08") (pin "U2") (pinfunction "IN2_U2") (pintype "input"))
      (node (ref "C05") (pin "K1") (pinfunction "OUT_K1") (pintype "output"))
      (node (ref "C06") (pin "P2") (pinfunction "IN_P2") (pintype "input"))
      (node (ref "C11") (pin "U2") (pinfunction "IN2_U2") (pintype "input"))
      (node (ref "C14") (pin "R1") (pinfunction "S_R1") (pintype "input"))
      (node (ref "D11") (pin "A1") (pinfunction "R_A1") (pintype "input"))
    )
    (net (code "606") (name "~{RDD_00}") (class "Default")
      (node (ref "A21") (pin "V2") (pinfunction "V2_V2") (pintype "output"))
    )
    (net (code "607") (name "~{RDD_01}") (class "Default")
      (node (ref "B20") (pin "V2") (pinfunction "V2_V2") (pintype "output"))
    )
    (net (code "608") (name "~{RDD_02}") (class "Default")
      (node (ref "A20") (pin "V2") (pinfunction "V2_V2") (pintype "output"))
    )
    (net (code "609") (name "~{RDMK}") (class "Default")
      (node (ref "B18") (pin "V2") (pinfunction "V2_V2") (pintype "output"))
    )
    (net (code "610") (name "~{READ_ALL}") (class "Default")
      (node (ref "C11") (pin "M1") (pinfunction "IN2_M1") (pintype "input"))
      (node (ref "D07") (pin "N1") (pinfunction "~{O3}_N1") (pintype "output"))
    )
    (net (code "611") (name "~{READ_DATA}") (class "Default")
      (node (ref "B08") (pin "L2") (pinfunction "IN1_L2") (pintype "input"))
      (node (ref "B11") (pin "J2") (pinfunction "IN1_J2") (pintype "input"))
      (node (ref "D07") (pin "J1") (pinfunction "~{O2}_J1") (pintype "output"))
    )
    (net (code "612") (name "~{RSTA}") (class "Default")
      (node (ref "B03") (pin "C1") (pinfunction "C_C1") (pintype "input"))
      (node (ref "B03") (pin "F2") (pinfunction "C_F2") (pintype "input"))
      (node (ref "B03") (pin "J1") (pinfunction "C_J1") (pintype "input"))
      (node (ref "B03") (pin "M2") (pinfunction "C_M2") (pintype "input"))
      (node (ref "B03") (pin "P1") (pinfunction "C_P1") (pintype "input"))
      (node (ref "C04") (pin "A1") (pinfunction "A1_A1") (pintype "output"))
    )
    (net (code "613") (name "~{RSTB}") (class "Default")
      (node (ref "B04") (pin "C1") (pinfunction "C_C1") (pintype "input"))
      (node (ref "B04") (pin "F2") (pinfunction "C_F2") (pintype "input"))
      (node (ref "B04") (pin "J1") (pinfunction "C_J1") (pintype "input"))
      (node (ref "B04") (pin "M2") (pinfunction "C_M2") (pintype "input"))
      (node (ref "B04") (pin "P1") (pinfunction "C_P1") (pintype "input"))
      (node (ref "C05") (pin "C1") (pinfunction "C1_C1") (pintype "output"))
    )
    (net (code "614") (name "~{SEARCH}") (class "Default")
      (node (ref "B05") (pin "K2") (pinfunction "A_K2") (pintype "input"))
      (node (ref "B11") (pin "K2") (pinfunction "IN2_K2") (pintype "input"))
      (node (ref "D07") (pin "E1") (pinfunction "~{O1}_E1") (pintype "output"))
    )
    (net (code "615") (name "~{SEL}") (class "Default")
      (node (ref "A08") (pin "J2") (pinfunction "0_J2") (pintype "output"))
      (node (ref "A09") (pin "N2") (pinfunction "IN4_N2") (pintype "input"))
      (node (ref "B04") (pin "H1") (pinfunction "B_H1") (pintype "input"))
    )
    (net (code "616") (name "~{SE}") (class "Default")
      (node (ref "A09") (pin "H1") (pinfunction "IN2_H1") (pintype "input"))
      (node (ref "D07") (pin "L1") (pinfunction "~{O7}_L1") (pintype "output"))
    )
    (net (code "617") (name "~{SKP_RQ}") (class "Default")
      (node (ref "A12") (pin "S1") (pinfunction "OUT_S1") (pintype "output"))
      (node (ref "B05") (pin "F1") (pinfunction "A_F1") (pintype "input"))
    )
    (net (code "618") (name "~{SP_DY}") (class "Default")
      (node (ref "C14") (pin "M2") (pinfunction "D_M2") (pintype "input"))
      (node (ref "D14") (pin "F2") (pinfunction "F2_F2") (pintype "output"))
    )
    (net (code "619") (name "~{ST_BLK_MK}") (class "Default")
      (node (ref "A09") (pin "D2") (pinfunction "IN1_D2") (pintype "input"))
      (node (ref "A09") (pin "M1") (pinfunction "IN1_M1") (pintype "input"))
      (node (ref "C13") (pin "F2") (pinfunction "OUT_F2") (pintype "output"))
    )
    (net (code "620") (name "~{ST_CK_0P}") (class "Default")
      (node (ref "C13") (pin "A1") (pinfunction "IN_A1") (pintype "input"))
      (node (ref "D17") (pin "L2") (pinfunction "F2_L2") (pintype "output"))
    )
    (net (code "621") (name "~{ST_CK}") (class "Default")
      (node (ref "C13") (pin "K1") (pinfunction "OUT_K1") (pintype "output"))
      (node (ref "C16") (pin "E2") (pinfunction "IN2_E2") (pintype "input"))
    )
    (net (code "622") (name "~{ST_DATA}") (class "Default")
      (node (ref "C13") (pin "J2") (pinfunction "OUT_J2") (pintype "output"))
    )
    (net (code "623") (name "~{ST_FINAL}") (class "Default")
      (node (ref "C11") (pin "M2") (pinfunction "IN2_M2") (pintype "input"))
      (node (ref "C13") (pin "M1") (pinfunction "OUT_M1") (pintype "output"))
      (node (ref "C16") (pin "F2") (pinfunction "IN3_F2") (pintype "input"))
    )
    (net (code "624") (name "~{ST_IDLE}") (class "Default")
      (node (ref "A09") (pin "E2") (pinfunction "IN2_E2") (pintype "input"))
      (node (ref "A09") (pin "N1") (pinfunction "IN2_N1") (pintype "input"))
      (node (ref "C13") (pin "L2") (pinfunction "OUT_L2") (pintype "output"))
    )
    (net (code "625") (name "~{ST_REV_CK}") (class "Default")
      (node (ref "C13") (pin "E1") (pinfunction "OUT_E1") (pintype "output"))
    )
    (net (code "626") (name "~{SWTM}") (class "Default")
      (node (ref "B06") (pin "R2") (pinfunction "OUT_R2") (pintype "output"))
    )
    (net (code "627") (name "~{SYNC-P}") (class "Default")
      (node (ref "B10") (pin "J2") (pinfunction "OUT_J2") (pintype "output"))
      (node (ref "B13") (pin "A1") (pinfunction "R_A1") (pintype "input"))
      (node (ref "B13") (pin "K2") (pinfunction "R_K2") (pintype "input"))
    )
    (net (code "628") (name "~{SYNC}") (class "Default")
      (node (ref "CD18") (pin "BM2") (pinfunction "BM2_BM2") (pintype "output"))
    )
    (net (code "629") (name "~{TIM}") (class "Default")
      (node (ref "A08") (pin "M1") (pinfunction "0_M1") (pintype "output"))
      (node (ref "A09") (pin "L2") (pinfunction "IN2_L2") (pintype "input"))
      (node (ref "B04") (pin "N1") (pinfunction "B_N1") (pintype "input"))
    )
    (net (code "630") (name "~{TM_EN}") (class "Default")
      (node (ref "C12") (pin "C1") (pinfunction "IN3_C1") (pintype "input"))
      (node (ref "C12") (pin "K2") (pinfunction "IN2_K2") (pintype "input"))
      (node (ref "C13") (pin "P1") (pinfunction "OUT_P1") (pintype "output"))
      (node (ref "D15") (pin "J2") (pinfunction "J2_J2") (pintype "input"))
      (node (ref "D15") (pin "K2") (pinfunction "K2_K2") (pintype "input"))
    )
    (net (code "631") (name "~{TP00_A}") (class "Default")
      (node (ref "A15") (pin "M1") (pinfunction "IN1_M1") (pintype "input"))
      (node (ref "A15") (pin "N1") (pinfunction "IN2_N1") (pintype "input"))
      (node (ref "A15") (pin "P1") (pinfunction "IN3_P1") (pintype "input"))
      (node (ref "A15") (pin "R1") (pinfunction "IN4_R1") (pintype "input"))
      (node (ref "A16") (pin "L2") (pinfunction "F2_L2") (pintype "output"))
    )
    (net (code "632") (name "~{TP0_XTLK_DY}") (class "Default")
      (node (ref "A11") (pin "R2") (pinfunction "OUT_R2") (pintype "output"))
      (node (ref "A16") (pin "J2") (pinfunction "J2_J2") (pintype "input"))
      (node (ref "A16") (pin "K2") (pinfunction "K2_K2") (pintype "input"))
    )
    (net (code "633") (name "~{TP00}") (class "Default")
      (node (ref "A15") (pin "E1") (pinfunction "OUT_E1") (pintype "output"))
      (node (ref "A15") (pin "F1") (pinfunction "IN1_F1") (pintype "input"))
      (node (ref "A15") (pin "H1") (pinfunction "IN2_H1") (pintype "input"))
      (node (ref "A15") (pin "J1") (pinfunction "IN3_J1") (pintype "input"))
      (node (ref "A15") (pin "K1") (pinfunction "IN4_K1") (pintype "input"))
      (node (ref "CD18") (pin "AN1") (pinfunction "AN1_AN1") (pintype "input"))
    )
    (net (code "634") (name "~{TP01_A}") (class "Default")
      (node (ref "A15") (pin "R2") (pinfunction "IN1_R2") (pintype "input"))
      (node (ref "A15") (pin "S2") (pinfunction "IN2_S2") (pintype "input"))
      (node (ref "A15") (pin "T2") (pinfunction "IN3_T2") (pintype "input"))
      (node (ref "A15") (pin "U2") (pinfunction "IN4_U2") (pintype "input"))
      (node (ref "B16") (pin "L2") (pinfunction "F2_L2") (pintype "output"))
    )
    (net (code "635") (name "~{TP1_XTLK_DY}") (class "Default")
      (node (ref "A11") (pin "V2") (pinfunction "OUT_V2") (pintype "output"))
      (node (ref "B16") (pin "H2") (pinfunction "H2_H2") (pintype "input"))
      (node (ref "B16") (pin "J2") (pinfunction "J2_J2") (pintype "input"))
    )
    (net (code "636") (name "~{TP01}") (class "Default")
      (node (ref "A15") (pin "J2") (pinfunction "OUT_J2") (pintype "output"))
      (node (ref "A15") (pin "K2") (pinfunction "IN1_K2") (pintype "input"))
      (node (ref "A15") (pin "L2") (pinfunction "IN2_L2") (pintype "input"))
      (node (ref "A15") (pin "M2") (pinfunction "IN3_M2") (pintype "input"))
      (node (ref "A15") (pin "N2") (pinfunction "IN4_N2") (pintype "input"))
    )
    (net (code "637") (name "~{TS03}") (class "Default")
      (node (ref "C04") (pin "K1") (pinfunction "OUT_K1") (pintype "output"))
      (node (ref "D17") (pin "H2") (pinfunction "H2_H2") (pintype "input"))
      (node (ref "D17") (pin "J2") (pinfunction "J2_J2") (pintype "input"))
      (node (ref "D17") (pin "K2") (pinfunction "K2_K2") (pintype "input"))
    )
    (net (code "638") (name "~{T_00}") (class "Default")
      (node (ref "A24") (pin "V2") (pinfunction "P$2_V2") (pintype "bidirectional"))
      (node (ref "B22") (pin "V2") (pinfunction "E_V2") (pintype "output"))
      (node (ref "B23") (pin "V2") (pinfunction "P$1_V2") (pintype "passive"))
    )
    (net (code "639") (name "~{T_01}") (class "Default")
      (node (ref "A23") (pin "S1") (pinfunction "E_S1") (pintype "output"))
      (node (ref "A24") (pin "M2") (pinfunction "P$2_M2") (pintype "bidirectional"))
      (node (ref "B23") (pin "M2") (pinfunction "P$1_M2") (pintype "passive"))
    )
    (net (code "640") (name "~{T_02}") (class "Default")
      (node (ref "A23") (pin "H2") (pinfunction "D_H2") (pintype "output"))
      (node (ref "A24") (pin "N2") (pinfunction "P$2_N2") (pintype "bidirectional"))
      (node (ref "B23") (pin "N2") (pinfunction "P$1_N2") (pintype "passive"))
    )
    (net (code "641") (name "~{T_03}") (class "Default")
      (node (ref "A23") (pin "J2") (pinfunction "E_J2") (pintype "output"))
      (node (ref "A24") (pin "P2") (pinfunction "P$2_P2") (pintype "bidirectional"))
      (node (ref "B23") (pin "P2") (pinfunction "P$1_P2") (pintype "passive"))
    )
    (net (code "642") (name "~{T_04}") (class "Default")
      (node (ref "A23") (pin "N2") (pinfunction "D_N2") (pintype "output"))
      (node (ref "A24") (pin "R2") (pinfunction "P$2_R2") (pintype "bidirectional"))
      (node (ref "B23") (pin "R2") (pinfunction "P$1_R2") (pintype "passive"))
    )
    (net (code "643") (name "~{T_05}") (class "Default")
      (node (ref "A23") (pin "P2") (pinfunction "E_P2") (pintype "output"))
      (node (ref "A24") (pin "S2") (pinfunction "P$2_S2") (pintype "bidirectional"))
      (node (ref "B23") (pin "S2") (pinfunction "P$1_S2") (pintype "passive"))
    )
    (net (code "644") (name "~{T_06}") (class "Default")
      (node (ref "A23") (pin "U2") (pinfunction "D_U2") (pintype "output"))
      (node (ref "A24") (pin "T2") (pinfunction "P$2_T2") (pintype "bidirectional"))
      (node (ref "B23") (pin "T2") (pinfunction "P$1_T2") (pintype "passive"))
    )
    (net (code "645") (name "~{T_07}") (class "Default")
      (node (ref "A23") (pin "V2") (pinfunction "E_V2") (pintype "output"))
      (node (ref "A24") (pin "U2") (pinfunction "P$2_U2") (pintype "bidirectional"))
      (node (ref "B23") (pin "U2") (pinfunction "P$1_U2") (pintype "passive"))
    )
    (net (code "646") (name "~{T_FWD}") (class "Default")
      (node (ref "A23") (pin "K1") (pinfunction "D_K1") (pintype "output"))
      (node (ref "A24") (pin "E2") (pinfunction "P$2_E2") (pintype "bidirectional"))
      (node (ref "B23") (pin "H2") (pinfunction "P$1_H2") (pintype "passive"))
    )
    (net (code "647") (name "~{T_GO}") (class "Default")
      (node (ref "A23") (pin "D1") (pinfunction "D_D1") (pintype "output"))
      (node (ref "A24") (pin "C2") (pinfunction "P$2_C2") (pintype "bidirectional"))
      (node (ref "B23") (pin "D2") (pinfunction "P$1_D2") (pintype "passive"))
    )
    (net (code "648") (name "~{T_PWR_CLR}") (class "Default")
      (node (ref "A23") (pin "R1") (pinfunction "D_R1") (pintype "output"))
      (node (ref "A24") (pin "H2") (pinfunction "P$2_H2") (pintype "bidirectional"))
      (node (ref "B23") (pin "K2") (pinfunction "P$1_K2") (pintype "passive"))
    )
    (net (code "649") (name "~{T_REV}") (class "Default")
      (node (ref "A23") (pin "L1") (pinfunction "E_L1") (pintype "output"))
      (node (ref "A24") (pin "F2") (pinfunction "P$2_F2") (pintype "bidirectional"))
      (node (ref "B23") (pin "J2") (pinfunction "P$1_J2") (pintype "passive"))
    )
    (net (code "650") (name "~{T_SINGLE_UNIT}") (class "Default")
      (node (ref "A24") (pin "K2") (pinfunction "P$2_K2") (pintype "bidirectional"))
      (node (ref "B21") (pin "T2") (pinfunction "IN_T2") (pintype "input"))
    )
    (net (code "651") (name "~{T_STOP}") (class "Default")
      (node (ref "A23") (pin "E1") (pinfunction "E_E1") (pintype "output"))
      (node (ref "A24") (pin "D2") (pinfunction "P$2_D2") (pintype "bidirectional"))
      (node (ref "B23") (pin "E2") (pinfunction "P$1_E2") (pintype "passive"))
    )
    (net (code "652") (name "~{T_TRK}") (class "Default")
      (node (ref "A18") (pin "V2") (pinfunction "V2_V2") (pintype "output"))
      (node (ref "B15") (pin "E1") (pinfunction "IN2_E1") (pintype "input"))
    )
    (net (code "653") (name "~{T_WRITE_OK}") (class "Default")
      (node (ref "A22") (pin "H2") (pinfunction "H2_H2") (pintype "input"))
      (node (ref "A24") (pin "L2") (pinfunction "P$2_L2") (pintype "bidirectional"))
      (node (ref "B23") (pin "L2") (pinfunction "P$1_L2") (pintype "passive"))
    )
    (net (code "654") (name "~{U+M_DY}") (class "Default")
      (node (ref "C12") (pin "A1") (pinfunction "IN1_A1") (pintype "input"))
      (node (ref "D14") (pin "E2") (pinfunction "F2_E2") (pintype "output"))
    )
    (net (code "655") (name "~{USR_00}") (class "Default")
      (node (ref "B03") (pin "A1") (pinfunction "A_A1") (pintype "input"))
      (node (ref "B07") (pin "F1") (pinfunction "F1_F1") (pintype "output"))
    )
    (net (code "656") (name "~{USR_01}") (class "Default")
      (node (ref "B03") (pin "B1") (pinfunction "B_B1") (pintype "input"))
      (node (ref "B07") (pin "J2") (pinfunction "J2_J2") (pintype "output"))
    )
    (net (code "657") (name "~{USR_02}") (class "Default")
      (node (ref "B03") (pin "F1") (pinfunction "A_F1") (pintype "input"))
      (node (ref "B07") (pin "M1") (pinfunction "M1_M1") (pintype "output"))
    )
    (net (code "658") (name "~{UTS}") (class "Default")
      (node (ref "C12") (pin "L2") (pinfunction "IN3_L2") (pintype "input"))
      (node (ref "C14") (pin "P2") (pinfunction "1_P2") (pintype "output"))
      (node (ref "C15") (pin "P2") (pinfunction "IN1_P2") (pintype "input"))
      (node (ref "C16") (pin "A1") (pinfunction "IN1_A1") (pintype "input"))
      (node (ref "C16") (pin "B1") (pinfunction "IN2_B1") (pintype "input"))
      (node (ref "C16") (pin "C1") (pinfunction "IN3_C1") (pintype "input"))
      (node (ref "C16") (pin "D1") (pinfunction "IN4_D1") (pintype "input"))
      (node (ref "C16") (pin "F1") (pinfunction "IN1_F1") (pintype "input"))
      (node (ref "C16") (pin "H1") (pinfunction "IN2_H1") (pintype "input"))
      (node (ref "C16") (pin "J1") (pinfunction "IN3_J1") (pintype "input"))
      (node (ref "C16") (pin "K1") (pinfunction "IN4_K1") (pintype "input"))
    )
    (net (code "659") (name "~{W-INH}") (class "Default")
      (node (ref "A08") (pin "V2") (pinfunction "1_V2") (pintype "output"))
      (node (ref "B11") (pin "L1") (pinfunction "IN2_L1") (pintype "input"))
      (node (ref "B12") (pin "H1") (pinfunction "IN2_H1") (pintype "input"))
    )
    (net (code "660") (name "~{WB00}") (class "Default")
      (node (ref "A21") (pin "P2") (pinfunction "P2_P2") (pintype "input"))
      (node (ref "B18") (pin "P2") (pinfunction "P2_P2") (pintype "input"))
      (node (ref "C10") (pin "D1") (pinfunction "IN2B_D1") (pintype "input"))
      (node (ref "C14") (pin "E1") (pinfunction "1_E1") (pintype "output"))
    )
    (net (code "661") (name "~{WB01}") (class "Default")
      (node (ref "B20") (pin "P2") (pinfunction "P2_P2") (pintype "input"))
      (node (ref "C10") (pin "K1") (pinfunction "IN2B_K1") (pintype "input"))
      (node (ref "C14") (pin "H2") (pinfunction "1_H2") (pintype "output"))
    )
    (net (code "662") (name "~{WB02}") (class "Default")
      (node (ref "A20") (pin "P2") (pinfunction "P2_P2") (pintype "input"))
      (node (ref "C10") (pin "R1") (pinfunction "IN2B_R1") (pintype "input"))
      (node (ref "C14") (pin "L1") (pinfunction "1_L1") (pintype "output"))
    )
    (net (code "663") (name "~{WC0}") (class "Default")
      (node (ref "C06") (pin "N2") (pinfunction "OUT_N2") (pintype "output"))
      (node (ref "D11") (pin "R1") (pinfunction "S_R1") (pintype "input"))
    )
    (net (code "664") (name "~{WC}") (class "Default")
      (node (ref "B12") (pin "F2") (pinfunction "IN3_F2") (pintype "input"))
      (node (ref "C12") (pin "T2") (pinfunction "IN1_T2") (pintype "input"))
      (node (ref "D11") (pin "M2") (pinfunction "D_M2") (pintype "input"))
      (node (ref "D11") (pin "U1") (pinfunction "0_U1") (pintype "output"))
    )
    (net (code "665") (name "~{WRITE_ALL}") (class "Default")
      (node (ref "D07") (pin "M1") (pinfunction "~{O5}_M1") (pintype "output"))
    )
    (net (code "666") (name "~{WRITE_DATA}") (class "Default")
      (node (ref "B08") (pin "M2") (pinfunction "IN2_M2") (pintype "input"))
      (node (ref "D07") (pin "F1") (pinfunction "~{O4}_F1") (pintype "output"))
    )
    (net (code "667") (name "~{WRTM}") (class "Default")
      (node (ref "B08") (pin "H2") (pinfunction "IN1_H2") (pintype "input"))
      (node (ref "D07") (pin "H1") (pinfunction "~{O6}_H1") (pintype "output"))
    )
    (net (code "668") (name "~{WR_EN}") (class "Default")
      (node (ref "B11") (pin "F1") (pinfunction "IN2_F1") (pintype "input"))
      (node (ref "C11") (pin "H2") (pinfunction "IN1_H2") (pintype "input"))
      (node (ref "C12") (pin "J2") (pinfunction "IN1_J2") (pintype "input"))
      (node (ref "C14") (pin "S1") (pinfunction "1_S1") (pintype "output"))
      (node (ref "C15") (pin "D2") (pinfunction "IN1_D2") (pintype "input"))
      (node (ref "C15") (pin "H2") (pinfunction "IN1_H2") (pintype "input"))
    )
    (net (code "669") (name "~{XSAD}") (class "Default")
      (node (ref "A11") (pin "K2") (pinfunction "IN_K2") (pintype "input"))
      (node (ref "D13") (pin "L2") (pinfunction "F2_L2") (pintype "output"))
    )
    (net (code "670") (name "~{XSTA}") (class "Default")
      (node (ref "B08") (pin "R2") (pinfunction "IN2_R2") (pintype "input"))
      (node (ref "C04") (pin "E1") (pinfunction "E1_E1") (pintype "output"))
      (node (ref "D13") (pin "H2") (pinfunction "H2_H2") (pintype "input"))
      (node (ref "D13") (pin "J2") (pinfunction "J2_J2") (pintype "input"))
      (node (ref "D13") (pin "K2") (pinfunction "K2_K2") (pintype "input"))
      (node (ref "D14") (pin "K2") (pinfunction "U1_K2") (pintype "input"))
      (node (ref "D14") (pin "L2") (pinfunction "S1_L2") (pintype "input"))
      (node (ref "D16") (pin "M2") (pinfunction "H2_M2") (pintype "input"))
      (node (ref "D16") (pin "N2") (pinfunction "J2_N2") (pintype "input"))
    )
  )
)
